# BeagleBone_Blue.net
KiCad netlist of a schematic drawn in EAGLE
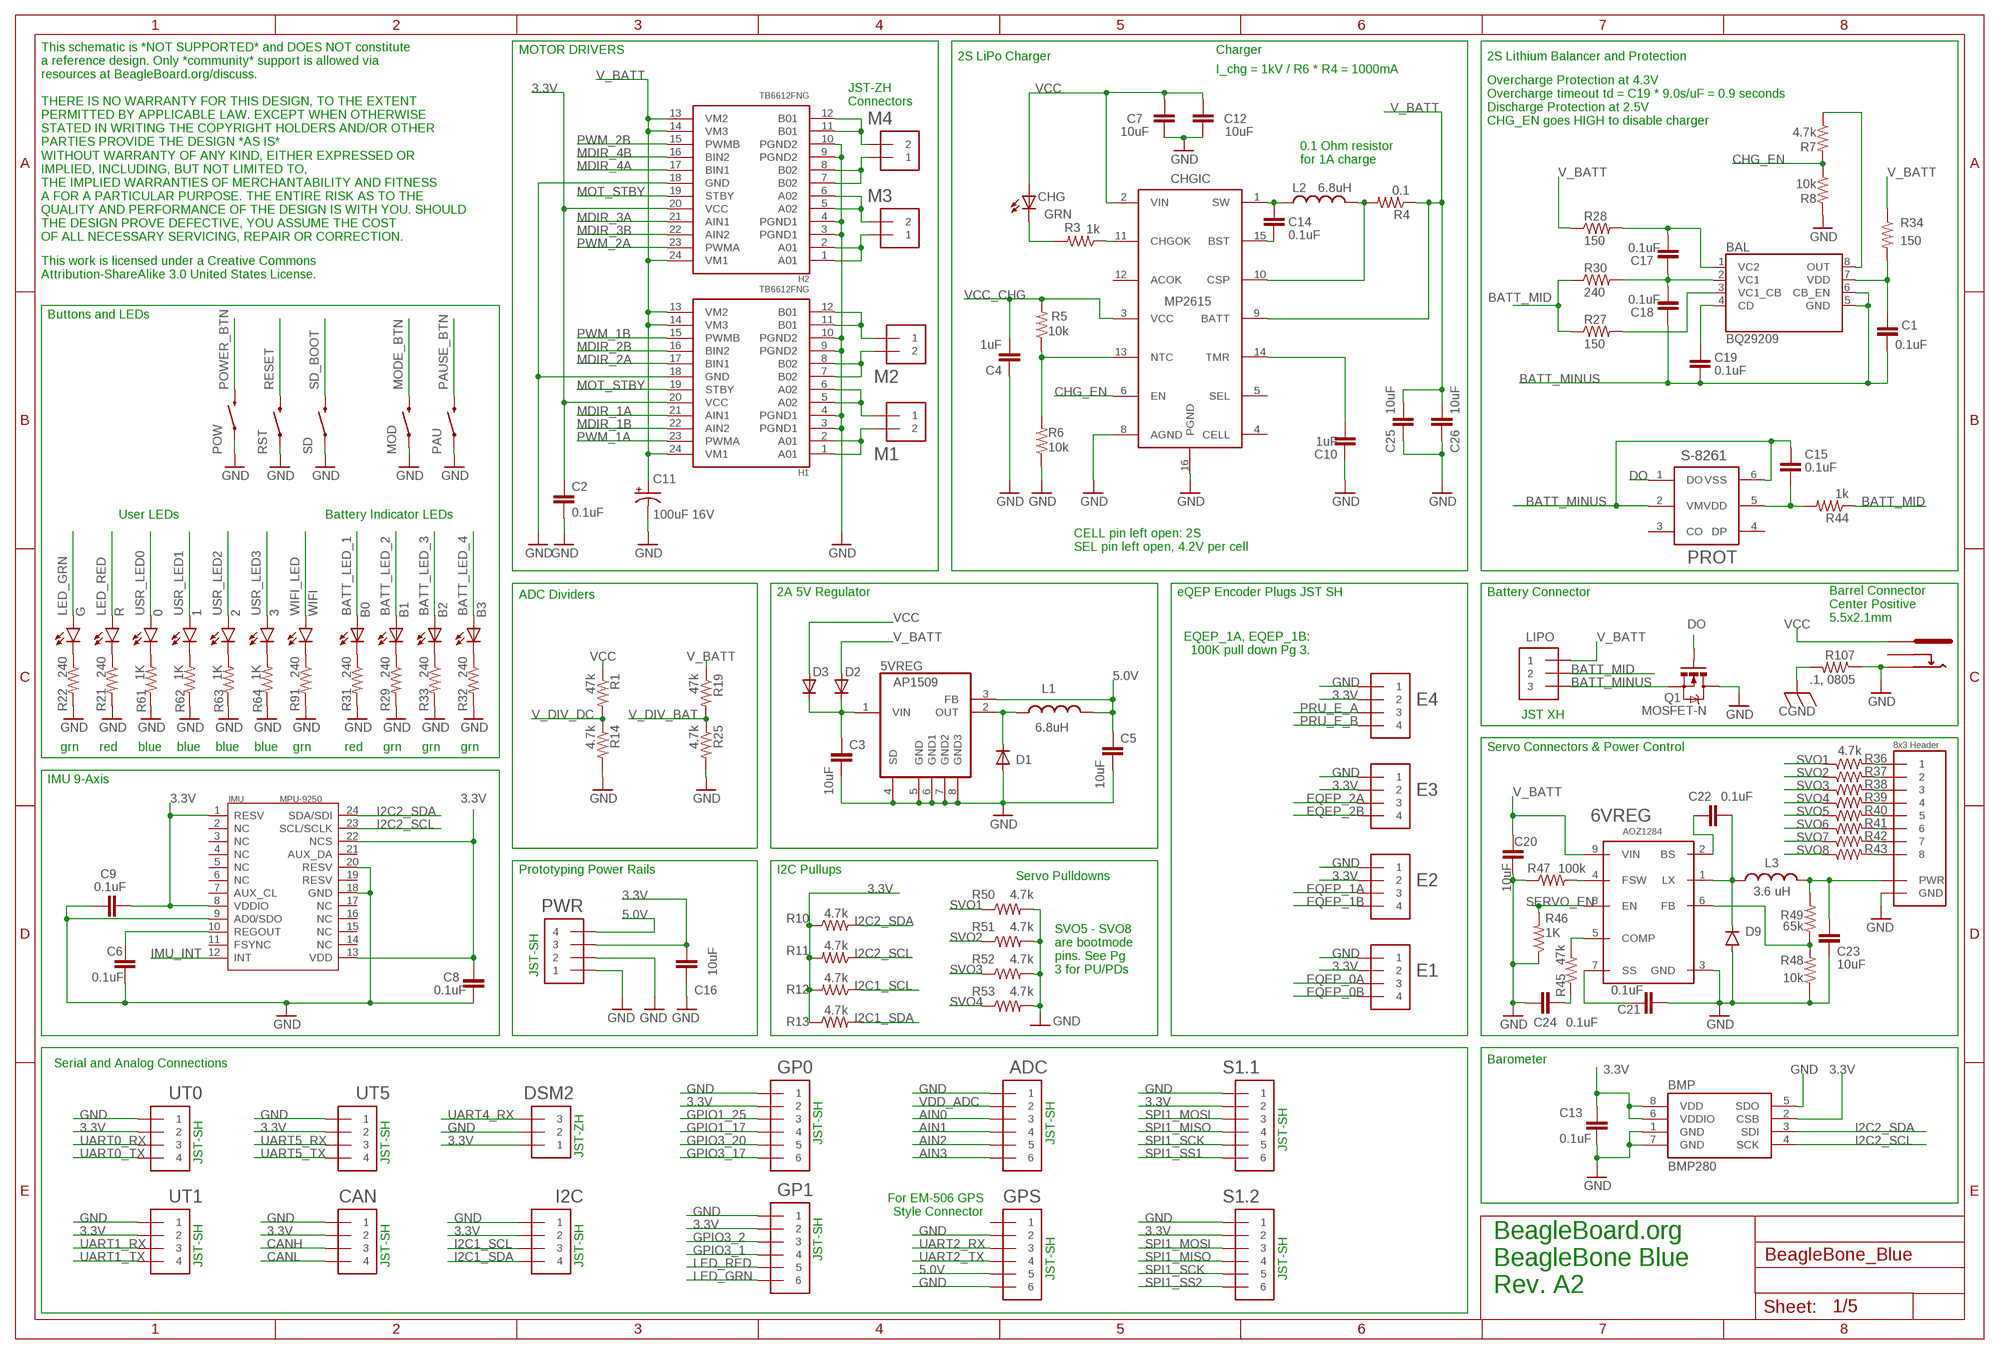
[diagram p0: schematic, sheet 1]
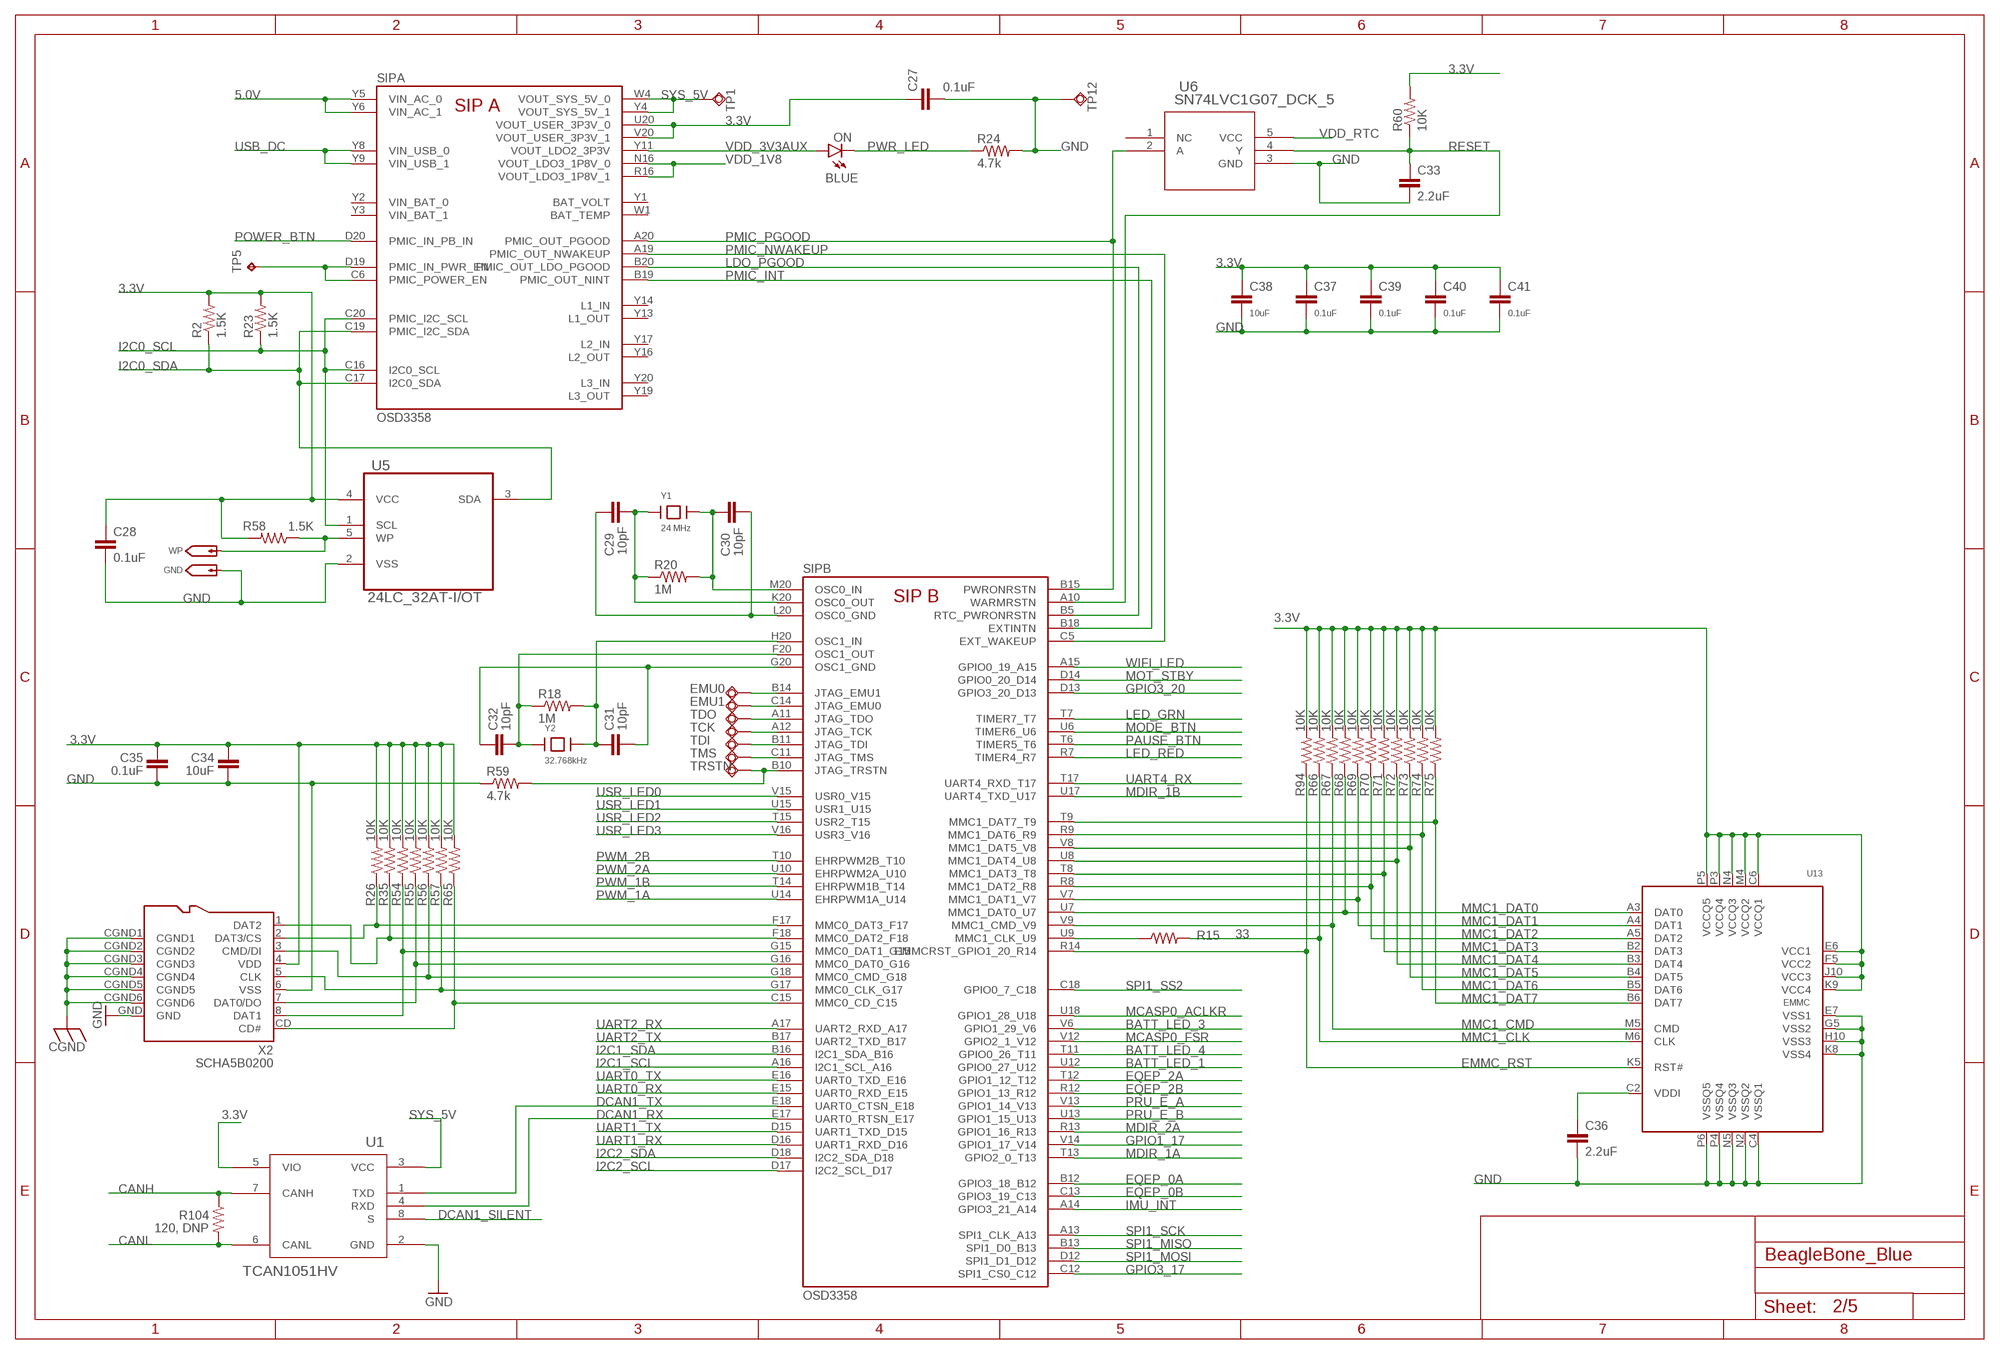
[diagram p1: schematic, sheet 2]
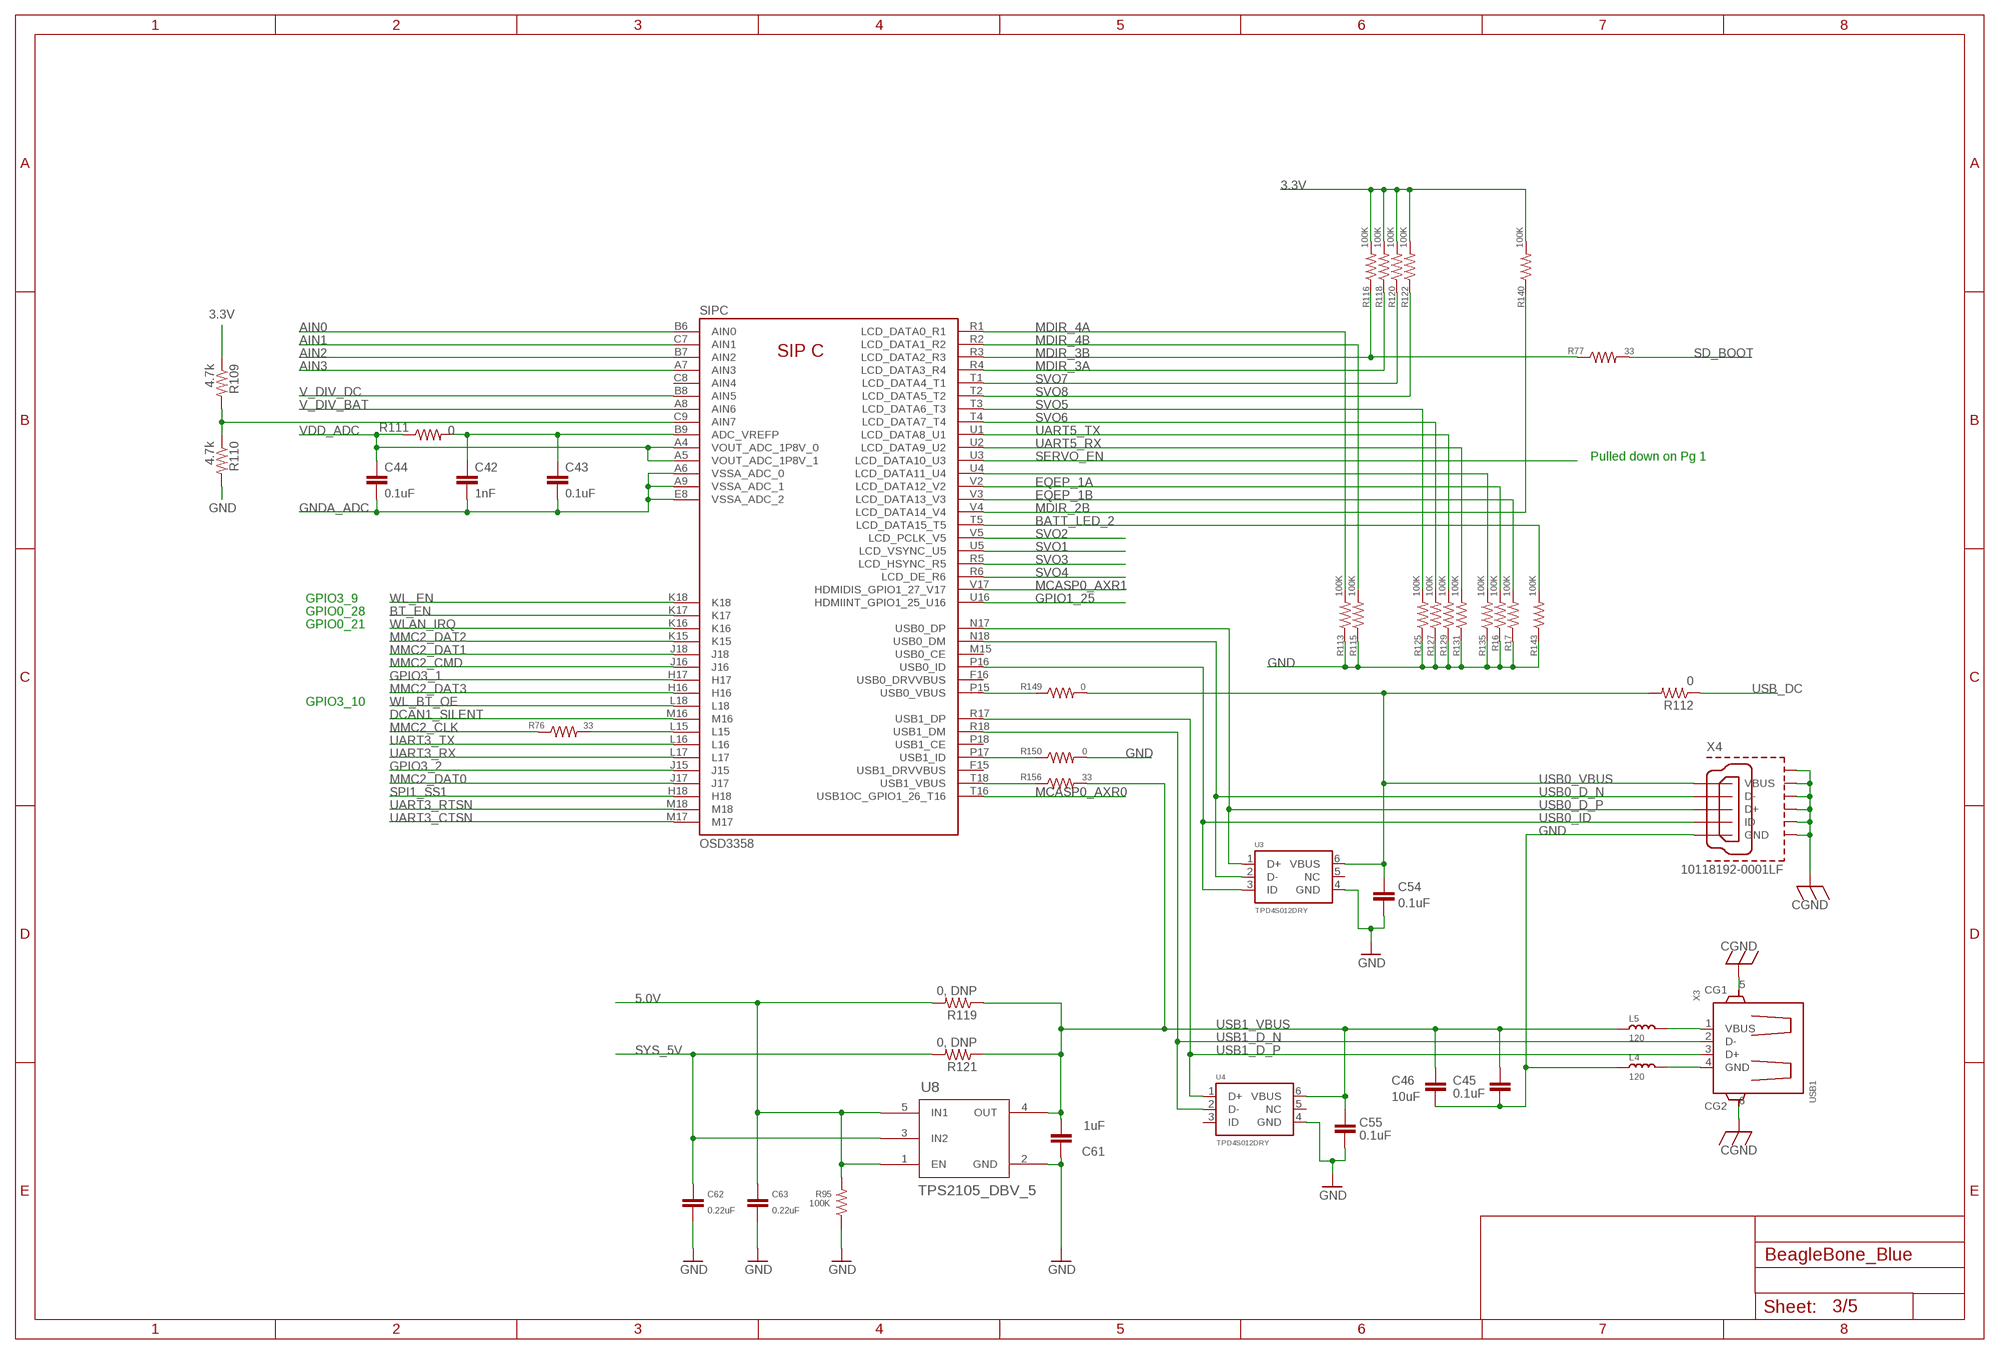
[diagram p2: schematic, sheet 3]
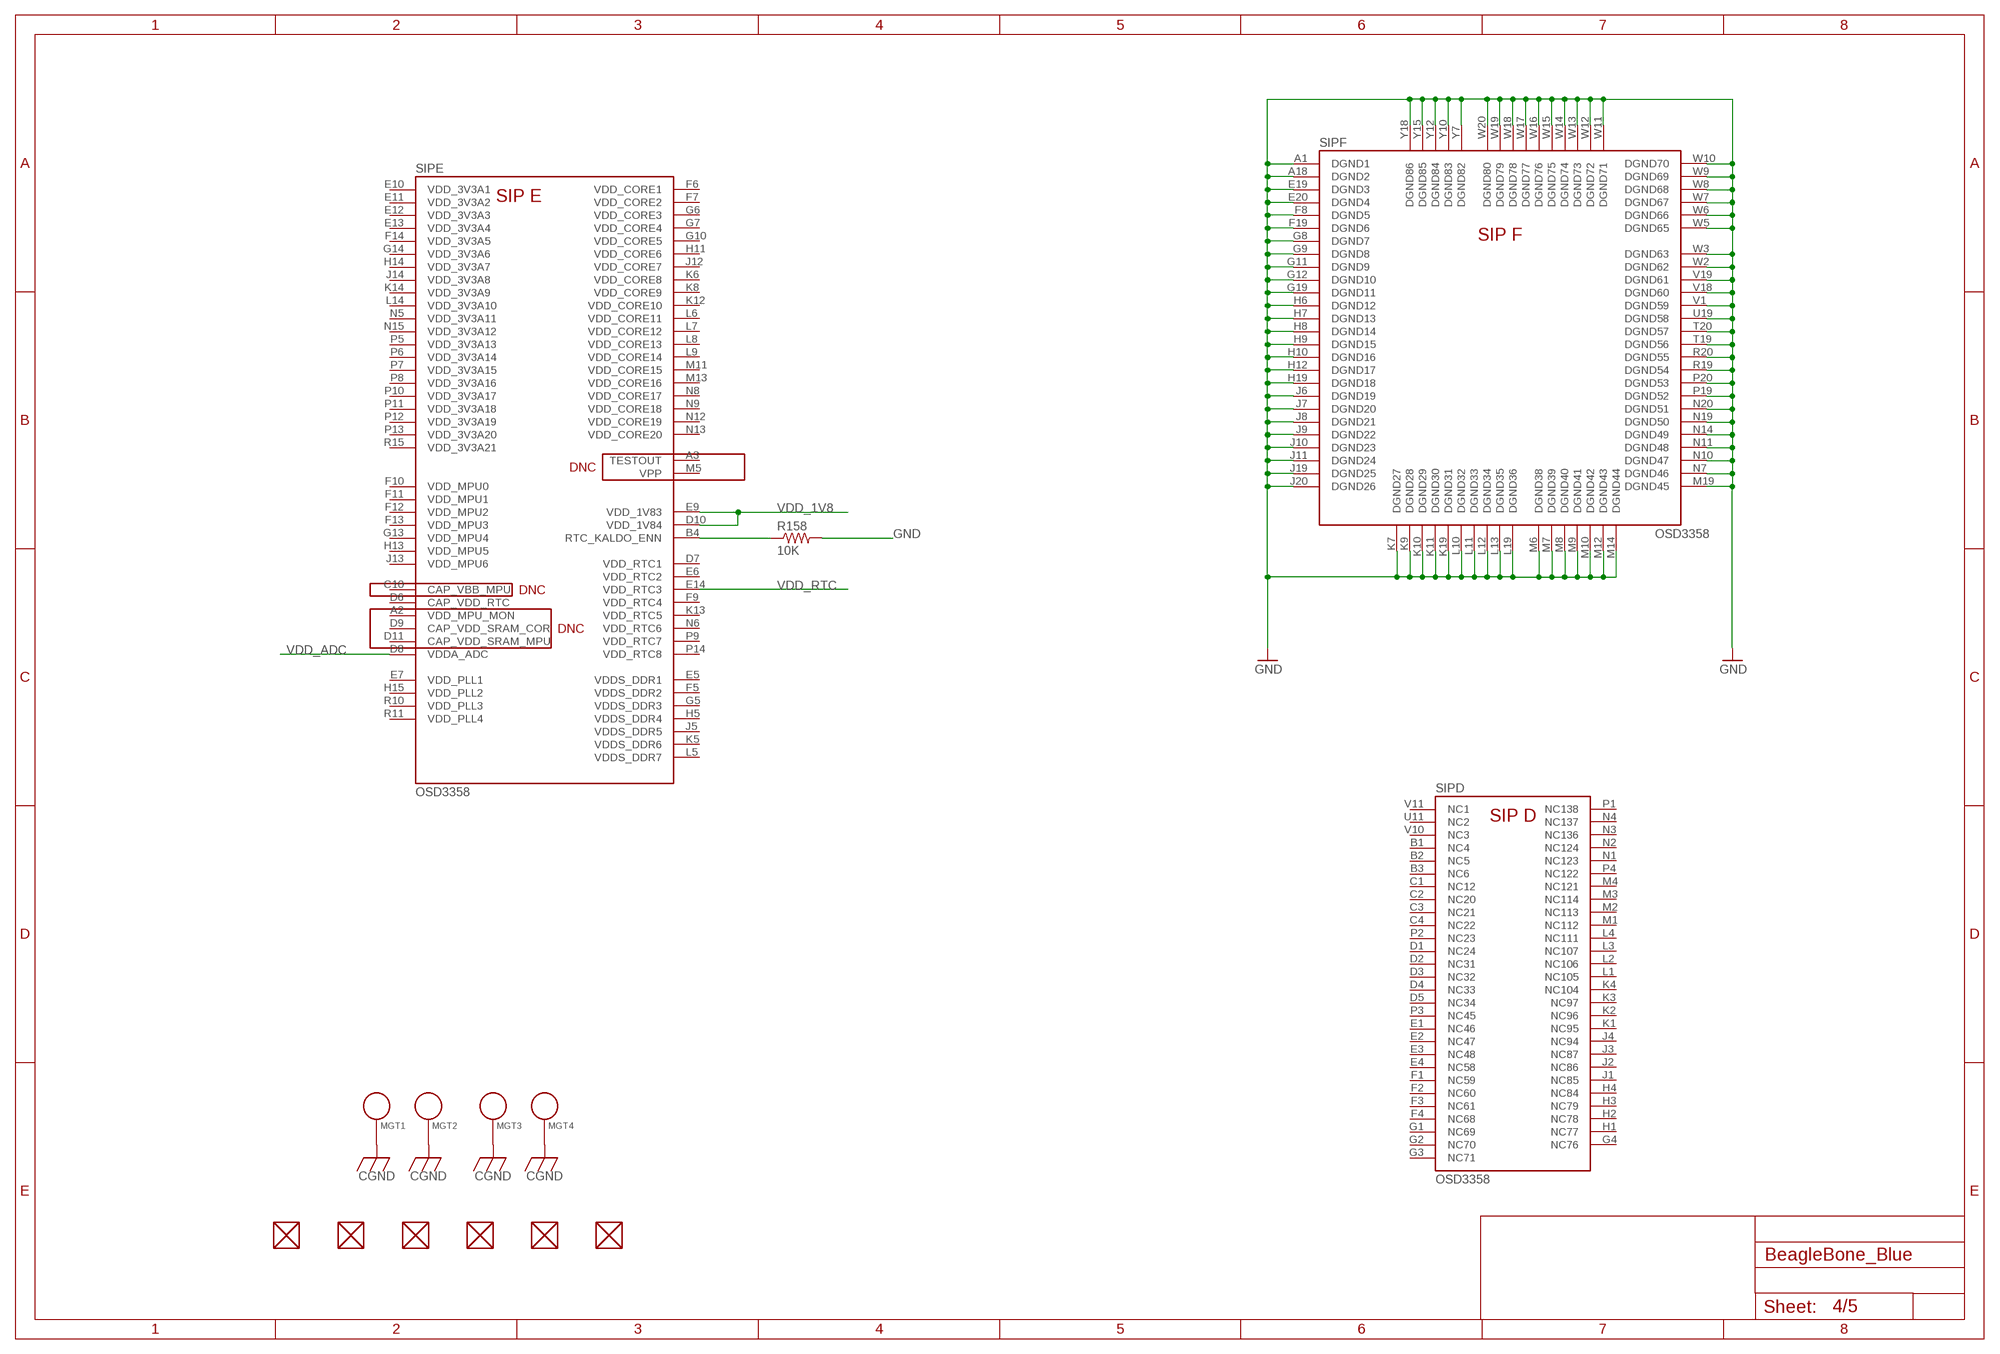
[diagram p3: schematic, sheet 4]
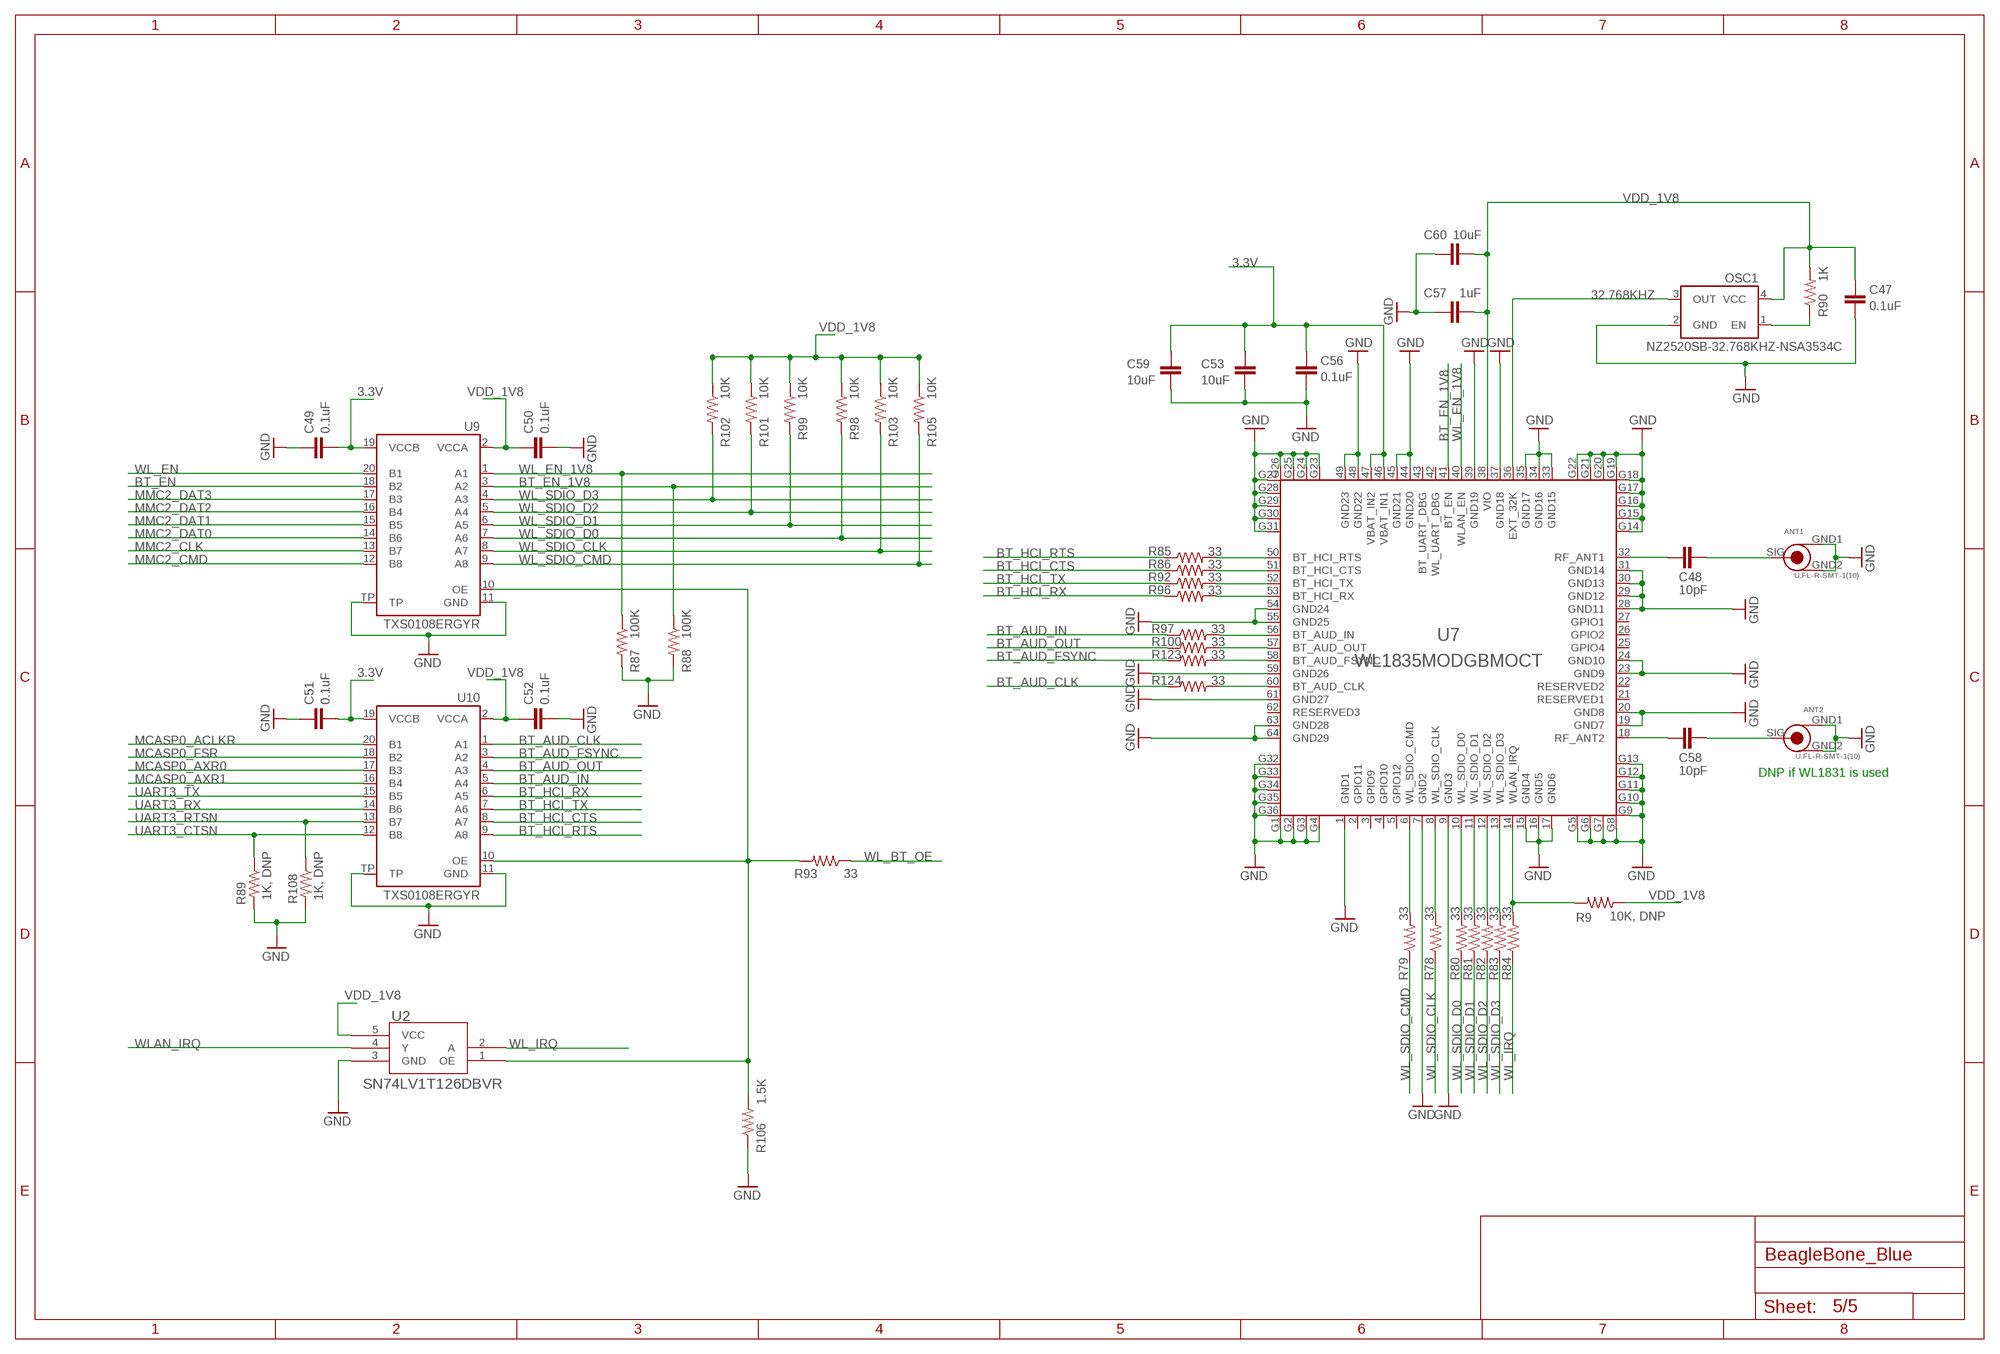
[diagram p4: schematic, sheet 5]

(export (version "E")
  (design (tool "Eeschema 10.0.6"))
  (components
    (comp (ref "C42")
      (value "1nF")
      (footprint "eagle-import:0402-CAP")
      (libsource (lib "eagle-import") (part "Strawson_Eagle_Lib_CAP0402-CAP"))
    )
    (comp (ref "C43")
      (value "0.1uF")
      (footprint "eagle-import:0402-CAP")
      (libsource (lib "eagle-import") (part "Strawson_Eagle_Lib_CAP0402-CAP"))
    )
    (comp (ref "C44")
      (value "0.1uF")
      (footprint "eagle-import:0402-CAP")
      (libsource (lib "eagle-import") (part "Strawson_Eagle_Lib_CAP0402-CAP"))
    )
    (comp (ref "C45")
      (value "0.1uF")
      (footprint "eagle-import:0402-CAP")
      (libsource (lib "eagle-import") (part "Strawson_Eagle_Lib_CAP0402-CAP"))
    )
    (comp (ref "C46")
      (value "10uF")
      (footprint "eagle-import:0805")
      (libsource (lib "eagle-import") (part "Strawson_Eagle_Lib_CAP0805"))
    )
    (comp (ref "C54")
      (value "0.1uF")
      (footprint "eagle-import:0402-CAP")
      (libsource (lib "eagle-import") (part "Strawson_Eagle_Lib_CAP0402-CAP"))
    )
    (comp (ref "C55")
      (value "0.1uF")
      (footprint "eagle-import:0402-CAP")
      (libsource (lib "eagle-import") (part "Strawson_Eagle_Lib_CAP0402-CAP"))
    )
    (comp (ref "C61")
      (value "1uF")
      (footprint "eagle-import:0402-CAP")
      (libsource (lib "eagle-import") (part "Strawson_Eagle_Lib_CAP0402-CAP"))
    )
    (comp (ref "C62")
      (value "0.22uF")
      (footprint "eagle-import:0402-CAP")
      (libsource (lib "eagle-import") (part "Strawson_Eagle_Lib_CAP0402-CAP"))
    )
    (comp (ref "C63")
      (value "0.22uF")
      (footprint "eagle-import:0402-CAP")
      (libsource (lib "eagle-import") (part "Strawson_Eagle_Lib_CAP0402-CAP"))
    )
    (comp (ref "L4")
      (value "120")
      (footprint "eagle-import:L0603")
      (libsource (lib "eagle-import") (part "INDUCTOR/FERRITE-BEAD'0603'"))
    )
    (comp (ref "L5")
      (value "120")
      (footprint "eagle-import:L0603")
      (libsource (lib "eagle-import") (part "INDUCTOR/FERRITE-BEAD'0603'"))
    )
    (comp (ref "R16")
      (value "100K")
      (footprint "eagle-import:0402-RES")
      (libsource (lib "eagle-import") (part "RESISTOR0402-RES"))
    )
    (comp (ref "R17")
      (value "100K")
      (footprint "eagle-import:0402-RES")
      (libsource (lib "eagle-import") (part "RESISTOR0402-RES"))
    )
    (comp (ref "R76")
      (value "33")
      (footprint "eagle-import:0402-RES")
      (libsource (lib "eagle-import") (part "RESISTOR0402-RES"))
    )
    (comp (ref "R77")
      (value "33")
      (footprint "eagle-import:0402-RES")
      (libsource (lib "eagle-import") (part "RESISTOR0402-RES"))
    )
    (comp (ref "R95")
      (value "100K")
      (footprint "eagle-import:0402-RES")
      (libsource (lib "eagle-import") (part "RESISTOR0402-RES"))
    )
    (comp (ref "R109")
      (value "4.7k")
      (footprint "eagle-import:0402-RES")
      (libsource (lib "eagle-import") (part "RESISTOR0402-RES"))
    )
    (comp (ref "R110")
      (value "4.7k")
      (footprint "eagle-import:0402-RES")
      (libsource (lib "eagle-import") (part "RESISTOR0402-RES"))
    )
    (comp (ref "R111")
      (value "0")
      (footprint "eagle-import:0402-RES")
      (libsource (lib "eagle-import") (part "RESISTOR0402-RES"))
    )
    (comp (ref "R112")
      (value "0")
      (footprint "eagle-import:0603-RES")
      (libsource (lib "eagle-import") (part "RESISTOR0603"))
    )
    (comp (ref "R113")
      (value "100K")
      (footprint "eagle-import:0402-RES")
      (libsource (lib "eagle-import") (part "RESISTOR0402-RES"))
    )
    (comp (ref "R115")
      (value "100K")
      (footprint "eagle-import:0402-RES")
      (libsource (lib "eagle-import") (part "RESISTOR0402-RES"))
    )
    (comp (ref "R116")
      (value "100K")
      (footprint "eagle-import:0402-RES")
      (libsource (lib "eagle-import") (part "RESISTOR0402-RES"))
    )
    (comp (ref "R118")
      (value "100K")
      (footprint "eagle-import:0402-RES")
      (libsource (lib "eagle-import") (part "RESISTOR0402-RES"))
    )
    (comp (ref "R119")
      (value "0, DNP")
      (footprint "eagle-import:0603-RES")
      (libsource (lib "eagle-import") (part "RESISTOR0603"))
    )
    (comp (ref "R120")
      (value "100K")
      (footprint "eagle-import:0402-RES")
      (libsource (lib "eagle-import") (part "RESISTOR0402-RES"))
    )
    (comp (ref "R121")
      (value "0, DNP")
      (footprint "eagle-import:0603-RES")
      (libsource (lib "eagle-import") (part "RESISTOR0603"))
    )
    (comp (ref "R122")
      (value "100K")
      (footprint "eagle-import:0402-RES")
      (libsource (lib "eagle-import") (part "RESISTOR0402-RES"))
    )
    (comp (ref "R125")
      (value "100K")
      (footprint "eagle-import:0402-RES")
      (libsource (lib "eagle-import") (part "RESISTOR0402-RES"))
    )
    (comp (ref "R127")
      (value "100K")
      (footprint "eagle-import:0402-RES")
      (libsource (lib "eagle-import") (part "RESISTOR0402-RES"))
    )
    (comp (ref "R129")
      (value "100K")
      (footprint "eagle-import:0402-RES")
      (libsource (lib "eagle-import") (part "RESISTOR0402-RES"))
    )
    (comp (ref "R131")
      (value "100K")
      (footprint "eagle-import:0402-RES")
      (libsource (lib "eagle-import") (part "RESISTOR0402-RES"))
    )
    (comp (ref "R135")
      (value "100K")
      (footprint "eagle-import:0402-RES")
      (libsource (lib "eagle-import") (part "RESISTOR0402-RES"))
    )
    (comp (ref "R140")
      (value "100K")
      (footprint "eagle-import:0402-RES")
      (libsource (lib "eagle-import") (part "RESISTOR0402-RES"))
    )
    (comp (ref "R143")
      (value "100K")
      (footprint "eagle-import:0402-RES")
      (libsource (lib "eagle-import") (part "RESISTOR0402-RES"))
    )
    (comp (ref "R149")
      (value "0")
      (footprint "eagle-import:0402-RES")
      (libsource (lib "eagle-import") (part "RESISTOR0402-RES"))
    )
    (comp (ref "R150")
      (value "0")
      (footprint "eagle-import:0402-RES")
      (libsource (lib "eagle-import") (part "RESISTOR0402-RES"))
    )
    (comp (ref "R156")
      (value "33")
      (footprint "eagle-import:0402-RES")
      (libsource (lib "eagle-import") (part "RESISTOR0402-RES"))
    )
    (comp (ref "SIP")
      (value "OSD3358")
      (footprint "eagle-import:BEAGLEBONE_BLUE_OSD3358")
      (libsource (lib "eagle-import") (part "OSD3358"))
    )
    (comp (ref "U3")
      (value "TPD4S012DRY")
      (footprint "eagle-import:SON-6(TI)-DRY")
      (libsource (lib "eagle-import") (part "TPD4S012DRYR"))
    )
    (comp (ref "U4")
      (value "TPD4S012DRY")
      (footprint "eagle-import:SON-6(TI)-DRY")
      (libsource (lib "eagle-import") (part "TPD4S012DRYR"))
    )
    (comp (ref "U8")
      (value "TPS2105_DBV_5")
      (footprint "eagle-import:DBV5")
      (fields
        (field (name "GENERIC_PART_NUMBER") "TPS2105")
        (field (name "MANUFACTURER") "Texas Instruments")
        (field (name "MANUFACTURER_PART_NUMBER") "tps2105_dbv_5")
      )
      (libsource (lib "eagle-import") (part "TPS2105_DBV_5"))
    )
    (comp (ref "X3")
      (value "USB1")
      (footprint "eagle-import:USB_HOST_HORIZONTAL_W_CHASSIS_GND")
      (libsource (lib "eagle-import") (part "USB_HOST_W/CHASSIS_GND"))
    )
    (comp (ref "X4")
      (value "10118192-0001LF")
      (footprint "eagle-import:10118192-0001LF(MICRO-USB-B-AMPHENOL-FCI)")
      (libsource (lib "eagle-import") (part "10118192-0001LF"))
    )
    (comp (ref "ANT1")
      (value "U.FL-R-SMT-1(10)")
      (footprint "eagle-import:U.FL-R-SMT-1")
      (libsource (lib "eagle-import") (part "U.FL-R-SMT-1"))
    )
    (comp (ref "ANT2")
      (value "U.FL-R-SMT-1(10)")
      (footprint "eagle-import:U.FL-R-SMT-1")
      (libsource (lib "eagle-import") (part "U.FL-R-SMT-1"))
    )
    (comp (ref "C47")
      (value "0.1uF")
      (footprint "eagle-import:0402-CAP")
      (libsource (lib "eagle-import") (part "Strawson_Eagle_Lib_CAP0402-CAP"))
    )
    (comp (ref "C48")
      (value "10pF")
      (footprint "eagle-import:0402-CAP")
      (libsource (lib "eagle-import") (part "Strawson_Eagle_Lib_CAP0402-CAP"))
    )
    (comp (ref "C49")
      (value "0.1uF")
      (footprint "eagle-import:0402-CAP")
      (libsource (lib "eagle-import") (part "Strawson_Eagle_Lib_CAP0402-CAP"))
    )
    (comp (ref "C50")
      (value "0.1uF")
      (footprint "eagle-import:0402-CAP")
      (libsource (lib "eagle-import") (part "Strawson_Eagle_Lib_CAP0402-CAP"))
    )
    (comp (ref "C51")
      (value "0.1uF")
      (footprint "eagle-import:0402-CAP")
      (libsource (lib "eagle-import") (part "Strawson_Eagle_Lib_CAP0402-CAP"))
    )
    (comp (ref "C52")
      (value "0.1uF")
      (footprint "eagle-import:0402-CAP")
      (libsource (lib "eagle-import") (part "Strawson_Eagle_Lib_CAP0402-CAP"))
    )
    (comp (ref "C53")
      (value "10uF")
      (footprint "eagle-import:0805")
      (libsource (lib "eagle-import") (part "CAP0805"))
    )
    (comp (ref "C56")
      (value "0.1uF")
      (footprint "eagle-import:0402-CAP")
      (libsource (lib "eagle-import") (part "Strawson_Eagle_Lib_CAP0402-CAP"))
    )
    (comp (ref "C57")
      (value "1uF")
      (footprint "eagle-import:0402-CAP")
      (libsource (lib "eagle-import") (part "Strawson_Eagle_Lib_CAP0402-CAP"))
    )
    (comp (ref "C58")
      (value "10pF")
      (footprint "eagle-import:0402-CAP")
      (libsource (lib "eagle-import") (part "Strawson_Eagle_Lib_CAP0402-CAP"))
    )
    (comp (ref "C59")
      (value "10uF")
      (footprint "eagle-import:0805")
      (libsource (lib "eagle-import") (part "CAP0805"))
    )
    (comp (ref "C60")
      (value "10uF")
      (footprint "eagle-import:0805")
      (libsource (lib "eagle-import") (part "CAP0805"))
    )
    (comp (ref "OSC1")
      (value "NZ2520SB-32.768KHZ-NSA3534C")
      (footprint "eagle-import:NZ2520S")
      (libsource (lib "eagle-import") (part "OSCILLATOR"))
    )
    (comp (ref "R9")
      (value "10K, DNP")
      (footprint "eagle-import:0402-RES")
      (libsource (lib "eagle-import") (part "RESISTOR0402-RES"))
    )
    (comp (ref "R78")
      (value "33")
      (footprint "eagle-import:0402-RES")
      (libsource (lib "eagle-import") (part "RESISTOR0402-RES"))
    )
    (comp (ref "R79")
      (value "33")
      (footprint "eagle-import:0402-RES")
      (libsource (lib "eagle-import") (part "RESISTOR0402-RES"))
    )
    (comp (ref "R80")
      (value "33")
      (footprint "eagle-import:0402-RES")
      (libsource (lib "eagle-import") (part "RESISTOR0402-RES"))
    )
    (comp (ref "R81")
      (value "33")
      (footprint "eagle-import:0402-RES")
      (libsource (lib "eagle-import") (part "RESISTOR0402-RES"))
    )
    (comp (ref "R82")
      (value "33")
      (footprint "eagle-import:0402-RES")
      (libsource (lib "eagle-import") (part "RESISTOR0402-RES"))
    )
    (comp (ref "R83")
      (value "33")
      (footprint "eagle-import:0402-RES")
      (libsource (lib "eagle-import") (part "RESISTOR0402-RES"))
    )
    (comp (ref "R84")
      (value "33")
      (footprint "eagle-import:0402-RES")
      (libsource (lib "eagle-import") (part "RESISTOR0402-RES"))
    )
    (comp (ref "R85")
      (value "33")
      (footprint "eagle-import:0402-RES")
      (libsource (lib "eagle-import") (part "RESISTOR0402-RES"))
    )
    (comp (ref "R86")
      (value "33")
      (footprint "eagle-import:0402-RES")
      (libsource (lib "eagle-import") (part "RESISTOR0402-RES"))
    )
    (comp (ref "R87")
      (value "100K")
      (footprint "eagle-import:0402-RES")
      (libsource (lib "eagle-import") (part "RESISTOR0402-RES"))
    )
    (comp (ref "R88")
      (value "100K")
      (footprint "eagle-import:0402-RES")
      (libsource (lib "eagle-import") (part "RESISTOR0402-RES"))
    )
    (comp (ref "R89")
      (value "1K, DNP")
      (footprint "eagle-import:0402-RES")
      (libsource (lib "eagle-import") (part "RESISTOR0402-RES"))
    )
    (comp (ref "R90")
      (value "1K")
      (footprint "eagle-import:0402-RES")
      (libsource (lib "eagle-import") (part "RESISTOR0402-RES"))
    )
    (comp (ref "R92")
      (value "33")
      (footprint "eagle-import:0402-RES")
      (libsource (lib "eagle-import") (part "RESISTOR0402-RES"))
    )
    (comp (ref "R93")
      (value "33")
      (footprint "eagle-import:0402-RES")
      (libsource (lib "eagle-import") (part "RESISTOR0402-RES"))
    )
    (comp (ref "R96")
      (value "33")
      (footprint "eagle-import:0402-RES")
      (libsource (lib "eagle-import") (part "RESISTOR0402-RES"))
    )
    (comp (ref "R97")
      (value "33")
      (footprint "eagle-import:0402-RES")
      (libsource (lib "eagle-import") (part "RESISTOR0402-RES"))
    )
    (comp (ref "R98")
      (value "10K")
      (footprint "eagle-import:0402-RES")
      (libsource (lib "eagle-import") (part "RESISTOR0402-RES"))
    )
    (comp (ref "R99")
      (value "10K")
      (footprint "eagle-import:0402-RES")
      (libsource (lib "eagle-import") (part "RESISTOR0402-RES"))
    )
    (comp (ref "R100")
      (value "33")
      (footprint "eagle-import:0402-RES")
      (libsource (lib "eagle-import") (part "RESISTOR0402-RES"))
    )
    (comp (ref "R101")
      (value "10K")
      (footprint "eagle-import:0402-RES")
      (libsource (lib "eagle-import") (part "RESISTOR0402-RES"))
    )
    (comp (ref "R102")
      (value "10K")
      (footprint "eagle-import:0402-RES")
      (libsource (lib "eagle-import") (part "RESISTOR0402-RES"))
    )
    (comp (ref "R103")
      (value "10K")
      (footprint "eagle-import:0402-RES")
      (libsource (lib "eagle-import") (part "RESISTOR0402-RES"))
    )
    (comp (ref "R105")
      (value "10K")
      (footprint "eagle-import:0402-RES")
      (libsource (lib "eagle-import") (part "RESISTOR0402-RES"))
    )
    (comp (ref "R106")
      (value "1.5K")
      (footprint "eagle-import:0402-RES")
      (libsource (lib "eagle-import") (part "RESISTOR0402-RES"))
    )
    (comp (ref "R108")
      (value "1K, DNP")
      (footprint "eagle-import:0402-RES")
      (libsource (lib "eagle-import") (part "RESISTOR0402-RES"))
    )
    (comp (ref "R123")
      (value "33")
      (footprint "eagle-import:0402-RES")
      (libsource (lib "eagle-import") (part "RESISTOR0402-RES"))
    )
    (comp (ref "R124")
      (value "33")
      (footprint "eagle-import:0402-RES")
      (libsource (lib "eagle-import") (part "RESISTOR0402-RES"))
    )
    (comp (ref "U2")
      (value "SN74LV1T126DBVR")
      (footprint "eagle-import:BEAGLEBONE_BLUE_SOT23-5")
      (libsource (lib "eagle-import") (part "SN74LV1T126DBVR"))
    )
    (comp (ref "U7")
      (value "WL1835MODGBMOCT")
      (footprint "eagle-import:MOC-100(TI)")
      (libsource (lib "eagle-import") (part "WL1835MOD"))
    )
    (comp (ref "U9")
      (value "TXS0108ERGYR")
      (footprint "eagle-import:R-PVQFN-N20(TI)")
      (libsource (lib "eagle-import") (part "TXS0108ERGYR"))
    )
    (comp (ref "U10")
      (value "TXS0108ERGYR")
      (footprint "eagle-import:R-PVQFN-N20(TI)")
      (libsource (lib "eagle-import") (part "TXS0108ERGYR"))
    )
    (comp (ref "FUD1")
      (value "FIDUCIAL")
      (footprint "eagle-import:FIDUCIAL_40MIL")
      (libsource (lib "eagle-import") (part "FIDUCIAL"))
    )
    (comp (ref "FUD2")
      (value "FIDUCIAL")
      (footprint "eagle-import:FIDUCIAL_40MIL")
      (libsource (lib "eagle-import") (part "FIDUCIAL"))
    )
    (comp (ref "FUD3")
      (value "FIDUCIAL")
      (footprint "eagle-import:FIDUCIAL_40MIL")
      (libsource (lib "eagle-import") (part "FIDUCIAL"))
    )
    (comp (ref "FUD4")
      (value "FIDUCIAL")
      (footprint "eagle-import:FIDUCIAL_40MIL")
      (libsource (lib "eagle-import") (part "FIDUCIAL"))
    )
    (comp (ref "FUD5")
      (value "FIDUCIAL")
      (footprint "eagle-import:FIDUCIAL_40MIL")
      (libsource (lib "eagle-import") (part "FIDUCIAL"))
    )
    (comp (ref "FUD6")
      (value "FIDUCIAL")
      (footprint "eagle-import:FIDUCIAL_40MIL")
      (libsource (lib "eagle-import") (part "FIDUCIAL"))
    )
    (comp (ref "MGT1")
      (value "MOUNTING_HOLE")
      (footprint "eagle-import:MOUNTING_HOLE")
      (libsource (lib "eagle-import") (part "MOUNTING_HOLE"))
    )
    (comp (ref "MGT2")
      (value "MOUNTING_HOLE")
      (footprint "eagle-import:MOUNTING_HOLE")
      (libsource (lib "eagle-import") (part "MOUNTING_HOLE"))
    )
    (comp (ref "MGT3")
      (value "MOUNTING_HOLE")
      (footprint "eagle-import:MOUNTING_HOLE")
      (libsource (lib "eagle-import") (part "MOUNTING_HOLE"))
    )
    (comp (ref "MGT4")
      (value "MOUNTING_HOLE")
      (footprint "eagle-import:MOUNTING_HOLE")
      (libsource (lib "eagle-import") (part "MOUNTING_HOLE"))
    )
    (comp (ref "R158")
      (value "10K")
      (footprint "eagle-import:0402-RES")
      (libsource (lib "eagle-import") (part "RESISTOR0402-RES"))
    )
    (comp (ref "C27")
      (value "0.1uF")
      (footprint "eagle-import:0402-CAP")
      (libsource (lib "eagle-import") (part "Strawson_Eagle_Lib_CAP0402-CAP"))
    )
    (comp (ref "C28")
      (value "0.1uF")
      (footprint "eagle-import:0402-CAP")
      (libsource (lib "eagle-import") (part "Strawson_Eagle_Lib_CAP0402-CAP"))
    )
    (comp (ref "C29")
      (value "10pF")
      (footprint "eagle-import:0402-CAP")
      (libsource (lib "eagle-import") (part "Strawson_Eagle_Lib_CAP0402-CAP"))
    )
    (comp (ref "C30")
      (value "10pF")
      (footprint "eagle-import:0402-CAP")
      (libsource (lib "eagle-import") (part "Strawson_Eagle_Lib_CAP0402-CAP"))
    )
    (comp (ref "C31")
      (value "10pF")
      (footprint "eagle-import:0402-CAP")
      (libsource (lib "eagle-import") (part "Strawson_Eagle_Lib_CAP0402-CAP"))
    )
    (comp (ref "C32")
      (value "10pF")
      (footprint "eagle-import:0402-CAP")
      (libsource (lib "eagle-import") (part "Strawson_Eagle_Lib_CAP0402-CAP"))
    )
    (comp (ref "C33")
      (value "2.2uF")
      (footprint "eagle-import:0402-CAP")
      (libsource (lib "eagle-import") (part "Strawson_Eagle_Lib_CAP0402-CAP"))
    )
    (comp (ref "C34")
      (value "10uF")
      (footprint "eagle-import:0805")
      (libsource (lib "eagle-import") (part "Strawson_Eagle_Lib_CAP0805"))
    )
    (comp (ref "C35")
      (value "0.1uF")
      (footprint "eagle-import:0402-CAP")
      (libsource (lib "eagle-import") (part "Strawson_Eagle_Lib_CAP0402-CAP"))
    )
    (comp (ref "C36")
      (value "2.2uF")
      (footprint "eagle-import:0402-CAP")
      (libsource (lib "eagle-import") (part "Strawson_Eagle_Lib_CAP0402-CAP"))
    )
    (comp (ref "C37")
      (value "0.1uF")
      (footprint "eagle-import:0402-CAP")
      (libsource (lib "eagle-import") (part "Strawson_Eagle_Lib_CAP0402-CAP"))
    )
    (comp (ref "C38")
      (value "10uF")
      (footprint "eagle-import:0805")
      (libsource (lib "eagle-import") (part "Strawson_Eagle_Lib_CAP0805"))
    )
    (comp (ref "C39")
      (value "0.1uF")
      (footprint "eagle-import:0402-CAP")
      (libsource (lib "eagle-import") (part "Strawson_Eagle_Lib_CAP0402-CAP"))
    )
    (comp (ref "C40")
      (value "0.1uF")
      (footprint "eagle-import:0402-CAP")
      (libsource (lib "eagle-import") (part "Strawson_Eagle_Lib_CAP0402-CAP"))
    )
    (comp (ref "C41")
      (value "0.1uF")
      (footprint "eagle-import:0402-CAP")
      (libsource (lib "eagle-import") (part "Strawson_Eagle_Lib_CAP0402-CAP"))
    )
    (comp (ref "EMU0")
      (value "TPSQB1,27")
      (footprint "eagle-import:B1,27")
      (libsource (lib "eagle-import") (part "TPSQB1,27"))
    )
    (comp (ref "EMU1")
      (value "TPSQB1,27")
      (footprint "eagle-import:B1,27")
      (libsource (lib "eagle-import") (part "TPSQB1,27"))
    )
    (comp (ref "GND")
      (value "GHI2_TESTPAD/W_HOLE_1X1")
      (footprint "eagle-import:GHI2_TESTPAD_W_HOLE_1X1")
      (libsource (lib "eagle-import") (part "GHI2_TESTPAD/W_HOLE_1X1"))
    )
    (comp (ref "ON")
      (value "BLUE")
      (footprint "eagle-import:BEAGLEBONE_BLUE_LED-0603")
      (libsource (lib "eagle-import") (part "LED0603"))
    )
    (comp (ref "R2")
      (value "1.5K")
      (footprint "eagle-import:0402-RES")
      (libsource (lib "eagle-import") (part "RESISTOR0402-RES"))
    )
    (comp (ref "R15")
      (value "33")
      (footprint "eagle-import:0402-RES")
      (libsource (lib "eagle-import") (part "RESISTOR0402-RES"))
    )
    (comp (ref "R18")
      (value "1M")
      (footprint "eagle-import:0402-RES")
      (libsource (lib "eagle-import") (part "RESISTOR0402-RES"))
    )
    (comp (ref "R20")
      (value "1M")
      (footprint "eagle-import:0402-RES")
      (libsource (lib "eagle-import") (part "RESISTOR0402-RES"))
    )
    (comp (ref "R23")
      (value "1.5K")
      (footprint "eagle-import:0402-RES")
      (libsource (lib "eagle-import") (part "RESISTOR0402-RES"))
    )
    (comp (ref "R24")
      (value "4.7k")
      (footprint "eagle-import:0402-RES")
      (libsource (lib "eagle-import") (part "RESISTOR0402-RES"))
    )
    (comp (ref "R26")
      (value "10K")
      (footprint "eagle-import:0402-RES")
      (libsource (lib "eagle-import") (part "RESISTOR0402-RES"))
    )
    (comp (ref "R35")
      (value "10K")
      (footprint "eagle-import:0402-RES")
      (libsource (lib "eagle-import") (part "RESISTOR0402-RES"))
    )
    (comp (ref "R54")
      (value "10K")
      (footprint "eagle-import:0402-RES")
      (libsource (lib "eagle-import") (part "RESISTOR0402-RES"))
    )
    (comp (ref "R55")
      (value "10K")
      (footprint "eagle-import:0402-RES")
      (libsource (lib "eagle-import") (part "RESISTOR0402-RES"))
    )
    (comp (ref "R56")
      (value "10K")
      (footprint "eagle-import:0402-RES")
      (libsource (lib "eagle-import") (part "RESISTOR0402-RES"))
    )
    (comp (ref "R57")
      (value "10K")
      (footprint "eagle-import:0402-RES")
      (libsource (lib "eagle-import") (part "RESISTOR0402-RES"))
    )
    (comp (ref "R58")
      (value "1.5K")
      (footprint "eagle-import:0402-RES")
      (libsource (lib "eagle-import") (part "RESISTOR0402-RES"))
    )
    (comp (ref "R59")
      (value "4.7k")
      (footprint "eagle-import:0402-RES")
      (libsource (lib "eagle-import") (part "RESISTOR0402-RES"))
    )
    (comp (ref "R60")
      (value "10K")
      (footprint "eagle-import:0402-RES")
      (libsource (lib "eagle-import") (part "RESISTOR0402-RES"))
    )
    (comp (ref "R65")
      (value "10K")
      (footprint "eagle-import:0402-RES")
      (libsource (lib "eagle-import") (part "RESISTOR0402-RES"))
    )
    (comp (ref "R66")
      (value "10K")
      (footprint "eagle-import:0402-RES")
      (libsource (lib "eagle-import") (part "RESISTOR0402-RES"))
    )
    (comp (ref "R67")
      (value "10K")
      (footprint "eagle-import:0402-RES")
      (libsource (lib "eagle-import") (part "RESISTOR0402-RES"))
    )
    (comp (ref "R68")
      (value "10K")
      (footprint "eagle-import:0402-RES")
      (libsource (lib "eagle-import") (part "RESISTOR0402-RES"))
    )
    (comp (ref "R69")
      (value "10K")
      (footprint "eagle-import:0402-RES")
      (libsource (lib "eagle-import") (part "RESISTOR0402-RES"))
    )
    (comp (ref "R70")
      (value "10K")
      (footprint "eagle-import:0402-RES")
      (libsource (lib "eagle-import") (part "RESISTOR0402-RES"))
    )
    (comp (ref "R71")
      (value "10K")
      (footprint "eagle-import:0402-RES")
      (libsource (lib "eagle-import") (part "RESISTOR0402-RES"))
    )
    (comp (ref "R72")
      (value "10K")
      (footprint "eagle-import:0402-RES")
      (libsource (lib "eagle-import") (part "RESISTOR0402-RES"))
    )
    (comp (ref "R73")
      (value "10K")
      (footprint "eagle-import:0402-RES")
      (libsource (lib "eagle-import") (part "RESISTOR0402-RES"))
    )
    (comp (ref "R74")
      (value "10K")
      (footprint "eagle-import:0402-RES")
      (libsource (lib "eagle-import") (part "RESISTOR0402-RES"))
    )
    (comp (ref "R75")
      (value "10K")
      (footprint "eagle-import:0402-RES")
      (libsource (lib "eagle-import") (part "RESISTOR0402-RES"))
    )
    (comp (ref "R94")
      (value "10K")
      (footprint "eagle-import:0402-RES")
      (libsource (lib "eagle-import") (part "RESISTOR0402-RES"))
    )
    (comp (ref "R104")
      (value "120, DNP")
      (footprint "eagle-import:0603-RES")
      (libsource (lib "eagle-import") (part "RESISTOR0603"))
    )
    (comp (ref "TCK")
      (value "TPSQB1,27")
      (footprint "eagle-import:B1,27")
      (libsource (lib "eagle-import") (part "TPSQB1,27"))
    )
    (comp (ref "TDI")
      (value "TPSQB1,27")
      (footprint "eagle-import:B1,27")
      (libsource (lib "eagle-import") (part "TPSQB1,27"))
    )
    (comp (ref "TDO")
      (value "TPSQB1,27")
      (footprint "eagle-import:B1,27")
      (libsource (lib "eagle-import") (part "TPSQB1,27"))
    )
    (comp (ref "TMS")
      (value "TPSQB1,27")
      (footprint "eagle-import:B1,27")
      (libsource (lib "eagle-import") (part "TPSQB1,27"))
    )
    (comp (ref "TP1")
      (value "TPSQB1,27")
      (footprint "eagle-import:B1,27")
      (libsource (lib "eagle-import") (part "TPSQB1,27"))
    )
    (comp (ref "TP5")
      (value "TPB0,65")
      (footprint "eagle-import:BEAGLEBONE_BLUE_B0,65")
      (libsource (lib "eagle-import") (part "TPB0,65"))
    )
    (comp (ref "TP12")
      (value "TPSQB1,27")
      (footprint "eagle-import:B1,27")
      (libsource (lib "eagle-import") (part "TPSQB1,27"))
    )
    (comp (ref "TRSTN")
      (value "TPSQB1,27")
      (footprint "eagle-import:B1,27")
      (libsource (lib "eagle-import") (part "TPSQB1,27"))
    )
    (comp (ref "U1")
      (value "TCAN1051HV")
      (footprint "eagle-import:BEAGLEBONE_BLUE_D8")
      (fields
        (field (name "MANUFACTURER") "Texas Instruments")
        (field (name "MANUFACTURER_PART_NUMBER") "TCAN1051HVD")
      )
      (libsource (lib "eagle-import") (part "TCAN1051HV"))
    )
    (comp (ref "U5")
      (value "24LC_32AT-I/OT")
      (footprint "eagle-import:SOT95P290X145-5N")
      (fields (field (name "MPN") "24LC32AT-I/OT"))
      (libsource (lib "eagle-import") (part "24LC_32AT-I/OT"))
    )
    (comp (ref "U6")
      (value "SN74LVC1G07_DCK_5")
      (footprint "eagle-import:BEAGLEBONE_BLUE_DCK5")
      (fields
        (field (name "GENERIC_PART_NUMBER") "SN74LVC1G07")
        (field (name "MANUFACTURER") "Texas Instruments")
        (field (name "MANUFACTURER_PART_NUMBER") "sn74lvc1g07_dck_5")
      )
      (libsource (lib "eagle-import") (part "SN74LVC1G07_DCK_5"))
    )
    (comp (ref "U13")
      (value "EMMC")
      (footprint "eagle-import:MICRON_EMMC_153")
      (libsource (lib "eagle-import") (part "EMMC04G-S100-B08U"))
    )
    (comp (ref "WP")
      (value "GHI2_TESTPAD/W_HOLE_1X1")
      (footprint "eagle-import:GHI2_TESTPAD_W_HOLE_1X1")
      (libsource (lib "eagle-import") (part "GHI2_TESTPAD/W_HOLE_1X1"))
    )
    (comp (ref "X2")
      (value "SCHA5B0200")
      (footprint "eagle-import:SCHA5B0200")
      (libsource (lib "eagle-import") (part "SCHA5B0200(ALPS_USD)"))
    )
    (comp (ref "Y1")
      (value "24 MHz")
      (footprint "eagle-import:CRYSTAL_5X3.2MM")
      (libsource (lib "eagle-import") (part "CRYSTAL_5X3.2MM"))
    )
    (comp (ref "Y2")
      (value "32.768kHz")
      (footprint "eagle-import:CRYSTAL_3.2X1.5")
      (libsource (lib "eagle-import") (part "CRYSTAL_3.2X1.5"))
    )
    (comp (ref "0")
      (value "BLUE")
      (footprint "eagle-import:BEAGLEBONE_BLUE_LED-0603")
      (libsource (lib "eagle-import") (part "LED0603"))
    )
    (comp (ref "1")
      (value "BLUE")
      (footprint "eagle-import:BEAGLEBONE_BLUE_LED-0603")
      (libsource (lib "eagle-import") (part "LED0603"))
    )
    (comp (ref "2")
      (value "BLUE")
      (footprint "eagle-import:BEAGLEBONE_BLUE_LED-0603")
      (libsource (lib "eagle-import") (part "LED0603"))
    )
    (comp (ref "3")
      (value "BLUE")
      (footprint "eagle-import:BEAGLEBONE_BLUE_LED-0603")
      (libsource (lib "eagle-import") (part "LED0603"))
    )
    (comp (ref "5VREG")
      (value "AP1509SOIC-8-TIGHT")
      (footprint "eagle-import:BEAGLEBONE_BLUE_SO08-TIGHT")
      (libsource (lib "eagle-import") (part "AP1509SOIC-8-TIGHT"))
    )
    (comp (ref "6VREG")
      (value "AOZ1284")
      (footprint "eagle-import:SO08-EXPOSED")
      (libsource (lib "eagle-import") (part "AOZ1284"))
    )
    (comp (ref "12V")
      (value "PJ-102B_POWER_CON")
      (footprint "eagle-import:PJ-102B_POWER_CON")
      (libsource (lib "eagle-import") (part "PJ-102B_POWER_CON"))
    )
    (comp (ref "ADC")
      (value "JST_SH_6")
      (footprint "eagle-import:JST_SH_6")
      (libsource (lib "eagle-import") (part "JST_SH_6"))
    )
    (comp (ref "B0")
      (value "RED")
      (footprint "eagle-import:LED-0603")
      (libsource (lib "eagle-import") (part "SparkFun-LED_LED0603"))
    )
    (comp (ref "B1")
      (value "GREEN")
      (footprint "eagle-import:LED-0603")
      (libsource (lib "eagle-import") (part "SparkFun-LED_LED0603"))
    )
    (comp (ref "B2")
      (value "GREEN")
      (footprint "eagle-import:LED-0603")
      (libsource (lib "eagle-import") (part "SparkFun-LED_LED0603"))
    )
    (comp (ref "B3")
      (value "GREEN")
      (footprint "eagle-import:LED-0603")
      (libsource (lib "eagle-import") (part "SparkFun-LED_LED0603"))
    )
    (comp (ref "BAL")
      (value "BQ29209")
      (footprint "eagle-import:8-SON_3X3MM")
      (libsource (lib "eagle-import") (part "BQ29209"))
    )
    (comp (ref "BMP")
      (value "BMP280")
      (footprint "eagle-import:BMP280")
      (libsource (lib "eagle-import") (part "BMP280"))
    )
    (comp (ref "C1")
      (value "0.1uF")
      (footprint "eagle-import:0402-CAP")
      (libsource (lib "eagle-import") (part "Strawson_Eagle_Lib_CAP0402-CAP"))
    )
    (comp (ref "C2")
      (value "0.1uF")
      (footprint "eagle-import:0402-CAP")
      (libsource (lib "eagle-import") (part "Strawson_Eagle_Lib_CAP0402-CAP"))
    )
    (comp (ref "C3")
      (value "10uF")
      (footprint "eagle-import:0805")
      (libsource (lib "eagle-import") (part "CAP0805"))
    )
    (comp (ref "C4")
      (value "1uF")
      (footprint "eagle-import:0402-CAP")
      (libsource (lib "eagle-import") (part "Strawson_Eagle_Lib_CAP0402-CAP"))
    )
    (comp (ref "C5")
      (value "10uF")
      (footprint "eagle-import:0805")
      (libsource (lib "eagle-import") (part "CAP0805"))
    )
    (comp (ref "C6")
      (value "0.1uF")
      (footprint "eagle-import:0402-CAP")
      (libsource (lib "eagle-import") (part "Strawson_Eagle_Lib_CAP0402-CAP"))
    )
    (comp (ref "C7")
      (value "10uF")
      (footprint "eagle-import:0805")
      (libsource (lib "eagle-import") (part "CAP0805"))
    )
    (comp (ref "C8")
      (value "0.1uF")
      (footprint "eagle-import:0402-CAP")
      (libsource (lib "eagle-import") (part "Strawson_Eagle_Lib_CAP0402-CAP"))
    )
    (comp (ref "C9")
      (value "0.1uF")
      (footprint "eagle-import:0402-CAP")
      (libsource (lib "eagle-import") (part "Strawson_Eagle_Lib_CAP0402-CAP"))
    )
    (comp (ref "C10")
      (value "1uF")
      (footprint "eagle-import:0402-CAP")
      (libsource (lib "eagle-import") (part "Strawson_Eagle_Lib_CAP0402-CAP"))
    )
    (comp (ref "C11")
      (value "100uF 16V")
      (footprint "eagle-import:PANASONIC_D")
      (libsource (lib "eagle-import") (part "CPOL-USD"))
    )
    (comp (ref "C12")
      (value "10uF")
      (footprint "eagle-import:0805")
      (libsource (lib "eagle-import") (part "CAP0805"))
    )
    (comp (ref "C13")
      (value "0.1uF")
      (footprint "eagle-import:0402-CAP")
      (libsource (lib "eagle-import") (part "Strawson_Eagle_Lib_CAP0402-CAP"))
    )
    (comp (ref "C14")
      (value "0.1uF")
      (footprint "eagle-import:0402-CAP")
      (libsource (lib "eagle-import") (part "Strawson_Eagle_Lib_CAP0402-CAP"))
    )
    (comp (ref "C15")
      (value "0.1uF")
      (footprint "eagle-import:0402-CAP")
      (libsource (lib "eagle-import") (part "Strawson_Eagle_Lib_CAP0402-CAP"))
    )
    (comp (ref "C16")
      (value "10uF")
      (footprint "eagle-import:0805")
      (libsource (lib "eagle-import") (part "CAP0805"))
    )
    (comp (ref "C17")
      (value "0.1uF")
      (footprint "eagle-import:0402-CAP")
      (libsource (lib "eagle-import") (part "Strawson_Eagle_Lib_CAP0402-CAP"))
    )
    (comp (ref "C18")
      (value "0.1uF")
      (footprint "eagle-import:0402-CAP")
      (libsource (lib "eagle-import") (part "Strawson_Eagle_Lib_CAP0402-CAP"))
    )
    (comp (ref "C19")
      (value "0.1uF")
      (footprint "eagle-import:0402-CAP")
      (libsource (lib "eagle-import") (part "Strawson_Eagle_Lib_CAP0402-CAP"))
    )
    (comp (ref "C20")
      (value "10uF")
      (footprint "eagle-import:0805")
      (libsource (lib "eagle-import") (part "CAP0805"))
    )
    (comp (ref "C21")
      (value "0.1uF")
      (footprint "eagle-import:0402-CAP")
      (libsource (lib "eagle-import") (part "Strawson_Eagle_Lib_CAP0402-CAP"))
    )
    (comp (ref "C22")
      (value "0.1uF")
      (footprint "eagle-import:0402-CAP")
      (libsource (lib "eagle-import") (part "Strawson_Eagle_Lib_CAP0402-CAP"))
    )
    (comp (ref "C23")
      (value "10uF")
      (footprint "eagle-import:0805")
      (libsource (lib "eagle-import") (part "CAP0805"))
    )
    (comp (ref "C24")
      (value "0.1uF")
      (footprint "eagle-import:0402-CAP")
      (libsource (lib "eagle-import") (part "Strawson_Eagle_Lib_CAP0402-CAP"))
    )
    (comp (ref "C25")
      (value "10uF")
      (footprint "eagle-import:0805")
      (libsource (lib "eagle-import") (part "CAP0805"))
    )
    (comp (ref "C26")
      (value "10uF")
      (footprint "eagle-import:0805")
      (libsource (lib "eagle-import") (part "CAP0805"))
    )
    (comp (ref "CAN")
      (value "JST_SH_4")
      (footprint "eagle-import:JST_SH_4_SMD")
      (libsource (lib "eagle-import") (part "JST_SH_4"))
    )
    (comp (ref "CHG")
      (value "GRN")
      (footprint "eagle-import:LED-0603")
      (libsource (lib "eagle-import") (part "SparkFun-LED_LED0603"))
    )
    (comp (ref "CHGIC")
      (value "MP2615")
      (footprint "eagle-import:MP2615")
      (libsource (lib "eagle-import") (part "MP2615"))
    )
    (comp (ref "D1")
      (value "DIODE_SOD-123FL")
      (footprint "eagle-import:ADAFRUIT_SOD-123FL")
      (libsource (lib "eagle-import") (part "DIODE_SOD-123FL"))
    )
    (comp (ref "D2")
      (value "DIODE_SOD-123FL")
      (footprint "eagle-import:ADAFRUIT_SOD-123FL")
      (libsource (lib "eagle-import") (part "DIODE_SOD-123FL"))
    )
    (comp (ref "D3")
      (value "DIODE_SOD-123FL")
      (footprint "eagle-import:ADAFRUIT_SOD-123FL")
      (libsource (lib "eagle-import") (part "DIODE_SOD-123FL"))
    )
    (comp (ref "D9")
      (value "DIODEDO214AA")
      (footprint "eagle-import:DO-214AA")
      (libsource (lib "eagle-import") (part "DIODEDO214AA"))
    )
    (comp (ref "DSM2")
      (value "JST_ZH_3")
      (footprint "eagle-import:JST_ZH_3")
      (libsource (lib "eagle-import") (part "JST_ZH_3"))
    )
    (comp (ref "E1")
      (value "JST_SH_4")
      (footprint "eagle-import:JST_SH_4_SMD")
      (libsource (lib "eagle-import") (part "JST_SH_4"))
    )
    (comp (ref "E2")
      (value "JST_SH_4")
      (footprint "eagle-import:JST_SH_4_SMD")
      (libsource (lib "eagle-import") (part "JST_SH_4"))
    )
    (comp (ref "E3")
      (value "JST_SH_4")
      (footprint "eagle-import:JST_SH_4_SMD")
      (libsource (lib "eagle-import") (part "JST_SH_4"))
    )
    (comp (ref "E4")
      (value "JST_SH_4")
      (footprint "eagle-import:JST_SH_4_SMD")
      (libsource (lib "eagle-import") (part "JST_SH_4"))
    )
    (comp (ref "G")
      (value "GREEN")
      (footprint "eagle-import:BEAGLEBONE_BLUE_LED-0603")
      (libsource (lib "eagle-import") (part "LED0603"))
    )
    (comp (ref "GP0")
      (value "JST_SH_6")
      (footprint "eagle-import:JST_SH_6")
      (libsource (lib "eagle-import") (part "JST_SH_6"))
    )
    (comp (ref "GP1")
      (value "JST_SH_6")
      (footprint "eagle-import:JST_SH_6")
      (libsource (lib "eagle-import") (part "JST_SH_6"))
    )
    (comp (ref "GPS")
      (value "JST_SH_6")
      (footprint "eagle-import:JST_SH_6")
      (libsource (lib "eagle-import") (part "JST_SH_6"))
    )
    (comp (ref "H1")
      (value "TB6612FNG")
      (footprint "eagle-import:SSOP24")
      (libsource (lib "eagle-import") (part "TB6612FNG"))
    )
    (comp (ref "H2")
      (value "TB6612FNG")
      (footprint "eagle-import:SSOP24")
      (libsource (lib "eagle-import") (part "TB6612FNG"))
    )
    (comp (ref "I2C")
      (value "JST_SH_4")
      (footprint "eagle-import:JST_SH_4_SMD")
      (libsource (lib "eagle-import") (part "JST_SH_4"))
    )
    (comp (ref "IMU")
      (value "MPU-9250")
      (footprint "eagle-import:QFN24G-0.4-3X3MM")
      (libsource (lib "eagle-import") (part "MPU-9250"))
    )
    (comp (ref "J2")
      (value "STRAWSON_EAGLE_LIB_SERVO_HEADERS_8X")
      (footprint "eagle-import:STRAWSON_EAGLE_LIB_3X8_0.1__HEADER")
      (libsource (lib "eagle-import") (part "STRAWSON_EAGLE_LIB_SERVO_HEADERS_8X"))
    )
    (comp (ref "L1")
      (value "6.8uH")
      (footprint "eagle-import:SRN6045")
      (libsource (lib "eagle-import") (part "INDUCTORBOURNS_SRN6045"))
    )
    (comp (ref "L2")
      (value "6.8uH")
      (footprint "eagle-import:SRN6045")
      (libsource (lib "eagle-import") (part "INDUCTORBOURNS_SRN6045"))
    )
    (comp (ref "L3")
      (value "3.6 uH")
      (footprint "eagle-import:8X8MM_INDUCTOR")
      (libsource (lib "eagle-import") (part "INDUCTOR"))
    )
    (comp (ref "LIPO")
      (value "BATTERY")
      (footprint "eagle-import:JST_XH_3-PIN")
      (libsource (lib "eagle-import") (part "JST_XH_3-PIN"))
    )
    (comp (ref "M1")
      (value "JST_ZH_2")
      (footprint "eagle-import:JST_ZH_2")
      (libsource (lib "eagle-import") (part "JST_ZH_2"))
    )
    (comp (ref "M2")
      (value "JST_ZH_2")
      (footprint "eagle-import:JST_ZH_2")
      (libsource (lib "eagle-import") (part "JST_ZH_2"))
    )
    (comp (ref "M3")
      (value "JST_ZH_2")
      (footprint "eagle-import:JST_ZH_2")
      (libsource (lib "eagle-import") (part "JST_ZH_2"))
    )
    (comp (ref "M4")
      (value "JST_ZH_2")
      (footprint "eagle-import:JST_ZH_2")
      (libsource (lib "eagle-import") (part "JST_ZH_2"))
    )
    (comp (ref "MOD")
      (value "SWITCH-MOMENTARY-2SMD-1101NE")
      (footprint "eagle-import:TACTILE-SWITCH-1101NE")
      (libsource (lib "eagle-import") (part "SWITCH-MOMENTARY-2SMD-1101NE"))
    )
    (comp (ref "PAU")
      (value "SWITCH-MOMENTARY-2SMD-1101NE")
      (footprint "eagle-import:TACTILE-SWITCH-1101NE")
      (libsource (lib "eagle-import") (part "SWITCH-MOMENTARY-2SMD-1101NE"))
    )
    (comp (ref "POW")
      (value "SWITCH-MOMENTARY-2SMD-1101NE")
      (footprint "eagle-import:TACTILE-SWITCH-1101NE")
      (libsource (lib "eagle-import") (part "SWITCH-MOMENTARY-2SMD-1101NE"))
    )
    (comp (ref "PROT")
      (value "S-8261")
      (footprint "eagle-import:SOT-236")
      (libsource (lib "eagle-import") (part "S-8261"))
    )
    (comp (ref "PWR")
      (value "JST_SH_4")
      (footprint "eagle-import:JST_SH_4_SMD")
      (libsource (lib "eagle-import") (part "JST_SH_4"))
    )
    (comp (ref "Q1")
      (value "MOSFET-N")
      (footprint "eagle-import:SO08-TIGHT")
      (libsource (lib "eagle-import") (part "MOSFET-NCHANNEL"))
    )
    (comp (ref "R")
      (value "RED")
      (footprint "eagle-import:BEAGLEBONE_BLUE_LED-0603")
      (libsource (lib "eagle-import") (part "LED0603"))
    )
    (comp (ref "R1")
      (value "47k")
      (footprint "eagle-import:0402-RES")
      (libsource (lib "eagle-import") (part "RESISTOR0402-RES"))
    )
    (comp (ref "R3")
      (value "1k")
      (footprint "eagle-import:0402-RES")
      (libsource (lib "eagle-import") (part "RESISTOR0402-RES"))
    )
    (comp (ref "R4")
      (value "0.1")
      (footprint "eagle-import:0603-RES")
      (libsource (lib "eagle-import") (part "RESISTOR0603"))
    )
    (comp (ref "R5")
      (value "10k")
      (footprint "eagle-import:0402-RES")
      (libsource (lib "eagle-import") (part "RESISTOR0402-RES"))
    )
    (comp (ref "R6")
      (value "10k")
      (footprint "eagle-import:0402-RES")
      (libsource (lib "eagle-import") (part "RESISTOR0402-RES"))
    )
    (comp (ref "R7")
      (value "4.7k")
      (footprint "eagle-import:0402-RES")
      (libsource (lib "eagle-import") (part "RESISTOR0402-RES"))
    )
    (comp (ref "R8")
      (value "10k")
      (footprint "eagle-import:0402-RES")
      (libsource (lib "eagle-import") (part "RESISTOR0402-RES"))
    )
    (comp (ref "R10")
      (value "4.7k")
      (footprint "eagle-import:0402-RES")
      (libsource (lib "eagle-import") (part "RESISTOR0402-RES"))
    )
    (comp (ref "R11")
      (value "4.7k")
      (footprint "eagle-import:0402-RES")
      (libsource (lib "eagle-import") (part "RESISTOR0402-RES"))
    )
    (comp (ref "R12")
      (value "4.7k")
      (footprint "eagle-import:0402-RES")
      (libsource (lib "eagle-import") (part "RESISTOR0402-RES"))
    )
    (comp (ref "R13")
      (value "4.7k")
      (footprint "eagle-import:0402-RES")
      (libsource (lib "eagle-import") (part "RESISTOR0402-RES"))
    )
    (comp (ref "R14")
      (value "4.7k")
      (footprint "eagle-import:0402-RES")
      (libsource (lib "eagle-import") (part "RESISTOR0402-RES"))
    )
    (comp (ref "R19")
      (value "47k")
      (footprint "eagle-import:0402-RES")
      (libsource (lib "eagle-import") (part "RESISTOR0402-RES"))
    )
    (comp (ref "R21")
      (value "240")
      (footprint "eagle-import:0402-RES")
      (libsource (lib "eagle-import") (part "RESISTOR0402-RES"))
    )
    (comp (ref "R22")
      (value "240")
      (footprint "eagle-import:0402-RES")
      (libsource (lib "eagle-import") (part "RESISTOR0402-RES"))
    )
    (comp (ref "R25")
      (value "4.7k")
      (footprint "eagle-import:0402-RES")
      (libsource (lib "eagle-import") (part "RESISTOR0402-RES"))
    )
    (comp (ref "R27")
      (value "150")
      (footprint "eagle-import:0402-RES")
      (libsource (lib "eagle-import") (part "RESISTOR0402-RES"))
    )
    (comp (ref "R28")
      (value "150")
      (footprint "eagle-import:0402-RES")
      (libsource (lib "eagle-import") (part "RESISTOR0402-RES"))
    )
    (comp (ref "R29")
      (value "240")
      (footprint "eagle-import:0402-RES")
      (libsource (lib "eagle-import") (part "RESISTOR0402-RES"))
    )
    (comp (ref "R30")
      (value "240")
      (footprint "eagle-import:0402-RES")
      (libsource (lib "eagle-import") (part "RESISTOR0402-RES"))
    )
    (comp (ref "R31")
      (value "240")
      (footprint "eagle-import:0402-RES")
      (libsource (lib "eagle-import") (part "RESISTOR0402-RES"))
    )
    (comp (ref "R32")
      (value "240")
      (footprint "eagle-import:0402-RES")
      (libsource (lib "eagle-import") (part "RESISTOR0402-RES"))
    )
    (comp (ref "R33")
      (value "240")
      (footprint "eagle-import:0402-RES")
      (libsource (lib "eagle-import") (part "RESISTOR0402-RES"))
    )
    (comp (ref "R34")
      (value "150")
      (footprint "eagle-import:0402-RES")
      (libsource (lib "eagle-import") (part "RESISTOR0402-RES"))
    )
    (comp (ref "R36")
      (value "4.7k")
      (footprint "eagle-import:0402-RES")
      (libsource (lib "eagle-import") (part "RESISTOR0402-RES"))
    )
    (comp (ref "R37")
      (value "4.7k")
      (footprint "eagle-import:0402-RES")
      (libsource (lib "eagle-import") (part "RESISTOR0402-RES"))
    )
    (comp (ref "R38")
      (value "4.7k")
      (footprint "eagle-import:0402-RES")
      (libsource (lib "eagle-import") (part "RESISTOR0402-RES"))
    )
    (comp (ref "R39")
      (value "4.7k")
      (footprint "eagle-import:0402-RES")
      (libsource (lib "eagle-import") (part "RESISTOR0402-RES"))
    )
    (comp (ref "R40")
      (value "4.7k")
      (footprint "eagle-import:0402-RES")
      (libsource (lib "eagle-import") (part "RESISTOR0402-RES"))
    )
    (comp (ref "R41")
      (value "4.7k")
      (footprint "eagle-import:0402-RES")
      (libsource (lib "eagle-import") (part "RESISTOR0402-RES"))
    )
    (comp (ref "R42")
      (value "4.7k")
      (footprint "eagle-import:0402-RES")
      (libsource (lib "eagle-import") (part "RESISTOR0402-RES"))
    )
    (comp (ref "R43")
      (value "4.7k")
      (footprint "eagle-import:0402-RES")
      (libsource (lib "eagle-import") (part "RESISTOR0402-RES"))
    )
    (comp (ref "R44")
      (value "1k")
      (footprint "eagle-import:0402-RES")
      (libsource (lib "eagle-import") (part "RESISTOR0402-RES"))
    )
    (comp (ref "R45")
      (value "47k")
      (footprint "eagle-import:0402-RES")
      (libsource (lib "eagle-import") (part "RESISTOR0402-RES"))
    )
    (comp (ref "R46")
      (value "1K")
      (footprint "eagle-import:0402-RES")
      (libsource (lib "eagle-import") (part "RESISTOR0402-RES"))
    )
    (comp (ref "R47")
      (value "100k")
      (footprint "eagle-import:0402-RES")
      (libsource (lib "eagle-import") (part "RESISTOR0402-RES"))
    )
    (comp (ref "R48")
      (value "10k")
      (footprint "eagle-import:0402-RES")
      (libsource (lib "eagle-import") (part "RESISTOR0402-RES"))
    )
    (comp (ref "R49")
      (value "65k")
      (footprint "eagle-import:0402-RES")
      (libsource (lib "eagle-import") (part "RESISTOR0402-RES"))
    )
    (comp (ref "R50")
      (value "4.7k")
      (footprint "eagle-import:0402-RES")
      (libsource (lib "eagle-import") (part "RESISTOR0402-RES"))
    )
    (comp (ref "R51")
      (value "4.7k")
      (footprint "eagle-import:0402-RES")
      (libsource (lib "eagle-import") (part "RESISTOR0402-RES"))
    )
    (comp (ref "R52")
      (value "4.7k")
      (footprint "eagle-import:0402-RES")
      (libsource (lib "eagle-import") (part "RESISTOR0402-RES"))
    )
    (comp (ref "R53")
      (value "4.7k")
      (footprint "eagle-import:0402-RES")
      (libsource (lib "eagle-import") (part "RESISTOR0402-RES"))
    )
    (comp (ref "R61")
      (value "1K")
      (footprint "eagle-import:0402-RES")
      (libsource (lib "eagle-import") (part "RESISTOR0402-RES"))
    )
    (comp (ref "R62")
      (value "1K")
      (footprint "eagle-import:0402-RES")
      (libsource (lib "eagle-import") (part "RESISTOR0402-RES"))
    )
    (comp (ref "R63")
      (value "1K")
      (footprint "eagle-import:0402-RES")
      (libsource (lib "eagle-import") (part "RESISTOR0402-RES"))
    )
    (comp (ref "R64")
      (value "1K")
      (footprint "eagle-import:0402-RES")
      (libsource (lib "eagle-import") (part "RESISTOR0402-RES"))
    )
    (comp (ref "R91")
      (value "240")
      (footprint "eagle-import:0402-RES")
      (libsource (lib "eagle-import") (part "RESISTOR0402-RES"))
    )
    (comp (ref "R107")
      (value ".1, 0805")
      (footprint "eagle-import:R0805")
      (libsource (lib "eagle-import") (part "R-US_R0805"))
    )
    (comp (ref "RST")
      (value "SWITCH-MOMENTARY-2SMD-1101NE")
      (footprint "eagle-import:TACTILE-SWITCH-1101NE")
      (libsource (lib "eagle-import") (part "SWITCH-MOMENTARY-2SMD-1101NE"))
    )
    (comp (ref "S1.1")
      (value "JST_SH_6")
      (footprint "eagle-import:JST_SH_6")
      (libsource (lib "eagle-import") (part "JST_SH_6"))
    )
    (comp (ref "S1.2")
      (value "JST_SH_6")
      (footprint "eagle-import:JST_SH_6")
      (libsource (lib "eagle-import") (part "JST_SH_6"))
    )
    (comp (ref "SD")
      (value "SWITCH-MOMENTARY-2SMD-1101NE")
      (footprint "eagle-import:TACTILE-SWITCH-1101NE")
      (libsource (lib "eagle-import") (part "SWITCH-MOMENTARY-2SMD-1101NE"))
    )
    (comp (ref "UT0")
      (value "JST_SH_4")
      (footprint "eagle-import:JST_SH_4_SMD")
      (libsource (lib "eagle-import") (part "JST_SH_4"))
    )
    (comp (ref "UT1")
      (value "JST_SH_4")
      (footprint "eagle-import:JST_SH_4_SMD")
      (libsource (lib "eagle-import") (part "JST_SH_4"))
    )
    (comp (ref "UT5")
      (value "JST_SH_4")
      (footprint "eagle-import:JST_SH_4_SMD")
      (libsource (lib "eagle-import") (part "JST_SH_4"))
    )
    (comp (ref "WIFI")
      (value "GREEN")
      (footprint "eagle-import:BEAGLEBONE_BLUE_LED-0603")
      (libsource (lib "eagle-import") (part "LED0603"))
    )
  )
  (nets
    (net (code "1") (name "3.3V") (class "Default")
      (node (ref "BMP") (pin "2") (pinfunction "CSB_2") (pintype "input"))
      (node (ref "BMP") (pin "6") (pinfunction "VDDIO_6") (pintype "input"))
      (node (ref "BMP") (pin "8") (pinfunction "VDD_8") (pintype "power_in"))
      (node (ref "C13") (pin "1") (pinfunction "1_1") (pintype "passive"))
      (node (ref "C16") (pin "1") (pinfunction "1_1") (pintype "passive"))
      (node (ref "C2") (pin "2") (pinfunction "2_2") (pintype "passive"))
      (node (ref "C27") (pin "1") (pinfunction "1_1") (pintype "passive"))
      (node (ref "C28") (pin "1") (pinfunction "1_1") (pintype "passive"))
      (node (ref "C34") (pin "2") (pinfunction "2_2") (pintype "passive"))
      (node (ref "C35") (pin "2") (pinfunction "2_2") (pintype "passive"))
      (node (ref "C37") (pin "1") (pinfunction "1_1") (pintype "passive"))
      (node (ref "C38") (pin "1") (pinfunction "1_1") (pintype "passive"))
      (node (ref "C39") (pin "1") (pinfunction "1_1") (pintype "passive"))
      (node (ref "C40") (pin "1") (pinfunction "1_1") (pintype "passive"))
      (node (ref "C41") (pin "1") (pinfunction "1_1") (pintype "passive"))
      (node (ref "C49") (pin "2") (pinfunction "2_2") (pintype "passive"))
      (node (ref "C51") (pin "2") (pinfunction "2_2") (pintype "passive"))
      (node (ref "C53") (pin "1") (pinfunction "1_1") (pintype "passive"))
      (node (ref "C56") (pin "1") (pinfunction "1_1") (pintype "passive"))
      (node (ref "C59") (pin "1") (pinfunction "1_1") (pintype "passive"))
      (node (ref "C8") (pin "1") (pinfunction "1_1") (pintype "passive"))
      (node (ref "C9") (pin "2") (pinfunction "2_2") (pintype "passive"))
      (node (ref "CAN") (pin "2") (pinfunction "2_2") (pintype "bidirectional"))
      (node (ref "DSM2") (pin "P$1") (pinfunction "1_P$1") (pintype "bidirectional"))
      (node (ref "E1") (pin "2") (pinfunction "2_2") (pintype "bidirectional"))
      (node (ref "E2") (pin "2") (pinfunction "2_2") (pintype "bidirectional"))
      (node (ref "E3") (pin "2") (pinfunction "2_2") (pintype "bidirectional"))
      (node (ref "E4") (pin "2") (pinfunction "2_2") (pintype "bidirectional"))
      (node (ref "GP0") (pin "2") (pinfunction "2_2") (pintype "bidirectional"))
      (node (ref "GP1") (pin "2") (pinfunction "2_2") (pintype "bidirectional"))
      (node (ref "H1") (pin "20") (pinfunction "VCC_20") (pintype "bidirectional"))
      (node (ref "H2") (pin "20") (pinfunction "VCC_20") (pintype "bidirectional"))
      (node (ref "I2C") (pin "2") (pinfunction "2_2") (pintype "bidirectional"))
      (node (ref "IMU") (pin "1") (pinfunction "RESV_1") (pintype "bidirectional"))
      (node (ref "IMU") (pin "13") (pinfunction "VDD_13") (pintype "bidirectional"))
      (node (ref "IMU") (pin "22") (pinfunction "NCS_22") (pintype "bidirectional"))
      (node (ref "IMU") (pin "8") (pinfunction "VDDIO_8") (pintype "bidirectional"))
      (node (ref "PWR") (pin "3") (pinfunction "3_3") (pintype "bidirectional"))
      (node (ref "R10") (pin "1") (pinfunction "1_1") (pintype "passive"))
      (node (ref "R109") (pin "1") (pinfunction "1_1") (pintype "passive"))
      (node (ref "R11") (pin "2") (pinfunction "2_2") (pintype "passive"))
      (node (ref "R116") (pin "2") (pinfunction "2_2") (pintype "passive"))
      (node (ref "R118") (pin "2") (pinfunction "2_2") (pintype "passive"))
      (node (ref "R12") (pin "2") (pinfunction "2_2") (pintype "passive"))
      (node (ref "R120") (pin "2") (pinfunction "2_2") (pintype "passive"))
      (node (ref "R122") (pin "2") (pinfunction "2_2") (pintype "passive"))
      (node (ref "R13") (pin "1") (pinfunction "1_1") (pintype "passive"))
      (node (ref "R140") (pin "2") (pinfunction "2_2") (pintype "passive"))
      (node (ref "R2") (pin "2") (pinfunction "2_2") (pintype "passive"))
      (node (ref "R23") (pin "2") (pinfunction "2_2") (pintype "passive"))
      (node (ref "R26") (pin "2") (pinfunction "2_2") (pintype "passive"))
      (node (ref "R35") (pin "2") (pinfunction "2_2") (pintype "passive"))
      (node (ref "R54") (pin "2") (pinfunction "2_2") (pintype "passive"))
      (node (ref "R55") (pin "2") (pinfunction "2_2") (pintype "passive"))
      (node (ref "R56") (pin "2") (pinfunction "2_2") (pintype "passive"))
      (node (ref "R57") (pin "2") (pinfunction "2_2") (pintype "passive"))
      (node (ref "R58") (pin "2") (pinfunction "2_2") (pintype "passive"))
      (node (ref "R60") (pin "2") (pinfunction "2_2") (pintype "passive"))
      (node (ref "R65") (pin "2") (pinfunction "2_2") (pintype "passive"))
      (node (ref "R66") (pin "2") (pinfunction "2_2") (pintype "passive"))
      (node (ref "R67") (pin "2") (pinfunction "2_2") (pintype "passive"))
      (node (ref "R68") (pin "2") (pinfunction "2_2") (pintype "passive"))
      (node (ref "R69") (pin "2") (pinfunction "2_2") (pintype "passive"))
      (node (ref "R70") (pin "2") (pinfunction "2_2") (pintype "passive"))
      (node (ref "R71") (pin "2") (pinfunction "2_2") (pintype "passive"))
      (node (ref "R72") (pin "2") (pinfunction "2_2") (pintype "passive"))
      (node (ref "R73") (pin "2") (pinfunction "2_2") (pintype "passive"))
      (node (ref "R74") (pin "2") (pinfunction "2_2") (pintype "passive"))
      (node (ref "R75") (pin "2") (pinfunction "2_2") (pintype "passive"))
      (node (ref "R94") (pin "2") (pinfunction "2_2") (pintype "passive"))
      (node (ref "S1.1") (pin "2") (pinfunction "2_2") (pintype "bidirectional"))
      (node (ref "S1.2") (pin "2") (pinfunction "2_2") (pintype "bidirectional"))
      (node (ref "SIP") (pin "U20") (pinfunction "VOUT_USER_3P3V_0_U20") (pintype "power_in"))
      (node (ref "SIP") (pin "V20") (pinfunction "VOUT_USER_3P3V_1_V20") (pintype "power_in"))
      (node (ref "U1") (pin "5") (pinfunction "VIO_5") (pintype "power_in"))
      (node (ref "U10") (pin "19") (pinfunction "VCCB_19") (pintype "bidirectional"))
      (node (ref "U13") (pin "C6") (pinfunction "VCCQ1_C6") (pintype "bidirectional"))
      (node (ref "U13") (pin "E6") (pinfunction "VCC1_E6") (pintype "bidirectional"))
      (node (ref "U13") (pin "F5") (pinfunction "VCC2_F5") (pintype "bidirectional"))
      (node (ref "U13") (pin "J10") (pinfunction "VCC3_J10") (pintype "bidirectional"))
      (node (ref "U13") (pin "K9") (pinfunction "VCC4_K9") (pintype "bidirectional"))
      (node (ref "U13") (pin "M4") (pinfunction "VCCQ2_M4") (pintype "bidirectional"))
      (node (ref "U13") (pin "N4") (pinfunction "VCCQ3_N4") (pintype "bidirectional"))
      (node (ref "U13") (pin "P3") (pinfunction "VCCQ4_P3") (pintype "bidirectional"))
      (node (ref "U13") (pin "P5") (pinfunction "VCCQ5_P5") (pintype "bidirectional"))
      (node (ref "U5") (pin "4") (pinfunction "VCC_4") (pintype "power_in"))
      (node (ref "U7") (pin "46") (pinfunction "VBAT_IN1_46") (pintype "bidirectional"))
      (node (ref "U7") (pin "47") (pinfunction "VBAT_IN2_47") (pintype "bidirectional"))
      (node (ref "U9") (pin "19") (pinfunction "VCCB_19") (pintype "bidirectional"))
      (node (ref "UT0") (pin "2") (pinfunction "2_2") (pintype "bidirectional"))
      (node (ref "UT1") (pin "2") (pinfunction "2_2") (pintype "bidirectional"))
      (node (ref "UT5") (pin "2") (pinfunction "2_2") (pintype "bidirectional"))
      (node (ref "X2") (pin "4") (pinfunction "VDD_4") (pintype "bidirectional"))
    )
    (net (code "2") (name "5.0V") (class "Default")
      (node (ref "5VREG") (pin "3") (pinfunction "FB_3") (pintype "power_in"))
      (node (ref "C5") (pin "1") (pinfunction "1_1") (pintype "passive"))
      (node (ref "C63") (pin "1") (pinfunction "1_1") (pintype "passive"))
      (node (ref "GPS") (pin "5") (pinfunction "5_5") (pintype "bidirectional"))
      (node (ref "L1") (pin "2") (pinfunction "2_2") (pintype "passive"))
      (node (ref "PWR") (pin "4") (pinfunction "4_4") (pintype "bidirectional"))
      (node (ref "R119") (pin "2") (pinfunction "2_2") (pintype "passive"))
      (node (ref "R95") (pin "2") (pinfunction "2_2") (pintype "passive"))
      (node (ref "SIP") (pin "Y5") (pinfunction "VIN_AC_0_Y5") (pintype "power_in"))
      (node (ref "SIP") (pin "Y6") (pinfunction "VIN_AC_1_Y6") (pintype "power_in"))
      (node (ref "U8") (pin "1") (pinfunction "EN_1") (pintype "input"))
      (node (ref "U8") (pin "5") (pinfunction "IN1_5") (pintype "input"))
    )
    (net (code "3") (name "32.768KHZ") (class "Default")
      (node (ref "OSC1") (pin "3") (pinfunction "OUT_3") (pintype "bidirectional"))
      (node (ref "U7") (pin "36") (pinfunction "EXT_32K_36") (pintype "bidirectional"))
    )
    (net (code "4") (name "AIN0") (class "Default")
      (node (ref "ADC") (pin "3") (pinfunction "3_3") (pintype "bidirectional"))
      (node (ref "SIP") (pin "B6") (pinfunction "AIN0_B6") (pintype "bidirectional"))
    )
    (net (code "5") (name "AIN1") (class "Default")
      (node (ref "ADC") (pin "4") (pinfunction "4_4") (pintype "bidirectional"))
      (node (ref "SIP") (pin "C7") (pinfunction "AIN1_C7") (pintype "bidirectional"))
    )
    (net (code "6") (name "AIN2") (class "Default")
      (node (ref "ADC") (pin "5") (pinfunction "5_5") (pintype "bidirectional"))
      (node (ref "SIP") (pin "B7") (pinfunction "AIN2_B7") (pintype "bidirectional"))
    )
    (net (code "7") (name "AIN3") (class "Default")
      (node (ref "ADC") (pin "6") (pinfunction "6_6") (pintype "bidirectional"))
      (node (ref "SIP") (pin "A7") (pinfunction "AIN3_A7") (pintype "bidirectional"))
    )
    (net (code "8") (name "BATT_LED_1") (class "Default")
      (node (ref "B0") (pin "A") (pinfunction "A_A") (pintype "passive"))
      (node (ref "SIP") (pin "U12") (pinfunction "GPIO0_27_U12_U12") (pintype "bidirectional"))
    )
    (net (code "9") (name "BATT_LED_2") (class "Default")
      (node (ref "B1") (pin "A") (pinfunction "A_A") (pintype "passive"))
      (node (ref "R143") (pin "2") (pinfunction "2_2") (pintype "passive"))
      (node (ref "SIP") (pin "T5") (pinfunction "LCD_DATA15_T5_T5") (pintype "bidirectional"))
    )
    (net (code "10") (name "BATT_LED_3") (class "Default")
      (node (ref "B2") (pin "A") (pinfunction "A_A") (pintype "passive"))
      (node (ref "SIP") (pin "V6") (pinfunction "GPIO1_29_V6_V6") (pintype "bidirectional"))
    )
    (net (code "11") (name "BATT_LED_4") (class "Default")
      (node (ref "B3") (pin "A") (pinfunction "A_A") (pintype "passive"))
      (node (ref "SIP") (pin "T11") (pinfunction "GPIO0_26_T11_T11") (pintype "bidirectional"))
    )
    (net (code "12") (name "BATT_MID") (class "Default")
      (node (ref "LIPO") (pin "P$2") (pinfunction "2_P$2") (pintype "passive"))
      (node (ref "R27") (pin "1") (pinfunction "1_1") (pintype "passive"))
      (node (ref "R30") (pin "1") (pinfunction "1_1") (pintype "passive"))
      (node (ref "R44") (pin "1") (pinfunction "1_1") (pintype "passive"))
    )
    (net (code "13") (name "BATT_MINUS") (class "Default")
      (node (ref "BAL") (pin "5") (pinfunction "GND_5") (pintype "bidirectional"))
      (node (ref "BAL") (pin "6") (pinfunction "CB_EN_6") (pintype "bidirectional"))
      (node (ref "C1") (pin "2") (pinfunction "2_2") (pintype "passive"))
      (node (ref "C15") (pin "1") (pinfunction "1_1") (pintype "passive"))
      (node (ref "C18") (pin "1") (pinfunction "1_1") (pintype "passive"))
      (node (ref "C19") (pin "2") (pinfunction "2_2") (pintype "passive"))
      (node (ref "LIPO") (pin "P$3") (pinfunction "3_P$3") (pintype "passive"))
      (node (ref "PROT") (pin "2") (pinfunction "VM_2") (pintype "bidirectional"))
      (node (ref "PROT") (pin "6") (pinfunction "VSS_6") (pintype "bidirectional"))
      (node (ref "Q1") (pin "1") (pinfunction "S_1") (pintype "passive"))
      (node (ref "Q1") (pin "2") (pinfunction "S_2") (pintype "passive"))
      (node (ref "Q1") (pin "3") (pinfunction "S_3") (pintype "passive"))
    )
    (net (code "14") (name "BT_AUD_CLK") (class "Default")
      (node (ref "R124") (pin "1") (pinfunction "1_1") (pintype "passive"))
      (node (ref "U10") (pin "1") (pinfunction "A1_1") (pintype "bidirectional"))
    )
    (net (code "15") (name "BT_AUD_FSYNC") (class "Default")
      (node (ref "R123") (pin "1") (pinfunction "1_1") (pintype "passive"))
      (node (ref "U10") (pin "3") (pinfunction "A2_3") (pintype "bidirectional"))
    )
    (net (code "16") (name "BT_AUD_IN") (class "Default")
      (node (ref "R97") (pin "1") (pinfunction "1_1") (pintype "passive"))
      (node (ref "U10") (pin "5") (pinfunction "A4_5") (pintype "bidirectional"))
    )
    (net (code "17") (name "BT_AUD_OUT") (class "Default")
      (node (ref "R100") (pin "1") (pinfunction "1_1") (pintype "passive"))
      (node (ref "U10") (pin "4") (pinfunction "A3_4") (pintype "bidirectional"))
    )
    (net (code "18") (name "BT_EN") (class "Default")
      (node (ref "SIP") (pin "K17") (pinfunction "K17_K17") (pintype "bidirectional"))
      (node (ref "U9") (pin "18") (pinfunction "B2_18") (pintype "bidirectional"))
    )
    (net (code "19") (name "BT_EN_1V8") (class "Default")
      (node (ref "R88") (pin "1") (pinfunction "1_1") (pintype "passive"))
      (node (ref "U7") (pin "41") (pinfunction "BT_EN_41") (pintype "bidirectional"))
      (node (ref "U9") (pin "3") (pinfunction "A2_3") (pintype "bidirectional"))
    )
    (net (code "20") (name "BT_HCI_CTS") (class "Default")
      (node (ref "R86") (pin "1") (pinfunction "1_1") (pintype "passive"))
      (node (ref "U10") (pin "8") (pinfunction "A7_8") (pintype "bidirectional"))
    )
    (net (code "21") (name "BT_HCI_RTS") (class "Default")
      (node (ref "R85") (pin "1") (pinfunction "1_1") (pintype "passive"))
      (node (ref "U10") (pin "9") (pinfunction "A8_9") (pintype "bidirectional"))
    )
    (net (code "22") (name "BT_HCI_RX") (class "Default")
      (node (ref "R96") (pin "1") (pinfunction "1_1") (pintype "passive"))
      (node (ref "U10") (pin "6") (pinfunction "A5_6") (pintype "bidirectional"))
    )
    (net (code "23") (name "BT_HCI_TX") (class "Default")
      (node (ref "R92") (pin "1") (pinfunction "1_1") (pintype "passive"))
      (node (ref "U10") (pin "7") (pinfunction "A6_7") (pintype "bidirectional"))
    )
    (net (code "24") (name "CANH") (class "Default")
      (node (ref "CAN") (pin "3") (pinfunction "3_3") (pintype "bidirectional"))
      (node (ref "R104") (pin "1") (pinfunction "1_1") (pintype "passive"))
      (node (ref "U1") (pin "7") (pinfunction "CANH_7") (pintype "bidirectional"))
    )
    (net (code "25") (name "CANL") (class "Default")
      (node (ref "CAN") (pin "4") (pinfunction "4_4") (pintype "bidirectional"))
      (node (ref "R104") (pin "2") (pinfunction "2_2") (pintype "passive"))
      (node (ref "U1") (pin "6") (pinfunction "CANL_6") (pintype "bidirectional"))
    )
    (net (code "26") (name "CGND") (class "Default")
      (node (ref "MGT1") (pin "P$1") (pinfunction "P$1_P$1") (pintype "bidirectional"))
      (node (ref "MGT2") (pin "P$1") (pinfunction "P$1_P$1") (pintype "bidirectional"))
      (node (ref "MGT3") (pin "P$1") (pinfunction "P$1_P$1") (pintype "bidirectional"))
      (node (ref "MGT4") (pin "P$1") (pinfunction "P$1_P$1") (pintype "bidirectional"))
      (node (ref "R107") (pin "2") (pinfunction "2_2") (pintype "passive"))
      (node (ref "X2") (pin "CGND1") (pinfunction "CGND1_CGND1") (pintype "bidirectional"))
      (node (ref "X2") (pin "CGND2") (pinfunction "CGND2_CGND2") (pintype "bidirectional"))
      (node (ref "X2") (pin "CGND3") (pinfunction "CGND3_CGND3") (pintype "bidirectional"))
      (node (ref "X2") (pin "CGND4") (pinfunction "CGND4_CGND4") (pintype "bidirectional"))
      (node (ref "X2") (pin "CGND5") (pinfunction "CGND5_CGND5") (pintype "bidirectional"))
      (node (ref "X2") (pin "CGND6") (pinfunction "CGND6_CGND6") (pintype "bidirectional"))
      (node (ref "X3") (pin "5") (pinfunction "CG1_5") (pintype "bidirectional"))
      (node (ref "X3") (pin "6") (pinfunction "CG2_6") (pintype "bidirectional"))
      (node (ref "X4") (pin "CGND1") (pinfunction "SGND1_CGND1") (pintype "bidirectional"))
      (node (ref "X4") (pin "CGND2") (pinfunction "SGND2_CGND2") (pintype "bidirectional"))
      (node (ref "X4") (pin "CGND3") (pinfunction "SGND3_CGND3") (pintype "bidirectional"))
      (node (ref "X4") (pin "CGND4") (pinfunction "SGND4_CGND4") (pintype "bidirectional"))
      (node (ref "X4") (pin "CGND5") (pinfunction "SGND5_CGND5") (pintype "bidirectional"))
      (node (ref "X4") (pin "CGND6") (pinfunction "SGND6_CGND6") (pintype "bidirectional"))
    )
    (net (code "27") (name "CHG_EN") (class "Default")
      (node (ref "CHGIC") (pin "6") (pinfunction "EN_6") (pintype "bidirectional"))
      (node (ref "R7") (pin "2") (pinfunction "2_2") (pintype "passive"))
      (node (ref "R8") (pin "1") (pinfunction "1_1") (pintype "passive"))
    )
    (net (code "28") (name "DCAN1_RX") (class "Default")
      (node (ref "SIP") (pin "E17") (pinfunction "UART0_RTSN_E17_E17") (pintype "bidirectional"))
      (node (ref "U1") (pin "4") (pinfunction "RXD_4") (pintype "output"))
    )
    (net (code "29") (name "DCAN1_SILENT") (class "Default")
      (node (ref "SIP") (pin "M16") (pinfunction "M16_M16") (pintype "bidirectional"))
      (node (ref "U1") (pin "8") (pinfunction "S_8") (pintype "input"))
    )
    (net (code "30") (name "DCAN1_TX") (class "Default")
      (node (ref "SIP") (pin "E18") (pinfunction "UART0_CTSN_E18_E18") (pintype "bidirectional"))
      (node (ref "U1") (pin "1") (pinfunction "TXD_1") (pintype "input"))
    )
    (net (code "31") (name "DO") (class "Default")
      (node (ref "PROT") (pin "1") (pinfunction "DO_1") (pintype "bidirectional"))
      (node (ref "Q1") (pin "4") (pinfunction "G_4") (pintype "passive"))
    )
    (net (code "32") (name "EMMC_RST") (class "Default")
      (node (ref "R94") (pin "1") (pinfunction "1_1") (pintype "passive"))
      (node (ref "SIP") (pin "R14") (pinfunction "EMMCRST_GPIO1_20_R14_R14") (pintype "bidirectional"))
      (node (ref "U13") (pin "K5") (pinfunction "RST#_K5") (pintype "bidirectional"))
    )
    (net (code "33") (name "EQEP_0A") (class "Default")
      (node (ref "E1") (pin "3") (pinfunction "3_3") (pintype "bidirectional"))
      (node (ref "SIP") (pin "B12") (pinfunction "GPIO3_18_B12_B12") (pintype "bidirectional"))
    )
    (net (code "34") (name "EQEP_0B") (class "Default")
      (node (ref "E1") (pin "4") (pinfunction "4_4") (pintype "bidirectional"))
      (node (ref "SIP") (pin "C13") (pinfunction "GPIO3_19_C13_C13") (pintype "bidirectional"))
    )
    (net (code "35") (name "EQEP_1A") (class "Default")
      (node (ref "E2") (pin "3") (pinfunction "3_3") (pintype "bidirectional"))
      (node (ref "R16") (pin "2") (pinfunction "2_2") (pintype "passive"))
      (node (ref "SIP") (pin "V2") (pinfunction "LCD_DATA12_V2_V2") (pintype "bidirectional"))
    )
    (net (code "36") (name "EQEP_1B") (class "Default")
      (node (ref "E2") (pin "4") (pinfunction "4_4") (pintype "bidirectional"))
      (node (ref "R17") (pin "2") (pinfunction "2_2") (pintype "passive"))
      (node (ref "SIP") (pin "V3") (pinfunction "LCD_DATA13_V3_V3") (pintype "bidirectional"))
    )
    (net (code "37") (name "EQEP_2A") (class "Default")
      (node (ref "E3") (pin "3") (pinfunction "3_3") (pintype "bidirectional"))
      (node (ref "SIP") (pin "T12") (pinfunction "GPIO1_12_T12_T12") (pintype "bidirectional"))
    )
    (net (code "38") (name "EQEP_2B") (class "Default")
      (node (ref "E3") (pin "4") (pinfunction "4_4") (pintype "bidirectional"))
      (node (ref "SIP") (pin "R12") (pinfunction "GPIO1_13_R12_R12") (pintype "bidirectional"))
    )
    (net (code "39") (name "GND") (class "Default")
      (node (ref "12V") (pin "OUT") (pinfunction "OUT_OUT") (pintype "bidirectional"))
      (node (ref "5VREG") (pin "4") (pinfunction "SD_4") (pintype "input"))
      (node (ref "5VREG") (pin "5") (pinfunction "GND_5") (pintype "power_in"))
      (node (ref "5VREG") (pin "6") (pinfunction "GND1_6") (pintype "input"))
      (node (ref "5VREG") (pin "7") (pinfunction "GND2_7") (pintype "passive"))
      (node (ref "5VREG") (pin "8") (pinfunction "GND3_8") (pintype "power_in"))
      (node (ref "6VREG") (pin "3") (pinfunction "GND_3") (pintype "bidirectional"))
      (node (ref "ADC") (pin "1") (pinfunction "1_1") (pintype "bidirectional"))
      (node (ref "ANT1") (pin "GND1") (pinfunction "GND1_GND1") (pintype "bidirectional"))
      (node (ref "ANT1") (pin "GND2") (pinfunction "GND2_GND2") (pintype "bidirectional"))
      (node (ref "ANT2") (pin "GND1") (pinfunction "GND1_GND1") (pintype "bidirectional"))
      (node (ref "ANT2") (pin "GND2") (pinfunction "GND2_GND2") (pintype "bidirectional"))
      (node (ref "BMP") (pin "1") (pinfunction "GND_1") (pintype "power_in"))
      (node (ref "BMP") (pin "5") (pinfunction "SDO_5") (pintype "bidirectional"))
      (node (ref "BMP") (pin "7") (pinfunction "GND_7") (pintype "power_in"))
      (node (ref "C10") (pin "1") (pinfunction "1_1") (pintype "passive"))
      (node (ref "C11") (pin "-") (pinfunction "-_-") (pintype "passive"))
      (node (ref "C12") (pin "2") (pinfunction "2_2") (pintype "passive"))
      (node (ref "C13") (pin "2") (pinfunction "2_2") (pintype "passive"))
      (node (ref "C16") (pin "2") (pinfunction "2_2") (pintype "passive"))
      (node (ref "C2") (pin "1") (pinfunction "1_1") (pintype "passive"))
      (node (ref "C20") (pin "1") (pinfunction "1_1") (pintype "passive"))
      (node (ref "C21") (pin "1") (pinfunction "1_1") (pintype "passive"))
      (node (ref "C23") (pin "1") (pinfunction "1_1") (pintype "passive"))
      (node (ref "C24") (pin "1") (pinfunction "1_1") (pintype "passive"))
      (node (ref "C25") (pin "2") (pinfunction "2_2") (pintype "passive"))
      (node (ref "C26") (pin "2") (pinfunction "2_2") (pintype "passive"))
      (node (ref "C27") (pin "2") (pinfunction "2_2") (pintype "passive"))
      (node (ref "C28") (pin "2") (pinfunction "2_2") (pintype "passive"))
      (node (ref "C3") (pin "2") (pinfunction "2_2") (pintype "passive"))
      (node (ref "C33") (pin "2") (pinfunction "2_2") (pintype "passive"))
      (node (ref "C34") (pin "1") (pinfunction "1_1") (pintype "passive"))
      (node (ref "C35") (pin "1") (pinfunction "1_1") (pintype "passive"))
      (node (ref "C36") (pin "2") (pinfunction "2_2") (pintype "passive"))
      (node (ref "C37") (pin "2") (pinfunction "2_2") (pintype "passive"))
      (node (ref "C38") (pin "2") (pinfunction "2_2") (pintype "passive"))
      (node (ref "C39") (pin "2") (pinfunction "2_2") (pintype "passive"))
      (node (ref "C4") (pin "1") (pinfunction "1_1") (pintype "passive"))
      (node (ref "C40") (pin "2") (pinfunction "2_2") (pintype "passive"))
      (node (ref "C41") (pin "2") (pinfunction "2_2") (pintype "passive"))
      (node (ref "C45") (pin "2") (pinfunction "2_2") (pintype "passive"))
      (node (ref "C46") (pin "2") (pinfunction "2_2") (pintype "passive"))
      (node (ref "C47") (pin "2") (pinfunction "2_2") (pintype "passive"))
      (node (ref "C49") (pin "1") (pinfunction "1_1") (pintype "passive"))
      (node (ref "C5") (pin "2") (pinfunction "2_2") (pintype "passive"))
      (node (ref "C50") (pin "2") (pinfunction "2_2") (pintype "passive"))
      (node (ref "C51") (pin "1") (pinfunction "1_1") (pintype "passive"))
      (node (ref "C52") (pin "2") (pinfunction "2_2") (pintype "passive"))
      (node (ref "C53") (pin "2") (pinfunction "2_2") (pintype "passive"))
      (node (ref "C54") (pin "2") (pinfunction "2_2") (pintype "passive"))
      (node (ref "C55") (pin "2") (pinfunction "2_2") (pintype "passive"))
      (node (ref "C56") (pin "2") (pinfunction "2_2") (pintype "passive"))
      (node (ref "C57") (pin "1") (pinfunction "1_1") (pintype "passive"))
      (node (ref "C59") (pin "2") (pinfunction "2_2") (pintype "passive"))
      (node (ref "C6") (pin "2") (pinfunction "2_2") (pintype "passive"))
      (node (ref "C60") (pin "1") (pinfunction "1_1") (pintype "passive"))
      (node (ref "C61") (pin "1") (pinfunction "1_1") (pintype "passive"))
      (node (ref "C62") (pin "2") (pinfunction "2_2") (pintype "passive"))
      (node (ref "C63") (pin "2") (pinfunction "2_2") (pintype "passive"))
      (node (ref "C7") (pin "2") (pinfunction "2_2") (pintype "passive"))
      (node (ref "C8") (pin "2") (pinfunction "2_2") (pintype "passive"))
      (node (ref "C9") (pin "1") (pinfunction "1_1") (pintype "passive"))
      (node (ref "CAN") (pin "1") (pinfunction "1_1") (pintype "bidirectional"))
      (node (ref "CHGIC") (pin "16") (pinfunction "PGND_16") (pintype "bidirectional"))
      (node (ref "CHGIC") (pin "8") (pinfunction "AGND_8") (pintype "bidirectional"))
      (node (ref "D1") (pin "A") (pinfunction "A_A") (pintype "passive"))
      (node (ref "D9") (pin "A") (pinfunction "A_A") (pintype "passive"))
      (node (ref "DSM2") (pin "P$2") (pinfunction "2_P$2") (pintype "bidirectional"))
      (node (ref "E1") (pin "1") (pinfunction "1_1") (pintype "bidirectional"))
      (node (ref "E2") (pin "1") (pinfunction "1_1") (pintype "bidirectional"))
      (node (ref "E3") (pin "1") (pinfunction "1_1") (pintype "bidirectional"))
      (node (ref "E4") (pin "1") (pinfunction "1_1") (pintype "bidirectional"))
      (node (ref "GND") (pin "P$1") (pinfunction "TP_P$1") (pintype "bidirectional"))
      (node (ref "GP0") (pin "1") (pinfunction "1_1") (pintype "bidirectional"))
      (node (ref "GP1") (pin "1") (pinfunction "1_1") (pintype "bidirectional"))
      (node (ref "GPS") (pin "2") (pinfunction "2_2") (pintype "bidirectional"))
      (node (ref "GPS") (pin "6") (pinfunction "6_6") (pintype "bidirectional"))
      (node (ref "H1") (pin "10") (pinfunction "PGND2_10") (pintype "bidirectional"))
      (node (ref "H1") (pin "18") (pinfunction "GND_18") (pintype "bidirectional"))
      (node (ref "H1") (pin "3") (pinfunction "PGND1_3") (pintype "bidirectional"))
      (node (ref "H1") (pin "4") (pinfunction "PGND1_4") (pintype "bidirectional"))
      (node (ref "H1") (pin "9") (pinfunction "PGND2_9") (pintype "bidirectional"))
      (node (ref "H2") (pin "10") (pinfunction "PGND2_10") (pintype "bidirectional"))
      (node (ref "H2") (pin "18") (pinfunction "GND_18") (pintype "bidirectional"))
      (node (ref "H2") (pin "3") (pinfunction "PGND1_3") (pintype "bidirectional"))
      (node (ref "H2") (pin "4") (pinfunction "PGND1_4") (pintype "bidirectional"))
      (node (ref "H2") (pin "9") (pinfunction "PGND2_9") (pintype "bidirectional"))
      (node (ref "I2C") (pin "1") (pinfunction "1_1") (pintype "bidirectional"))
      (node (ref "IMU") (pin "18") (pinfunction "GND_18") (pintype "bidirectional"))
      (node (ref "IMU") (pin "20") (pinfunction "RESV_20") (pintype "bidirectional"))
      (node (ref "IMU") (pin "9") (pinfunction "AD0/SDO_9") (pintype "bidirectional"))
      (node (ref "J2") (pin "P$13") (pinfunction "GND_P$13") (pintype "bidirectional"))
      (node (ref "J2") (pin "P$14") (pinfunction "GND_P$14") (pintype "bidirectional"))
      (node (ref "J2") (pin "P$15") (pinfunction "GND_P$15") (pintype "bidirectional"))
      (node (ref "J2") (pin "P$16") (pinfunction "GND_P$16") (pintype "bidirectional"))
      (node (ref "J2") (pin "P$17") (pinfunction "GND_P$17") (pintype "bidirectional"))
      (node (ref "J2") (pin "P$18") (pinfunction "GND_P$18") (pintype "bidirectional"))
      (node (ref "J2") (pin "P$23") (pinfunction "GND_P$23") (pintype "bidirectional"))
      (node (ref "J2") (pin "P$24") (pinfunction "GND_P$24") (pintype "bidirectional"))
      (node (ref "L4") (pin "1") (pinfunction "1_1") (pintype "passive"))
      (node (ref "MOD") (pin "1") (pinfunction "1_1") (pintype "passive"))
      (node (ref "OSC1") (pin "2") (pinfunction "GND_2") (pintype "bidirectional"))
      (node (ref "PAU") (pin "1") (pinfunction "1_1") (pintype "passive"))
      (node (ref "POW") (pin "1") (pinfunction "1_1") (pintype "passive"))
      (node (ref "PWR") (pin "1") (pinfunction "1_1") (pintype "bidirectional"))
      (node (ref "PWR") (pin "2") (pinfunction "2_2") (pintype "bidirectional"))
      (node (ref "Q1") (pin "5") (pinfunction "D_5") (pintype "passive"))
      (node (ref "Q1") (pin "6") (pinfunction "D_6") (pintype "passive"))
      (node (ref "Q1") (pin "7") (pinfunction "D_7") (pintype "passive"))
      (node (ref "Q1") (pin "8") (pinfunction "D_8") (pintype "passive"))
      (node (ref "R106") (pin "1") (pinfunction "1_1") (pintype "passive"))
      (node (ref "R107") (pin "1") (pinfunction "1_1") (pintype "passive"))
      (node (ref "R108") (pin "2") (pinfunction "2_2") (pintype "passive"))
      (node (ref "R110") (pin "2") (pinfunction "2_2") (pintype "passive"))
      (node (ref "R113") (pin "1") (pinfunction "1_1") (pintype "passive"))
      (node (ref "R115") (pin "1") (pinfunction "1_1") (pintype "passive"))
      (node (ref "R125") (pin "1") (pinfunction "1_1") (pintype "passive"))
      (node (ref "R127") (pin "1") (pinfunction "1_1") (pintype "passive"))
      (node (ref "R129") (pin "1") (pinfunction "1_1") (pintype "passive"))
      (node (ref "R131") (pin "1") (pinfunction "1_1") (pintype "passive"))
      (node (ref "R135") (pin "1") (pinfunction "1_1") (pintype "passive"))
      (node (ref "R14") (pin "2") (pinfunction "2_2") (pintype "passive"))
      (node (ref "R143") (pin "1") (pinfunction "1_1") (pintype "passive"))
      (node (ref "R150") (pin "2") (pinfunction "2_2") (pintype "passive"))
      (node (ref "R158") (pin "2") (pinfunction "2_2") (pintype "passive"))
      (node (ref "R16") (pin "1") (pinfunction "1_1") (pintype "passive"))
      (node (ref "R17") (pin "1") (pinfunction "1_1") (pintype "passive"))
      (node (ref "R21") (pin "2") (pinfunction "2_2") (pintype "passive"))
      (node (ref "R22") (pin "2") (pinfunction "2_2") (pintype "passive"))
      (node (ref "R24") (pin "2") (pinfunction "2_2") (pintype "passive"))
      (node (ref "R25") (pin "2") (pinfunction "2_2") (pintype "passive"))
      (node (ref "R29") (pin "2") (pinfunction "2_2") (pintype "passive"))
      (node (ref "R31") (pin "2") (pinfunction "2_2") (pintype "passive"))
      (node (ref "R32") (pin "2") (pinfunction "2_2") (pintype "passive"))
      (node (ref "R33") (pin "2") (pinfunction "2_2") (pintype "passive"))
      (node (ref "R46") (pin "1") (pinfunction "1_1") (pintype "passive"))
      (node (ref "R47") (pin "1") (pinfunction "1_1") (pintype "passive"))
      (node (ref "R48") (pin "1") (pinfunction "1_1") (pintype "passive"))
      (node (ref "R50") (pin "2") (pinfunction "2_2") (pintype "passive"))
      (node (ref "R51") (pin "2") (pinfunction "2_2") (pintype "passive"))
      (node (ref "R52") (pin "2") (pinfunction "2_2") (pintype "passive"))
      (node (ref "R53") (pin "2") (pinfunction "2_2") (pintype "passive"))
      (node (ref "R59") (pin "1") (pinfunction "1_1") (pintype "passive"))
      (node (ref "R6") (pin "1") (pinfunction "1_1") (pintype "passive"))
      (node (ref "R61") (pin "1") (pinfunction "1_1") (pintype "passive"))
      (node (ref "R62") (pin "1") (pinfunction "1_1") (pintype "passive"))
      (node (ref "R63") (pin "1") (pinfunction "1_1") (pintype "passive"))
      (node (ref "R64") (pin "1") (pinfunction "1_1") (pintype "passive"))
      (node (ref "R8") (pin "2") (pinfunction "2_2") (pintype "passive"))
      (node (ref "R87") (pin "2") (pinfunction "2_2") (pintype "passive"))
      (node (ref "R88") (pin "2") (pinfunction "2_2") (pintype "passive"))
      (node (ref "R89") (pin "2") (pinfunction "2_2") (pintype "passive"))
      (node (ref "R91") (pin "2") (pinfunction "2_2") (pintype "passive"))
      (node (ref "R95") (pin "1") (pinfunction "1_1") (pintype "passive"))
      (node (ref "RST") (pin "1") (pinfunction "1_1") (pintype "passive"))
      (node (ref "S1.1") (pin "1") (pinfunction "1_1") (pintype "bidirectional"))
      (node (ref "S1.2") (pin "1") (pinfunction "1_1") (pintype "bidirectional"))
      (node (ref "SD") (pin "1") (pinfunction "1_1") (pintype "passive"))
      (node (ref "SIP") (pin "A1") (pinfunction "DGND1_A1") (pintype "bidirectional"))
      (node (ref "SIP") (pin "A18") (pinfunction "DGND2_A18") (pintype "bidirectional"))
      (node (ref "SIP") (pin "E19") (pinfunction "DGND3_E19") (pintype "bidirectional"))
      (node (ref "SIP") (pin "E20") (pinfunction "DGND4_E20") (pintype "bidirectional"))
      (node (ref "SIP") (pin "F19") (pinfunction "DGND6_F19") (pintype "bidirectional"))
      (node (ref "SIP") (pin "F8") (pinfunction "DGND5_F8") (pintype "bidirectional"))
      (node (ref "SIP") (pin "G11") (pinfunction "DGND9_G11") (pintype "bidirectional"))
      (node (ref "SIP") (pin "G12") (pinfunction "DGND10_G12") (pintype "bidirectional"))
      (node (ref "SIP") (pin "G19") (pinfunction "DGND11_G19") (pintype "bidirectional"))
      (node (ref "SIP") (pin "G8") (pinfunction "DGND7_G8") (pintype "bidirectional"))
      (node (ref "SIP") (pin "G9") (pinfunction "DGND8_G9") (pintype "bidirectional"))
      (node (ref "SIP") (pin "H10") (pinfunction "DGND16_H10") (pintype "bidirectional"))
      (node (ref "SIP") (pin "H12") (pinfunction "DGND17_H12") (pintype "bidirectional"))
      (node (ref "SIP") (pin "H19") (pinfunction "DGND18_H19") (pintype "bidirectional"))
      (node (ref "SIP") (pin "H6") (pinfunction "DGND12_H6") (pintype "bidirectional"))
      (node (ref "SIP") (pin "H7") (pinfunction "DGND13_H7") (pintype "bidirectional"))
      (node (ref "SIP") (pin "H8") (pinfunction "DGND14_H8") (pintype "bidirectional"))
      (node (ref "SIP") (pin "H9") (pinfunction "DGND15_H9") (pintype "bidirectional"))
      (node (ref "SIP") (pin "J10") (pinfunction "DGND23_J10") (pintype "bidirectional"))
      (node (ref "SIP") (pin "J11") (pinfunction "DGND24_J11") (pintype "bidirectional"))
      (node (ref "SIP") (pin "J19") (pinfunction "DGND25_J19") (pintype "bidirectional"))
      (node (ref "SIP") (pin "J20") (pinfunction "DGND26_J20") (pintype "bidirectional"))
      (node (ref "SIP") (pin "J6") (pinfunction "DGND19_J6") (pintype "bidirectional"))
      (node (ref "SIP") (pin "J7") (pinfunction "DGND20_J7") (pintype "bidirectional"))
      (node (ref "SIP") (pin "J8") (pinfunction "DGND21_J8") (pintype "bidirectional"))
      (node (ref "SIP") (pin "J9") (pinfunction "DGND22_J9") (pintype "bidirectional"))
      (node (ref "SIP") (pin "K10") (pinfunction "DGND29_K10") (pintype "bidirectional"))
      (node (ref "SIP") (pin "K11") (pinfunction "DGND30_K11") (pintype "bidirectional"))
      (node (ref "SIP") (pin "K19") (pinfunction "DGND31_K19") (pintype "bidirectional"))
      (node (ref "SIP") (pin "K7") (pinfunction "DGND27_K7") (pintype "bidirectional"))
      (node (ref "SIP") (pin "K9") (pinfunction "DGND28_K9") (pintype "bidirectional"))
      (node (ref "SIP") (pin "L10") (pinfunction "DGND32_L10") (pintype "bidirectional"))
      (node (ref "SIP") (pin "L11") (pinfunction "DGND33_L11") (pintype "bidirectional"))
      (node (ref "SIP") (pin "L12") (pinfunction "DGND34_L12") (pintype "bidirectional"))
      (node (ref "SIP") (pin "L13") (pinfunction "DGND35_L13") (pintype "bidirectional"))
      (node (ref "SIP") (pin "L19") (pinfunction "DGND36_L19") (pintype "bidirectional"))
      (node (ref "SIP") (pin "M10") (pinfunction "DGND42_M10") (pintype "bidirectional"))
      (node (ref "SIP") (pin "M12") (pinfunction "DGND43_M12") (pintype "bidirectional"))
      (node (ref "SIP") (pin "M14") (pinfunction "DGND44_M14") (pintype "bidirectional"))
      (node (ref "SIP") (pin "M19") (pinfunction "DGND45_M19") (pintype "bidirectional"))
      (node (ref "SIP") (pin "M6") (pinfunction "DGND38_M6") (pintype "bidirectional"))
      (node (ref "SIP") (pin "M7") (pinfunction "DGND39_M7") (pintype "bidirectional"))
      (node (ref "SIP") (pin "M8") (pinfunction "DGND40_M8") (pintype "bidirectional"))
      (node (ref "SIP") (pin "M9") (pinfunction "DGND41_M9") (pintype "bidirectional"))
      (node (ref "SIP") (pin "N10") (pinfunction "DGND47_N10") (pintype "bidirectional"))
      (node (ref "SIP") (pin "N11") (pinfunction "DGND48_N11") (pintype "bidirectional"))
      (node (ref "SIP") (pin "N14") (pinfunction "DGND49_N14") (pintype "bidirectional"))
      (node (ref "SIP") (pin "N19") (pinfunction "DGND50_N19") (pintype "bidirectional"))
      (node (ref "SIP") (pin "N20") (pinfunction "DGND51_N20") (pintype "bidirectional"))
      (node (ref "SIP") (pin "N7") (pinfunction "DGND46_N7") (pintype "bidirectional"))
      (node (ref "SIP") (pin "P19") (pinfunction "DGND52_P19") (pintype "bidirectional"))
      (node (ref "SIP") (pin "P20") (pinfunction "DGND53_P20") (pintype "bidirectional"))
      (node (ref "SIP") (pin "R19") (pinfunction "DGND54_R19") (pintype "bidirectional"))
      (node (ref "SIP") (pin "R20") (pinfunction "DGND55_R20") (pintype "bidirectional"))
      (node (ref "SIP") (pin "T19") (pinfunction "DGND56_T19") (pintype "bidirectional"))
      (node (ref "SIP") (pin "T20") (pinfunction "DGND57_T20") (pintype "bidirectional"))
      (node (ref "SIP") (pin "U19") (pinfunction "DGND58_U19") (pintype "bidirectional"))
      (node (ref "SIP") (pin "V1") (pinfunction "DGND59_V1") (pintype "bidirectional"))
      (node (ref "SIP") (pin "V18") (pinfunction "DGND60_V18") (pintype "bidirectional"))
      (node (ref "SIP") (pin "V19") (pinfunction "DGND61_V19") (pintype "bidirectional"))
      (node (ref "SIP") (pin "W10") (pinfunction "DGND70_W10") (pintype "bidirectional"))
      (node (ref "SIP") (pin "W11") (pinfunction "DGND71_W11") (pintype "bidirectional"))
      (node (ref "SIP") (pin "W12") (pinfunction "DGND72_W12") (pintype "bidirectional"))
      (node (ref "SIP") (pin "W13") (pinfunction "DGND73_W13") (pintype "bidirectional"))
      (node (ref "SIP") (pin "W14") (pinfunction "DGND74_W14") (pintype "bidirectional"))
      (node (ref "SIP") (pin "W15") (pinfunction "DGND75_W15") (pintype "bidirectional"))
      (node (ref "SIP") (pin "W16") (pinfunction "DGND76_W16") (pintype "bidirectional"))
      (node (ref "SIP") (pin "W17") (pinfunction "DGND77_W17") (pintype "bidirectional"))
      (node (ref "SIP") (pin "W18") (pinfunction "DGND78_W18") (pintype "bidirectional"))
      (node (ref "SIP") (pin "W19") (pinfunction "DGND79_W19") (pintype "bidirectional"))
      (node (ref "SIP") (pin "W2") (pinfunction "DGND62_W2") (pintype "bidirectional"))
      (node (ref "SIP") (pin "W20") (pinfunction "DGND80_W20") (pintype "bidirectional"))
      (node (ref "SIP") (pin "W3") (pinfunction "DGND63_W3") (pintype "bidirectional"))
      (node (ref "SIP") (pin "W5") (pinfunction "DGND65_W5") (pintype "bidirectional"))
      (node (ref "SIP") (pin "W6") (pinfunction "DGND66_W6") (pintype "bidirectional"))
      (node (ref "SIP") (pin "W7") (pinfunction "DGND67_W7") (pintype "bidirectional"))
      (node (ref "SIP") (pin "W8") (pinfunction "DGND68_W8") (pintype "bidirectional"))
      (node (ref "SIP") (pin "W9") (pinfunction "DGND69_W9") (pintype "bidirectional"))
      (node (ref "SIP") (pin "Y10") (pinfunction "DGND83_Y10") (pintype "bidirectional"))
      (node (ref "SIP") (pin "Y12") (pinfunction "DGND84_Y12") (pintype "bidirectional"))
      (node (ref "SIP") (pin "Y15") (pinfunction "DGND85_Y15") (pintype "bidirectional"))
      (node (ref "SIP") (pin "Y18") (pinfunction "DGND86_Y18") (pintype "bidirectional"))
      (node (ref "SIP") (pin "Y7") (pinfunction "DGND82_Y7") (pintype "bidirectional"))
      (node (ref "TP12") (pin "TP") (pinfunction "TP_TP") (pintype "input"))
      (node (ref "U1") (pin "2") (pinfunction "GND_2") (pintype "power_in"))
      (node (ref "U10") (pin "11") (pinfunction "GND_11") (pintype "bidirectional"))
      (node (ref "U10") (pin "TP") (pinfunction "TP_TP") (pintype "bidirectional"))
      (node (ref "U13") (pin "C4") (pinfunction "VSSQ1_C4") (pintype "bidirectional"))
      (node (ref "U13") (pin "E7") (pinfunction "VSS1_E7") (pintype "bidirectional"))
      (node (ref "U13") (pin "G5") (pinfunction "VSS2_G5") (pintype "bidirectional"))
      (node (ref "U13") (pin "H10") (pinfunction "VSS3_H10") (pintype "bidirectional"))
      (node (ref "U13") (pin "K8") (pinfunction "VSS4_K8") (pintype "bidirectional"))
      (node (ref "U13") (pin "N2") (pinfunction "VSSQ2_N2") (pintype "bidirectional"))
      (node (ref "U13") (pin "N5") (pinfunction "VSSQ3_N5") (pintype "bidirectional"))
      (node (ref "U13") (pin "P4") (pinfunction "VSSQ4_P4") (pintype "bidirectional"))
      (node (ref "U13") (pin "P6") (pinfunction "VSSQ5_P6") (pintype "bidirectional"))
      (node (ref "U2") (pin "3") (pinfunction "GND_3") (pintype "power_in"))
      (node (ref "U3") (pin "4") (pinfunction "GND_4") (pintype "bidirectional"))
      (node (ref "U4") (pin "4") (pinfunction "GND_4") (pintype "bidirectional"))
      (node (ref "U5") (pin "2") (pinfunction "VSS_2") (pintype "passive"))
      (node (ref "U6") (pin "3") (pinfunction "GND_3") (pintype "power_in"))
      (node (ref "U7") (pin "1") (pinfunction "GND1_1") (pintype "bidirectional"))
      (node (ref "U7") (pin "15") (pinfunction "GND4_15") (pintype "bidirectional"))
      (node (ref "U7") (pin "16") (pinfunction "GND5_16") (pintype "bidirectional"))
      (node (ref "U7") (pin "17") (pinfunction "GND6_17") (pintype "bidirectional"))
      (node (ref "U7") (pin "19") (pinfunction "GND7_19") (pintype "bidirectional"))
      (node (ref "U7") (pin "20") (pinfunction "GND8_20") (pintype "bidirectional"))
      (node (ref "U7") (pin "23") (pinfunction "GND9_23") (pintype "bidirectional"))
      (node (ref "U7") (pin "24") (pinfunction "GND10_24") (pintype "bidirectional"))
      (node (ref "U7") (pin "28") (pinfunction "GND11_28") (pintype "bidirectional"))
      (node (ref "U7") (pin "29") (pinfunction "GND12_29") (pintype "bidirectional"))
      (node (ref "U7") (pin "30") (pinfunction "GND13_30") (pintype "bidirectional"))
      (node (ref "U7") (pin "31") (pinfunction "GND14_31") (pintype "bidirectional"))
      (node (ref "U7") (pin "33") (pinfunction "GND15_33") (pintype "bidirectional"))
      (node (ref "U7") (pin "34") (pinfunction "GND16_34") (pintype "bidirectional"))
      (node (ref "U7") (pin "35") (pinfunction "GND17_35") (pintype "bidirectional"))
      (node (ref "U7") (pin "37") (pinfunction "GND18_37") (pintype "bidirectional"))
      (node (ref "U7") (pin "39") (pinfunction "GND19_39") (pintype "bidirectional"))
      (node (ref "U7") (pin "44") (pinfunction "GND20_44") (pintype "bidirectional"))
      (node (ref "U7") (pin "45") (pinfunction "GND21_45") (pintype "bidirectional"))
      (node (ref "U7") (pin "48") (pinfunction "GND22_48") (pintype "bidirectional"))
      (node (ref "U7") (pin "49") (pinfunction "GND23_49") (pintype "bidirectional"))
      (node (ref "U7") (pin "54") (pinfunction "GND24_54") (pintype "bidirectional"))
      (node (ref "U7") (pin "55") (pinfunction "GND25_55") (pintype "bidirectional"))
      (node (ref "U7") (pin "59") (pinfunction "GND26_59") (pintype "bidirectional"))
      (node (ref "U7") (pin "61") (pinfunction "GND27_61") (pintype "bidirectional"))
      (node (ref "U7") (pin "63") (pinfunction "GND28_63") (pintype "bidirectional"))
      (node (ref "U7") (pin "64") (pinfunction "GND29_64") (pintype "bidirectional"))
      (node (ref "U7") (pin "7") (pinfunction "GND2_7") (pintype "bidirectional"))
      (node (ref "U7") (pin "9") (pinfunction "GND3_9") (pintype "bidirectional"))
      (node (ref "U7") (pin "G1") (pinfunction "G1_G1") (pintype "bidirectional"))
      (node (ref "U7") (pin "G10") (pinfunction "G10_G10") (pintype "bidirectional"))
      (node (ref "U7") (pin "G11") (pinfunction "G11_G11") (pintype "bidirectional"))
      (node (ref "U7") (pin "G12") (pinfunction "G12_G12") (pintype "bidirectional"))
      (node (ref "U7") (pin "G13") (pinfunction "G13_G13") (pintype "bidirectional"))
      (node (ref "U7") (pin "G14") (pinfunction "G14_G14") (pintype "bidirectional"))
      (node (ref "U7") (pin "G15") (pinfunction "G15_G15") (pintype "bidirectional"))
      (node (ref "U7") (pin "G16") (pinfunction "G16_G16") (pintype "bidirectional"))
      (node (ref "U7") (pin "G17") (pinfunction "G17_G17") (pintype "bidirectional"))
      (node (ref "U7") (pin "G18") (pinfunction "G18_G18") (pintype "bidirectional"))
      (node (ref "U7") (pin "G19") (pinfunction "G19_G19") (pintype "bidirectional"))
      (node (ref "U7") (pin "G2") (pinfunction "G2_G2") (pintype "bidirectional"))
      (node (ref "U7") (pin "G20") (pinfunction "G20_G20") (pintype "bidirectional"))
      (node (ref "U7") (pin "G21") (pinfunction "G21_G21") (pintype "bidirectional"))
      (node (ref "U7") (pin "G22") (pinfunction "G22_G22") (pintype "bidirectional"))
      (node (ref "U7") (pin "G23") (pinfunction "G23_G23") (pintype "bidirectional"))
      (node (ref "U7") (pin "G24") (pinfunction "G24_G24") (pintype "bidirectional"))
      (node (ref "U7") (pin "G25") (pinfunction "G25_G25") (pintype "bidirectional"))
      (node (ref "U7") (pin "G26") (pinfunction "G26_G26") (pintype "bidirectional"))
      (node (ref "U7") (pin "G27") (pinfunction "G27_G27") (pintype "bidirectional"))
      (node (ref "U7") (pin "G28") (pinfunction "G28_G28") (pintype "bidirectional"))
      (node (ref "U7") (pin "G29") (pinfunction "G29_G29") (pintype "bidirectional"))
      (node (ref "U7") (pin "G3") (pinfunction "G3_G3") (pintype "bidirectional"))
      (node (ref "U7") (pin "G30") (pinfunction "G30_G30") (pintype "bidirectional"))
      (node (ref "U7") (pin "G31") (pinfunction "G31_G31") (pintype "bidirectional"))
      (node (ref "U7") (pin "G32") (pinfunction "G32_G32") (pintype "bidirectional"))
      (node (ref "U7") (pin "G33") (pinfunction "G33_G33") (pintype "bidirectional"))
      (node (ref "U7") (pin "G34") (pinfunction "G34_G34") (pintype "bidirectional"))
      (node (ref "U7") (pin "G35") (pinfunction "G35_G35") (pintype "bidirectional"))
      (node (ref "U7") (pin "G36") (pinfunction "G36_G36") (pintype "bidirectional"))
      (node (ref "U7") (pin "G4") (pinfunction "G4_G4") (pintype "bidirectional"))
      (node (ref "U7") (pin "G5") (pinfunction "G5_G5") (pintype "bidirectional"))
      (node (ref "U7") (pin "G6") (pinfunction "G6_G6") (pintype "bidirectional"))
      (node (ref "U7") (pin "G7") (pinfunction "G7_G7") (pintype "bidirectional"))
      (node (ref "U7") (pin "G8") (pinfunction "G8_G8") (pintype "bidirectional"))
      (node (ref "U7") (pin "G9") (pinfunction "G9_G9") (pintype "bidirectional"))
      (node (ref "U8") (pin "2") (pinfunction "GND_2") (pintype "power_in"))
      (node (ref "U9") (pin "11") (pinfunction "GND_11") (pintype "bidirectional"))
      (node (ref "U9") (pin "TP") (pinfunction "TP_TP") (pintype "bidirectional"))
      (node (ref "UT0") (pin "1") (pinfunction "1_1") (pintype "bidirectional"))
      (node (ref "UT1") (pin "1") (pinfunction "1_1") (pintype "bidirectional"))
      (node (ref "UT5") (pin "1") (pinfunction "1_1") (pintype "bidirectional"))
      (node (ref "X2") (pin "6") (pinfunction "VSS_6") (pintype "bidirectional"))
      (node (ref "X2") (pin "GND") (pinfunction "GND_GND") (pintype "bidirectional"))
      (node (ref "X4") (pin "GND") (pinfunction "GND_GND") (pintype "input"))
    )
    (net (code "40") (name "GNDA_ADC") (class "Default")
      (node (ref "C42") (pin "2") (pinfunction "2_2") (pintype "passive"))
      (node (ref "C43") (pin "2") (pinfunction "2_2") (pintype "passive"))
      (node (ref "C44") (pin "2") (pinfunction "2_2") (pintype "passive"))
      (node (ref "SIP") (pin "A6") (pinfunction "VSSA_ADC_0_A6") (pintype "bidirectional"))
      (node (ref "SIP") (pin "A9") (pinfunction "VSSA_ADC_1_A9") (pintype "bidirectional"))
      (node (ref "SIP") (pin "E8") (pinfunction "VSSA_ADC_2_E8") (pintype "bidirectional"))
    )
    (net (code "41") (name "GPIO1_17") (class "Default")
      (node (ref "GP0") (pin "4") (pinfunction "4_4") (pintype "bidirectional"))
      (node (ref "SIP") (pin "V14") (pinfunction "GPIO1_17_V14_V14") (pintype "bidirectional"))
    )
    (net (code "42") (name "GPIO1_25") (class "Default")
      (node (ref "GP0") (pin "3") (pinfunction "3_3") (pintype "bidirectional"))
      (node (ref "SIP") (pin "U16") (pinfunction "HDMIINT_GPIO1_25_U16_U16") (pintype "bidirectional"))
    )
    (net (code "43") (name "GPIO3_1") (class "Default")
      (node (ref "GP1") (pin "4") (pinfunction "4_4") (pintype "bidirectional"))
      (node (ref "SIP") (pin "H17") (pinfunction "H17_H17") (pintype "bidirectional"))
    )
    (net (code "44") (name "GPIO3_2") (class "Default")
      (node (ref "GP1") (pin "3") (pinfunction "3_3") (pintype "bidirectional"))
      (node (ref "SIP") (pin "J15") (pinfunction "J15_J15") (pintype "bidirectional"))
    )
    (net (code "45") (name "GPIO3_17") (class "Default")
      (node (ref "GP0") (pin "6") (pinfunction "6_6") (pintype "bidirectional"))
      (node (ref "SIP") (pin "C12") (pinfunction "SPI1_CS0_C12_C12") (pintype "bidirectional"))
    )
    (net (code "46") (name "GPIO3_20") (class "Default")
      (node (ref "GP0") (pin "5") (pinfunction "5_5") (pintype "bidirectional"))
      (node (ref "SIP") (pin "D13") (pinfunction "GPIO3_20_D13_D13") (pintype "bidirectional"))
    )
    (net (code "47") (name "I2C0_SCL") (class "Default")
      (node (ref "R23") (pin "1") (pinfunction "1_1") (pintype "passive"))
      (node (ref "SIP") (pin "C16") (pinfunction "I2C0_SCL_C16") (pintype "bidirectional"))
      (node (ref "SIP") (pin "C20") (pinfunction "PMIC_I2C_SCL_C20") (pintype "bidirectional"))
      (node (ref "U5") (pin "1") (pinfunction "SCL_1") (pintype "input"))
    )
    (net (code "48") (name "I2C0_SDA") (class "Default")
      (node (ref "R2") (pin "1") (pinfunction "1_1") (pintype "passive"))
      (node (ref "SIP") (pin "C17") (pinfunction "I2C0_SDA_C17") (pintype "bidirectional"))
      (node (ref "SIP") (pin "C19") (pinfunction "PMIC_I2C_SDA_C19") (pintype "bidirectional"))
      (node (ref "U5") (pin "3") (pinfunction "SDA_3") (pintype "bidirectional"))
    )
    (net (code "49") (name "I2C1_SCL") (class "Default")
      (node (ref "I2C") (pin "3") (pinfunction "3_3") (pintype "bidirectional"))
      (node (ref "R12") (pin "1") (pinfunction "1_1") (pintype "passive"))
      (node (ref "SIP") (pin "A16") (pinfunction "I2C1_SCL_A16_A16") (pintype "bidirectional"))
    )
    (net (code "50") (name "I2C1_SDA") (class "Default")
      (node (ref "I2C") (pin "4") (pinfunction "4_4") (pintype "bidirectional"))
      (node (ref "R13") (pin "2") (pinfunction "2_2") (pintype "passive"))
      (node (ref "SIP") (pin "B16") (pinfunction "I2C1_SDA_B16_B16") (pintype "bidirectional"))
    )
    (net (code "51") (name "I2C2_SCL") (class "Default")
      (node (ref "BMP") (pin "4") (pinfunction "SCK_4") (pintype "input"))
      (node (ref "IMU") (pin "23") (pinfunction "SCL/SCLK_23") (pintype "bidirectional"))
      (node (ref "R11") (pin "1") (pinfunction "1_1") (pintype "passive"))
      (node (ref "SIP") (pin "D17") (pinfunction "I2C2_SCL_D17_D17") (pintype "bidirectional"))
    )
    (net (code "52") (name "I2C2_SDA") (class "Default")
      (node (ref "BMP") (pin "3") (pinfunction "SDI_3") (pintype "bidirectional"))
      (node (ref "IMU") (pin "24") (pinfunction "SDA/SDI_24") (pintype "bidirectional"))
      (node (ref "R10") (pin "2") (pinfunction "2_2") (pintype "passive"))
      (node (ref "SIP") (pin "D18") (pinfunction "I2C2_SDA_D18_D18") (pintype "bidirectional"))
    )
    (net (code "53") (name "IMU_INT") (class "Default")
      (node (ref "IMU") (pin "12") (pinfunction "INT_12") (pintype "bidirectional"))
      (node (ref "SIP") (pin "A14") (pinfunction "GPIO3_21_A14_A14") (pintype "bidirectional"))
    )
    (net (code "54") (name "LDO_PGOOD") (class "Default")
      (node (ref "SIP") (pin "B20") (pinfunction "PMIC_OUT_LDO_PGOOD_B20") (pintype "output"))
      (node (ref "SIP") (pin "B5") (pinfunction "RTC_PWRONRSTN_B5") (pintype "bidirectional"))
    )
    (net (code "55") (name "LED_GRN") (class "Default")
      (node (ref "G") (pin "A") (pinfunction "A_A") (pintype "passive"))
      (node (ref "GP1") (pin "6") (pinfunction "6_6") (pintype "bidirectional"))
      (node (ref "SIP") (pin "T7") (pinfunction "TIMER7_T7_T7") (pintype "bidirectional"))
    )
    (net (code "56") (name "LED_RED") (class "Default")
      (node (ref "GP1") (pin "5") (pinfunction "5_5") (pintype "bidirectional"))
      (node (ref "R") (pin "A") (pinfunction "A_A") (pintype "passive"))
      (node (ref "SIP") (pin "R7") (pinfunction "TIMER4_R7_R7") (pintype "bidirectional"))
    )
    (net (code "57") (name "MCASP0_ACLKR") (class "Default")
      (node (ref "SIP") (pin "U18") (pinfunction "GPIO1_28_U18_U18") (pintype "bidirectional"))
      (node (ref "U10") (pin "20") (pinfunction "B1_20") (pintype "bidirectional"))
    )
    (net (code "58") (name "MCASP0_AXR0") (class "Default")
      (node (ref "SIP") (pin "T16") (pinfunction "USB1OC_GPIO1_26_T16_T16") (pintype "bidirectional"))
      (node (ref "U10") (pin "17") (pinfunction "B3_17") (pintype "bidirectional"))
    )
    (net (code "59") (name "MCASP0_AXR1") (class "Default")
      (node (ref "SIP") (pin "V17") (pinfunction "HDMIDIS_GPIO1_27_V17_V17") (pintype "bidirectional"))
      (node (ref "U10") (pin "16") (pinfunction "B4_16") (pintype "bidirectional"))
    )
    (net (code "60") (name "MCASP0_FSR") (class "Default")
      (node (ref "SIP") (pin "V12") (pinfunction "GPIO2_1_V12_V12") (pintype "bidirectional"))
      (node (ref "U10") (pin "18") (pinfunction "B2_18") (pintype "bidirectional"))
    )
    (net (code "61") (name "MDIR_1A") (class "Default")
      (node (ref "H1") (pin "21") (pinfunction "AIN1_21") (pintype "bidirectional"))
      (node (ref "SIP") (pin "T13") (pinfunction "GPIO2_0_T13_T13") (pintype "bidirectional"))
    )
    (net (code "62") (name "MDIR_1B") (class "Default")
      (node (ref "H1") (pin "22") (pinfunction "AIN2_22") (pintype "bidirectional"))
      (node (ref "SIP") (pin "U17") (pinfunction "UART4_TXD_U17_U17") (pintype "bidirectional"))
    )
    (net (code "63") (name "MDIR_2A") (class "Default")
      (node (ref "H1") (pin "17") (pinfunction "BIN1_17") (pintype "bidirectional"))
      (node (ref "SIP") (pin "R13") (pinfunction "GPIO1_16_R13_R13") (pintype "bidirectional"))
    )
    (net (code "64") (name "MDIR_2B") (class "Default")
      (node (ref "H1") (pin "16") (pinfunction "BIN2_16") (pintype "bidirectional"))
      (node (ref "R140") (pin "1") (pinfunction "1_1") (pintype "passive"))
      (node (ref "SIP") (pin "V4") (pinfunction "LCD_DATA14_V4_V4") (pintype "bidirectional"))
    )
    (net (code "65") (name "MDIR_3A") (class "Default")
      (node (ref "H2") (pin "21") (pinfunction "AIN1_21") (pintype "bidirectional"))
      (node (ref "R118") (pin "1") (pinfunction "1_1") (pintype "passive"))
      (node (ref "SIP") (pin "R4") (pinfunction "LCD_DATA3_R4_R4") (pintype "bidirectional"))
    )
    (net (code "66") (name "MDIR_3B") (class "Default")
      (node (ref "H2") (pin "22") (pinfunction "AIN2_22") (pintype "bidirectional"))
      (node (ref "R116") (pin "1") (pinfunction "1_1") (pintype "passive"))
      (node (ref "R77") (pin "1") (pinfunction "1_1") (pintype "passive"))
      (node (ref "SIP") (pin "R3") (pinfunction "LCD_DATA2_R3_R3") (pintype "bidirectional"))
    )
    (net (code "67") (name "MDIR_4A") (class "Default")
      (node (ref "H2") (pin "17") (pinfunction "BIN1_17") (pintype "bidirectional"))
      (node (ref "R113") (pin "2") (pinfunction "2_2") (pintype "passive"))
      (node (ref "SIP") (pin "R1") (pinfunction "LCD_DATA0_R1_R1") (pintype "bidirectional"))
    )
    (net (code "68") (name "MDIR_4B") (class "Default")
      (node (ref "H2") (pin "16") (pinfunction "BIN2_16") (pintype "bidirectional"))
      (node (ref "R115") (pin "2") (pinfunction "2_2") (pintype "passive"))
      (node (ref "SIP") (pin "R2") (pinfunction "LCD_DATA1_R2_R2") (pintype "bidirectional"))
    )
    (net (code "69") (name "MMC1_CLK") (class "Default")
      (node (ref "R15") (pin "2") (pinfunction "2_2") (pintype "passive"))
      (node (ref "R66") (pin "1") (pinfunction "1_1") (pintype "passive"))
      (node (ref "U13") (pin "M6") (pinfunction "CLK_M6") (pintype "bidirectional"))
    )
    (net (code "70") (name "MMC1_CMD") (class "Default")
      (node (ref "R67") (pin "1") (pinfunction "1_1") (pintype "passive"))
      (node (ref "SIP") (pin "V9") (pinfunction "MMC1_CMD_V9_V9") (pintype "bidirectional"))
      (node (ref "U13") (pin "M5") (pinfunction "CMD_M5") (pintype "bidirectional"))
    )
    (net (code "71") (name "MMC1_DAT0") (class "Default")
      (node (ref "R68") (pin "1") (pinfunction "1_1") (pintype "passive"))
      (node (ref "SIP") (pin "U7") (pinfunction "MMC1_DAT0_U7_U7") (pintype "bidirectional"))
      (node (ref "U13") (pin "A3") (pinfunction "DAT0_A3") (pintype "bidirectional"))
    )
    (net (code "72") (name "MMC1_DAT1") (class "Default")
      (node (ref "R69") (pin "1") (pinfunction "1_1") (pintype "passive"))
      (node (ref "SIP") (pin "V7") (pinfunction "MMC1_DAT1_V7_V7") (pintype "bidirectional"))
      (node (ref "U13") (pin "A4") (pinfunction "DAT1_A4") (pintype "bidirectional"))
    )
    (net (code "73") (name "MMC1_DAT2") (class "Default")
      (node (ref "R70") (pin "1") (pinfunction "1_1") (pintype "passive"))
      (node (ref "SIP") (pin "R8") (pinfunction "MMC1_DAT2_R8_R8") (pintype "bidirectional"))
      (node (ref "U13") (pin "A5") (pinfunction "DAT2_A5") (pintype "bidirectional"))
    )
    (net (code "74") (name "MMC1_DAT3") (class "Default")
      (node (ref "R71") (pin "1") (pinfunction "1_1") (pintype "passive"))
      (node (ref "SIP") (pin "T8") (pinfunction "MMC1_DAT3_T8_T8") (pintype "bidirectional"))
      (node (ref "U13") (pin "B2") (pinfunction "DAT3_B2") (pintype "bidirectional"))
    )
    (net (code "75") (name "MMC1_DAT4") (class "Default")
      (node (ref "R72") (pin "1") (pinfunction "1_1") (pintype "passive"))
      (node (ref "SIP") (pin "U8") (pinfunction "MMC1_DAT4_U8_U8") (pintype "bidirectional"))
      (node (ref "U13") (pin "B3") (pinfunction "DAT4_B3") (pintype "bidirectional"))
    )
    (net (code "76") (name "MMC1_DAT5") (class "Default")
      (node (ref "R73") (pin "1") (pinfunction "1_1") (pintype "passive"))
      (node (ref "SIP") (pin "V8") (pinfunction "MMC1_DAT5_V8_V8") (pintype "bidirectional"))
      (node (ref "U13") (pin "B4") (pinfunction "DAT5_B4") (pintype "bidirectional"))
    )
    (net (code "77") (name "MMC1_DAT6") (class "Default")
      (node (ref "R74") (pin "1") (pinfunction "1_1") (pintype "passive"))
      (node (ref "SIP") (pin "R9") (pinfunction "MMC1_DAT6_R9_R9") (pintype "bidirectional"))
      (node (ref "U13") (pin "B5") (pinfunction "DAT6_B5") (pintype "bidirectional"))
    )
    (net (code "78") (name "MMC1_DAT7") (class "Default")
      (node (ref "R75") (pin "1") (pinfunction "1_1") (pintype "passive"))
      (node (ref "SIP") (pin "T9") (pinfunction "MMC1_DAT7_T9_T9") (pintype "bidirectional"))
      (node (ref "U13") (pin "B6") (pinfunction "DAT7_B6") (pintype "bidirectional"))
    )
    (net (code "79") (name "MMC2_CLK") (class "Default")
      (node (ref "R76") (pin "1") (pinfunction "1_1") (pintype "passive"))
      (node (ref "U9") (pin "13") (pinfunction "B7_13") (pintype "bidirectional"))
    )
    (net (code "80") (name "MMC2_CMD") (class "Default")
      (node (ref "SIP") (pin "J16") (pinfunction "J16_J16") (pintype "bidirectional"))
      (node (ref "U9") (pin "12") (pinfunction "B8_12") (pintype "bidirectional"))
    )
    (net (code "81") (name "MMC2_DAT0") (class "Default")
      (node (ref "SIP") (pin "J17") (pinfunction "J17_J17") (pintype "bidirectional"))
      (node (ref "U9") (pin "14") (pinfunction "B6_14") (pintype "bidirectional"))
    )
    (net (code "82") (name "MMC2_DAT1") (class "Default")
      (node (ref "SIP") (pin "J18") (pinfunction "J18_J18") (pintype "bidirectional"))
      (node (ref "U9") (pin "15") (pinfunction "B5_15") (pintype "bidirectional"))
    )
    (net (code "83") (name "MMC2_DAT2") (class "Default")
      (node (ref "SIP") (pin "K15") (pinfunction "K15_K15") (pintype "bidirectional"))
      (node (ref "U9") (pin "16") (pinfunction "B4_16") (pintype "bidirectional"))
    )
    (net (code "84") (name "MMC2_DAT3") (class "Default")
      (node (ref "SIP") (pin "H16") (pinfunction "H16_H16") (pintype "bidirectional"))
      (node (ref "U9") (pin "17") (pinfunction "B3_17") (pintype "bidirectional"))
    )
    (net (code "85") (name "MODE_BTN") (class "Default")
      (node (ref "MOD") (pin "2") (pinfunction "2_2") (pintype "passive"))
      (node (ref "SIP") (pin "U6") (pinfunction "TIMER6_U6_U6") (pintype "bidirectional"))
    )
    (net (code "86") (name "MOT_STBY") (class "Default")
      (node (ref "H1") (pin "19") (pinfunction "STBY_19") (pintype "bidirectional"))
      (node (ref "H2") (pin "19") (pinfunction "STBY_19") (pintype "bidirectional"))
      (node (ref "SIP") (pin "D14") (pinfunction "GPIO0_20_D14_D14") (pintype "bidirectional"))
    )
    (net (code "87") (name "Net-(0-PadC)") (class "Default")
      (node (ref "0") (pin "C") (pinfunction "C_C") (pintype "passive"))
      (node (ref "R61") (pin "2") (pinfunction "2_2") (pintype "passive"))
    )
    (net (code "88") (name "Net-(1-PadC)") (class "Default")
      (node (ref "1") (pin "C") (pinfunction "C_C") (pintype "passive"))
      (node (ref "R62") (pin "2") (pinfunction "2_2") (pintype "passive"))
    )
    (net (code "89") (name "Net-(2-PadC)") (class "Default")
      (node (ref "2") (pin "C") (pinfunction "C_C") (pintype "passive"))
      (node (ref "R63") (pin "2") (pinfunction "2_2") (pintype "passive"))
    )
    (net (code "90") (name "Net-(3-PadC)") (class "Default")
      (node (ref "3") (pin "C") (pinfunction "C_C") (pintype "passive"))
      (node (ref "R64") (pin "2") (pinfunction "2_2") (pintype "passive"))
    )
    (net (code "91") (name "Net-(5VREG-OUT)") (class "Default")
      (node (ref "5VREG") (pin "2") (pinfunction "OUT_2") (pintype "power_in"))
      (node (ref "D1") (pin "C") (pinfunction "C_C") (pintype "passive"))
      (node (ref "L1") (pin "1") (pinfunction "1_1") (pintype "passive"))
    )
    (net (code "92") (name "Net-(5VREG-VIN)") (class "Default")
      (node (ref "5VREG") (pin "1") (pinfunction "VIN_1") (pintype "input"))
      (node (ref "C3") (pin "1") (pinfunction "1_1") (pintype "passive"))
      (node (ref "D2") (pin "C") (pinfunction "C_C") (pintype "passive"))
      (node (ref "D3") (pin "C") (pinfunction "C_C") (pintype "passive"))
    )
    (net (code "93") (name "Net-(6VREG-BS)") (class "Default")
      (node (ref "6VREG") (pin "2") (pinfunction "BS_2") (pintype "bidirectional"))
      (node (ref "C22") (pin "1") (pinfunction "1_1") (pintype "passive"))
    )
    (net (code "94") (name "Net-(6VREG-COMP)") (class "Default")
      (node (ref "6VREG") (pin "5") (pinfunction "COMP_5") (pintype "bidirectional"))
      (node (ref "R45") (pin "2") (pinfunction "2_2") (pintype "passive"))
    )
    (net (code "95") (name "Net-(6VREG-FB)") (class "Default")
      (node (ref "6VREG") (pin "6") (pinfunction "FB_6") (pintype "bidirectional"))
      (node (ref "R48") (pin "2") (pinfunction "2_2") (pintype "passive"))
      (node (ref "R49") (pin "1") (pinfunction "1_1") (pintype "passive"))
    )
    (net (code "96") (name "Net-(6VREG-FSW)") (class "Default")
      (node (ref "6VREG") (pin "4") (pinfunction "FSW_4") (pintype "bidirectional"))
      (node (ref "R47") (pin "2") (pinfunction "2_2") (pintype "passive"))
    )
    (net (code "97") (name "Net-(6VREG-LX)") (class "Default")
      (node (ref "6VREG") (pin "1") (pinfunction "LX_1") (pintype "bidirectional"))
      (node (ref "C22") (pin "2") (pinfunction "2_2") (pintype "passive"))
      (node (ref "D9") (pin "C") (pinfunction "C_C") (pintype "passive"))
      (node (ref "L3") (pin "1") (pinfunction "1_1") (pintype "passive"))
    )
    (net (code "98") (name "Net-(6VREG-SS)") (class "Default")
      (node (ref "6VREG") (pin "7") (pinfunction "SS_7") (pintype "bidirectional"))
      (node (ref "C21") (pin "2") (pinfunction "2_2") (pintype "passive"))
    )
    (net (code "99") (name "Net-(ANT1-PadSIG)") (class "Default")
      (node (ref "ANT1") (pin "SIG") (pinfunction "SIG_SIG") (pintype "bidirectional"))
      (node (ref "C48") (pin "1") (pinfunction "1_1") (pintype "passive"))
    )
    (net (code "100") (name "Net-(ANT2-PadSIG)") (class "Default")
      (node (ref "ANT2") (pin "SIG") (pinfunction "SIG_SIG") (pintype "bidirectional"))
      (node (ref "C58") (pin "1") (pinfunction "1_1") (pintype "passive"))
    )
    (net (code "101") (name "Net-(B0-PadC)") (class "Default")
      (node (ref "B0") (pin "C") (pinfunction "C_C") (pintype "passive"))
      (node (ref "R31") (pin "1") (pinfunction "1_1") (pintype "passive"))
    )
    (net (code "102") (name "Net-(B1-PadC)") (class "Default")
      (node (ref "B1") (pin "C") (pinfunction "C_C") (pintype "passive"))
      (node (ref "R29") (pin "1") (pinfunction "1_1") (pintype "passive"))
    )
    (net (code "103") (name "Net-(B2-PadC)") (class "Default")
      (node (ref "B2") (pin "C") (pinfunction "C_C") (pintype "passive"))
      (node (ref "R33") (pin "1") (pinfunction "1_1") (pintype "passive"))
    )
    (net (code "104") (name "Net-(B3-PadC)") (class "Default")
      (node (ref "B3") (pin "C") (pinfunction "C_C") (pintype "passive"))
      (node (ref "R32") (pin "1") (pinfunction "1_1") (pintype "passive"))
    )
    (net (code "105") (name "Net-(BAL-CD)") (class "Default")
      (node (ref "BAL") (pin "4") (pinfunction "CD_4") (pintype "bidirectional"))
      (node (ref "C19") (pin "1") (pinfunction "1_1") (pintype "passive"))
    )
    (net (code "106") (name "Net-(BAL-OUT)") (class "Default")
      (node (ref "BAL") (pin "8") (pinfunction "OUT_8") (pintype "bidirectional"))
      (node (ref "R7") (pin "1") (pinfunction "1_1") (pintype "passive"))
    )
    (net (code "107") (name "Net-(BAL-VC1)") (class "Default")
      (node (ref "BAL") (pin "2") (pinfunction "VC1_2") (pintype "bidirectional"))
      (node (ref "C17") (pin "1") (pinfunction "1_1") (pintype "passive"))
      (node (ref "C18") (pin "2") (pinfunction "2_2") (pintype "passive"))
      (node (ref "R30") (pin "2") (pinfunction "2_2") (pintype "passive"))
    )
    (net (code "108") (name "Net-(BAL-VC1_CB)") (class "Default")
      (node (ref "BAL") (pin "3") (pinfunction "VC1_CB_3") (pintype "bidirectional"))
      (node (ref "R27") (pin "2") (pinfunction "2_2") (pintype "passive"))
    )
    (net (code "109") (name "Net-(BAL-VC2)") (class "Default")
      (node (ref "BAL") (pin "1") (pinfunction "VC2_1") (pintype "bidirectional"))
      (node (ref "C17") (pin "2") (pinfunction "2_2") (pintype "passive"))
      (node (ref "R28") (pin "2") (pinfunction "2_2") (pintype "passive"))
    )
    (net (code "110") (name "Net-(BAL-VDD)") (class "Default")
      (node (ref "BAL") (pin "7") (pinfunction "VDD_7") (pintype "bidirectional"))
      (node (ref "C1") (pin "1") (pinfunction "1_1") (pintype "passive"))
      (node (ref "R34") (pin "2") (pinfunction "2_2") (pintype "passive"))
    )
    (net (code "111") (name "Net-(C23-Pad2)") (class "Default")
      (node (ref "C23") (pin "2") (pinfunction "2_2") (pintype "passive"))
      (node (ref "J2") (pin "P$10") (pinfunction "PWR_P$10") (pintype "bidirectional"))
      (node (ref "J2") (pin "P$11") (pinfunction "PWR_P$11") (pintype "bidirectional"))
      (node (ref "J2") (pin "P$12") (pinfunction "PWR_P$12") (pintype "bidirectional"))
      (node (ref "J2") (pin "P$21") (pinfunction "PWR_P$21") (pintype "bidirectional"))
      (node (ref "J2") (pin "P$22") (pinfunction "PWR_P$22") (pintype "bidirectional"))
      (node (ref "J2") (pin "P$7") (pinfunction "PWR_P$7") (pintype "bidirectional"))
      (node (ref "J2") (pin "P$8") (pinfunction "PWR_P$8") (pintype "bidirectional"))
      (node (ref "J2") (pin "P$9") (pinfunction "PWR_P$9") (pintype "bidirectional"))
      (node (ref "L3") (pin "2") (pinfunction "2_2") (pintype "passive"))
      (node (ref "R49") (pin "2") (pinfunction "2_2") (pintype "passive"))
    )
    (net (code "112") (name "Net-(C24-Pad2)") (class "Default")
      (node (ref "C24") (pin "2") (pinfunction "2_2") (pintype "passive"))
      (node (ref "R45") (pin "1") (pinfunction "1_1") (pintype "passive"))
    )
    (net (code "113") (name "Net-(CHG-PadC)") (class "Default")
      (node (ref "CHG") (pin "C") (pinfunction "C_C") (pintype "passive"))
      (node (ref "R3") (pin "2") (pinfunction "2_2") (pintype "passive"))
    )
    (net (code "114") (name "Net-(CHGIC-BST)") (class "Default")
      (node (ref "C14") (pin "1") (pinfunction "1_1") (pintype "passive"))
      (node (ref "CHGIC") (pin "15") (pinfunction "BST_15") (pintype "bidirectional"))
    )
    (net (code "115") (name "Net-(CHGIC-CHGOK)") (class "Default")
      (node (ref "CHGIC") (pin "11") (pinfunction "CHGOK_11") (pintype "bidirectional"))
      (node (ref "R3") (pin "1") (pinfunction "1_1") (pintype "passive"))
    )
    (net (code "116") (name "Net-(CHGIC-CSP)") (class "Default")
      (node (ref "CHGIC") (pin "10") (pinfunction "CSP_10") (pintype "bidirectional"))
      (node (ref "L2") (pin "2") (pinfunction "2_2") (pintype "passive"))
      (node (ref "R4") (pin "2") (pinfunction "2_2") (pintype "passive"))
    )
    (net (code "117") (name "Net-(CHGIC-NTC)") (class "Default")
      (node (ref "CHGIC") (pin "13") (pinfunction "NTC_13") (pintype "bidirectional"))
      (node (ref "R5") (pin "1") (pinfunction "1_1") (pintype "passive"))
      (node (ref "R6") (pin "2") (pinfunction "2_2") (pintype "passive"))
    )
    (net (code "118") (name "Net-(CHGIC-SW)") (class "Default")
      (node (ref "C14") (pin "2") (pinfunction "2_2") (pintype "passive"))
      (node (ref "CHGIC") (pin "1") (pinfunction "SW_1") (pintype "bidirectional"))
      (node (ref "L2") (pin "1") (pinfunction "1_1") (pintype "passive"))
    )
    (net (code "119") (name "Net-(CHGIC-TMR)") (class "Default")
      (node (ref "C10") (pin "2") (pinfunction "2_2") (pintype "passive"))
      (node (ref "CHGIC") (pin "14") (pinfunction "TMR_14") (pintype "bidirectional"))
    )
    (net (code "120") (name "Net-(G-PadC)") (class "Default")
      (node (ref "G") (pin "C") (pinfunction "C_C") (pintype "passive"))
      (node (ref "R22") (pin "1") (pinfunction "1_1") (pintype "passive"))
    )
    (net (code "121") (name "Net-(IMU-REGOUT)") (class "Default")
      (node (ref "C6") (pin "1") (pinfunction "1_1") (pintype "passive"))
      (node (ref "IMU") (pin "10") (pinfunction "REGOUT_10") (pintype "bidirectional"))
    )
    (net (code "122") (name "Net-(J2-1)") (class "Default")
      (node (ref "J2") (pin "P$1") (pinfunction "1_P$1") (pintype "bidirectional"))
      (node (ref "R36") (pin "2") (pinfunction "2_2") (pintype "passive"))
    )
    (net (code "123") (name "Net-(J2-2)") (class "Default")
      (node (ref "J2") (pin "P$2") (pinfunction "2_P$2") (pintype "bidirectional"))
      (node (ref "R37") (pin "2") (pinfunction "2_2") (pintype "passive"))
    )
    (net (code "124") (name "Net-(J2-3)") (class "Default")
      (node (ref "J2") (pin "P$3") (pinfunction "3_P$3") (pintype "bidirectional"))
      (node (ref "R38") (pin "2") (pinfunction "2_2") (pintype "passive"))
    )
    (net (code "125") (name "Net-(J2-4)") (class "Default")
      (node (ref "J2") (pin "P$4") (pinfunction "4_P$4") (pintype "bidirectional"))
      (node (ref "R39") (pin "2") (pinfunction "2_2") (pintype "passive"))
    )
    (net (code "126") (name "Net-(J2-5)") (class "Default")
      (node (ref "J2") (pin "P$5") (pinfunction "5_P$5") (pintype "bidirectional"))
      (node (ref "R40") (pin "2") (pinfunction "2_2") (pintype "passive"))
    )
    (net (code "127") (name "Net-(J2-6)") (class "Default")
      (node (ref "J2") (pin "P$6") (pinfunction "6_P$6") (pintype "bidirectional"))
      (node (ref "R41") (pin "2") (pinfunction "2_2") (pintype "passive"))
    )
    (net (code "128") (name "Net-(J2-7)") (class "Default")
      (node (ref "J2") (pin "P$19") (pinfunction "7_P$19") (pintype "bidirectional"))
      (node (ref "R42") (pin "2") (pinfunction "2_2") (pintype "passive"))
    )
    (net (code "129") (name "Net-(J2-8)") (class "Default")
      (node (ref "J2") (pin "P$20") (pinfunction "8_P$20") (pintype "bidirectional"))
      (node (ref "R43") (pin "2") (pinfunction "2_2") (pintype "passive"))
    )
    (net (code "130") (name "Net-(M1-1)") (class "Default")
      (node (ref "H1") (pin "5") (pinfunction "A02_5") (pintype "bidirectional"))
      (node (ref "H1") (pin "6") (pinfunction "A02_6") (pintype "bidirectional"))
      (node (ref "M1") (pin "P$1") (pinfunction "1_P$1") (pintype "bidirectional"))
    )
    (net (code "131") (name "Net-(M1-2)") (class "Default")
      (node (ref "H1") (pin "1") (pinfunction "A01_1") (pintype "bidirectional"))
      (node (ref "H1") (pin "2") (pinfunction "A01_2") (pintype "bidirectional"))
      (node (ref "M1") (pin "P$2") (pinfunction "2_P$2") (pintype "bidirectional"))
    )
    (net (code "132") (name "Net-(M2-1)") (class "Default")
      (node (ref "H1") (pin "11") (pinfunction "B01_11") (pintype "bidirectional"))
      (node (ref "H1") (pin "12") (pinfunction "B01_12") (pintype "bidirectional"))
      (node (ref "M2") (pin "P$1") (pinfunction "1_P$1") (pintype "bidirectional"))
    )
    (net (code "133") (name "Net-(M2-2)") (class "Default")
      (node (ref "H1") (pin "7") (pinfunction "B02_7") (pintype "bidirectional"))
      (node (ref "H1") (pin "8") (pinfunction "B02_8") (pintype "bidirectional"))
      (node (ref "M2") (pin "P$2") (pinfunction "2_P$2") (pintype "bidirectional"))
    )
    (net (code "134") (name "Net-(M3-1)") (class "Default")
      (node (ref "H2") (pin "1") (pinfunction "A01_1") (pintype "bidirectional"))
      (node (ref "H2") (pin "2") (pinfunction "A01_2") (pintype "bidirectional"))
      (node (ref "M3") (pin "P$1") (pinfunction "1_P$1") (pintype "bidirectional"))
    )
    (net (code "135") (name "Net-(M3-2)") (class "Default")
      (node (ref "H2") (pin "5") (pinfunction "A02_5") (pintype "bidirectional"))
      (node (ref "H2") (pin "6") (pinfunction "A02_6") (pintype "bidirectional"))
      (node (ref "M3") (pin "P$2") (pinfunction "2_P$2") (pintype "bidirectional"))
    )
    (net (code "136") (name "Net-(M4-1)") (class "Default")
      (node (ref "H2") (pin "7") (pinfunction "B02_7") (pintype "bidirectional"))
      (node (ref "H2") (pin "8") (pinfunction "B02_8") (pintype "bidirectional"))
      (node (ref "M4") (pin "P$1") (pinfunction "1_P$1") (pintype "bidirectional"))
    )
    (net (code "137") (name "Net-(M4-2)") (class "Default")
      (node (ref "H2") (pin "11") (pinfunction "B01_11") (pintype "bidirectional"))
      (node (ref "H2") (pin "12") (pinfunction "B01_12") (pintype "bidirectional"))
      (node (ref "M4") (pin "P$2") (pinfunction "2_P$2") (pintype "bidirectional"))
    )
    (net (code "138") (name "Net-(OSC1-EN)") (class "Default")
      (node (ref "OSC1") (pin "1") (pinfunction "EN_1") (pintype "bidirectional"))
      (node (ref "R90") (pin "1") (pinfunction "1_1") (pintype "passive"))
    )
    (net (code "139") (name "Net-(PROT-VDD)") (class "Default")
      (node (ref "C15") (pin "2") (pinfunction "2_2") (pintype "passive"))
      (node (ref "PROT") (pin "5") (pinfunction "VDD_5") (pintype "bidirectional"))
      (node (ref "R44") (pin "2") (pinfunction "2_2") (pintype "passive"))
    )
    (net (code "140") (name "Net-(R-PadC)") (class "Default")
      (node (ref "R") (pin "C") (pinfunction "C_C") (pintype "passive"))
      (node (ref "R21") (pin "1") (pinfunction "1_1") (pintype "passive"))
    )
    (net (code "141") (name "Net-(R76-Pad2)") (class "Default")
      (node (ref "R76") (pin "2") (pinfunction "2_2") (pintype "passive"))
      (node (ref "SIP") (pin "L15") (pinfunction "L15_L15") (pintype "bidirectional"))
    )
    (net (code "142") (name "Net-(R91-Pad1)") (class "Default")
      (node (ref "R91") (pin "1") (pinfunction "1_1") (pintype "passive"))
      (node (ref "WIFI") (pin "C") (pinfunction "C_C") (pintype "passive"))
    )
    (net (code "143") (name "Net-(SIPA-PMIC_IN_PWR_EN)") (class "Default")
      (node (ref "SIP") (pin "C6") (pinfunction "PMIC_POWER_EN_C6") (pintype "output"))
      (node (ref "SIP") (pin "D19") (pinfunction "PMIC_IN_PWR_EN_D19") (pintype "input"))
      (node (ref "TP5") (pin "TP") (pinfunction "TP_TP") (pintype "input"))
    )
    (net (code "144") (name "Net-(SIPB-JTAG_EMU0)") (class "Default")
      (node (ref "EMU1") (pin "TP") (pinfunction "TP_TP") (pintype "input"))
      (node (ref "SIP") (pin "C14") (pinfunction "JTAG_EMU0_C14") (pintype "bidirectional"))
    )
    (net (code "145") (name "Net-(SIPB-JTAG_EMU1)") (class "Default")
      (node (ref "EMU0") (pin "TP") (pinfunction "TP_TP") (pintype "input"))
      (node (ref "SIP") (pin "B14") (pinfunction "JTAG_EMU1_B14") (pintype "bidirectional"))
    )
    (net (code "146") (name "Net-(SIPB-JTAG_TCK)") (class "Default")
      (node (ref "SIP") (pin "A12") (pinfunction "JTAG_TCK_A12") (pintype "bidirectional"))
      (node (ref "TCK") (pin "TP") (pinfunction "TP_TP") (pintype "input"))
    )
    (net (code "147") (name "Net-(SIPB-JTAG_TDI)") (class "Default")
      (node (ref "SIP") (pin "B11") (pinfunction "JTAG_TDI_B11") (pintype "bidirectional"))
      (node (ref "TDI") (pin "TP") (pinfunction "TP_TP") (pintype "input"))
    )
    (net (code "148") (name "Net-(SIPB-JTAG_TDO)") (class "Default")
      (node (ref "SIP") (pin "A11") (pinfunction "JTAG_TDO_A11") (pintype "bidirectional"))
      (node (ref "TDO") (pin "TP") (pinfunction "TP_TP") (pintype "input"))
    )
    (net (code "149") (name "Net-(SIPB-JTAG_TMS)") (class "Default")
      (node (ref "SIP") (pin "C11") (pinfunction "JTAG_TMS_C11") (pintype "bidirectional"))
      (node (ref "TMS") (pin "TP") (pinfunction "TP_TP") (pintype "input"))
    )
    (net (code "150") (name "Net-(SIPB-JTAG_TRSTN)") (class "Default")
      (node (ref "R59") (pin "2") (pinfunction "2_2") (pintype "passive"))
      (node (ref "SIP") (pin "B10") (pinfunction "JTAG_TRSTN_B10") (pintype "bidirectional"))
      (node (ref "TRSTN") (pin "TP") (pinfunction "TP_TP") (pintype "input"))
    )
    (net (code "151") (name "Net-(SIPB-MMC0_CD_C15)") (class "Default")
      (node (ref "R65") (pin "1") (pinfunction "1_1") (pintype "passive"))
      (node (ref "SIP") (pin "C15") (pinfunction "MMC0_CD_C15_C15") (pintype "bidirectional"))
      (node (ref "X2") (pin "CD") (pinfunction "CD#_CD") (pintype "bidirectional"))
    )
    (net (code "152") (name "Net-(SIPB-MMC0_CLK_G17)") (class "Default")
      (node (ref "R57") (pin "1") (pinfunction "1_1") (pintype "passive"))
      (node (ref "SIP") (pin "G17") (pinfunction "MMC0_CLK_G17_G17") (pintype "bidirectional"))
      (node (ref "X2") (pin "5") (pinfunction "CLK_5") (pintype "bidirectional"))
    )
    (net (code "153") (name "Net-(SIPB-MMC0_CMD_G18)") (class "Default")
      (node (ref "R56") (pin "1") (pinfunction "1_1") (pintype "passive"))
      (node (ref "SIP") (pin "G18") (pinfunction "MMC0_CMD_G18_G18") (pintype "bidirectional"))
      (node (ref "X2") (pin "3") (pinfunction "CMD/DI_3") (pintype "bidirectional"))
    )
    (net (code "154") (name "Net-(SIPB-MMC0_DAT0_G16)") (class "Default")
      (node (ref "R55") (pin "1") (pinfunction "1_1") (pintype "passive"))
      (node (ref "SIP") (pin "G16") (pinfunction "MMC0_DAT0_G16_G16") (pintype "bidirectional"))
      (node (ref "X2") (pin "7") (pinfunction "DAT0/DO_7") (pintype "bidirectional"))
    )
    (net (code "155") (name "Net-(SIPB-MMC0_DAT1_G15)") (class "Default")
      (node (ref "R54") (pin "1") (pinfunction "1_1") (pintype "passive"))
      (node (ref "SIP") (pin "G15") (pinfunction "MMC0_DAT1_G15_G15") (pintype "bidirectional"))
      (node (ref "X2") (pin "8") (pinfunction "DAT1_8") (pintype "bidirectional"))
    )
    (net (code "156") (name "Net-(SIPB-MMC0_DAT2_F18)") (class "Default")
      (node (ref "R35") (pin "1") (pinfunction "1_1") (pintype "passive"))
      (node (ref "SIP") (pin "F18") (pinfunction "MMC0_DAT2_F18_F18") (pintype "bidirectional"))
      (node (ref "X2") (pin "1") (pinfunction "DAT2_1") (pintype "bidirectional"))
    )
    (net (code "157") (name "Net-(SIPB-MMC0_DAT3_F17)") (class "Default")
      (node (ref "R26") (pin "1") (pinfunction "1_1") (pintype "passive"))
      (node (ref "SIP") (pin "F17") (pinfunction "MMC0_DAT3_F17_F17") (pintype "bidirectional"))
      (node (ref "X2") (pin "2") (pinfunction "DAT3/CS_2") (pintype "bidirectional"))
    )
    (net (code "158") (name "Net-(SIPB-MMC1_CLK_U9)") (class "Default")
      (node (ref "R15") (pin "1") (pinfunction "1_1") (pintype "passive"))
      (node (ref "SIP") (pin "U9") (pinfunction "MMC1_CLK_U9_U9") (pintype "bidirectional"))
    )
    (net (code "159") (name "Net-(SIPB-OSC0_GND)") (class "Default")
      (node (ref "C29") (pin "2") (pinfunction "2_2") (pintype "passive"))
      (node (ref "C30") (pin "2") (pinfunction "2_2") (pintype "passive"))
      (node (ref "SIP") (pin "L20") (pinfunction "OSC0_GND_L20") (pintype "bidirectional"))
    )
    (net (code "160") (name "Net-(SIPB-OSC0_IN)") (class "Default")
      (node (ref "C30") (pin "1") (pinfunction "1_1") (pintype "passive"))
      (node (ref "R20") (pin "2") (pinfunction "2_2") (pintype "passive"))
      (node (ref "SIP") (pin "M20") (pinfunction "OSC0_IN_M20") (pintype "bidirectional"))
      (node (ref "Y1") (pin "2") (pinfunction "P$2_2") (pintype "passive"))
    )
    (net (code "161") (name "Net-(SIPB-OSC0_OUT)") (class "Default")
      (node (ref "C29") (pin "1") (pinfunction "1_1") (pintype "passive"))
      (node (ref "R20") (pin "1") (pinfunction "1_1") (pintype "passive"))
      (node (ref "SIP") (pin "K20") (pinfunction "OSC0_OUT_K20") (pintype "bidirectional"))
      (node (ref "Y1") (pin "1") (pinfunction "P$1_1") (pintype "passive"))
    )
    (net (code "162") (name "Net-(SIPB-OSC1_GND)") (class "Default")
      (node (ref "C31") (pin "2") (pinfunction "2_2") (pintype "passive"))
      (node (ref "C32") (pin "1") (pinfunction "1_1") (pintype "passive"))
      (node (ref "SIP") (pin "G20") (pinfunction "OSC1_GND_G20") (pintype "bidirectional"))
    )
    (net (code "163") (name "Net-(SIPB-OSC1_IN)") (class "Default")
      (node (ref "C31") (pin "1") (pinfunction "1_1") (pintype "passive"))
      (node (ref "R18") (pin "2") (pinfunction "2_2") (pintype "passive"))
      (node (ref "SIP") (pin "H20") (pinfunction "OSC1_IN_H20") (pintype "bidirectional"))
      (node (ref "Y2") (pin "P$2") (pinfunction "P$2_P$2") (pintype "passive"))
    )
    (net (code "164") (name "Net-(SIPB-OSC1_OUT)") (class "Default")
      (node (ref "C32") (pin "2") (pinfunction "2_2") (pintype "passive"))
      (node (ref "R18") (pin "1") (pinfunction "1_1") (pintype "passive"))
      (node (ref "SIP") (pin "F20") (pinfunction "OSC1_OUT_F20") (pintype "bidirectional"))
      (node (ref "Y2") (pin "P$1") (pinfunction "P$1_P$1") (pintype "passive"))
    )
    (net (code "165") (name "Net-(SIPC-ADC_VREFP)") (class "Default")
      (node (ref "C42") (pin "1") (pinfunction "1_1") (pintype "passive"))
      (node (ref "C43") (pin "1") (pinfunction "1_1") (pintype "passive"))
      (node (ref "R111") (pin "2") (pinfunction "2_2") (pintype "passive"))
      (node (ref "SIP") (pin "B9") (pinfunction "ADC_VREFP_B9") (pintype "bidirectional"))
    )
    (net (code "166") (name "Net-(SIPC-AIN7)") (class "Default")
      (node (ref "R109") (pin "2") (pinfunction "2_2") (pintype "passive"))
      (node (ref "R110") (pin "1") (pinfunction "1_1") (pintype "passive"))
      (node (ref "SIP") (pin "C9") (pinfunction "AIN7_C9") (pintype "bidirectional"))
    )
    (net (code "167") (name "Net-(SIPC-LCD_DATA11_U4)") (class "Default")
      (node (ref "R135") (pin "2") (pinfunction "2_2") (pintype "passive"))
      (node (ref "SIP") (pin "U4") (pinfunction "LCD_DATA11_U4_U4") (pintype "bidirectional"))
    )
    (net (code "168") (name "Net-(SIPC-USB0_VBUS)") (class "Default")
      (node (ref "R149") (pin "1") (pinfunction "1_1") (pintype "passive"))
      (node (ref "SIP") (pin "P15") (pinfunction "USB0_VBUS_P15") (pintype "bidirectional"))
    )
    (net (code "169") (name "Net-(SIPC-USB1_ID)") (class "Default")
      (node (ref "R150") (pin "1") (pinfunction "1_1") (pintype "passive"))
      (node (ref "SIP") (pin "P17") (pinfunction "USB1_ID_P17") (pintype "bidirectional"))
    )
    (net (code "170") (name "Net-(SIPC-USB1_VBUS)") (class "Default")
      (node (ref "R156") (pin "1") (pinfunction "1_1") (pintype "passive"))
      (node (ref "SIP") (pin "T18") (pinfunction "USB1_VBUS_T18") (pintype "bidirectional"))
    )
    (net (code "171") (name "Net-(SIPE-RTC_KALDO_ENN)") (class "Default")
      (node (ref "R158") (pin "1") (pinfunction "1_1") (pintype "passive"))
      (node (ref "SIP") (pin "B4") (pinfunction "RTC_KALDO_ENN_B4") (pintype "bidirectional"))
    )
    (net (code "172") (name "Net-(U5-WP)") (class "Default")
      (node (ref "R58") (pin "1") (pinfunction "1_1") (pintype "passive"))
      (node (ref "U5") (pin "5") (pinfunction "WP_5") (pintype "input"))
      (node (ref "WP") (pin "P$1") (pinfunction "TP_P$1") (pintype "bidirectional"))
    )
    (net (code "173") (name "Net-(U7-BT_AUD_CLK)") (class "Default")
      (node (ref "R124") (pin "2") (pinfunction "2_2") (pintype "passive"))
      (node (ref "U7") (pin "60") (pinfunction "BT_AUD_CLK_60") (pintype "bidirectional"))
    )
    (net (code "174") (name "Net-(U7-BT_AUD_FSYNC)") (class "Default")
      (node (ref "R123") (pin "2") (pinfunction "2_2") (pintype "passive"))
      (node (ref "U7") (pin "58") (pinfunction "BT_AUD_FSYNC_58") (pintype "bidirectional"))
    )
    (net (code "175") (name "Net-(U7-BT_AUD_IN)") (class "Default")
      (node (ref "R97") (pin "2") (pinfunction "2_2") (pintype "passive"))
      (node (ref "U7") (pin "56") (pinfunction "BT_AUD_IN_56") (pintype "bidirectional"))
    )
    (net (code "176") (name "Net-(U7-BT_AUD_OUT)") (class "Default")
      (node (ref "R100") (pin "2") (pinfunction "2_2") (pintype "passive"))
      (node (ref "U7") (pin "57") (pinfunction "BT_AUD_OUT_57") (pintype "bidirectional"))
    )
    (net (code "177") (name "Net-(U7-BT_HCI_CTS)") (class "Default")
      (node (ref "R86") (pin "2") (pinfunction "2_2") (pintype "passive"))
      (node (ref "U7") (pin "51") (pinfunction "BT_HCI_CTS_51") (pintype "bidirectional"))
    )
    (net (code "178") (name "Net-(U7-BT_HCI_RTS)") (class "Default")
      (node (ref "R85") (pin "2") (pinfunction "2_2") (pintype "passive"))
      (node (ref "U7") (pin "50") (pinfunction "BT_HCI_RTS_50") (pintype "bidirectional"))
    )
    (net (code "179") (name "Net-(U7-BT_HCI_RX)") (class "Default")
      (node (ref "R96") (pin "2") (pinfunction "2_2") (pintype "passive"))
      (node (ref "U7") (pin "53") (pinfunction "BT_HCI_RX_53") (pintype "bidirectional"))
    )
    (net (code "180") (name "Net-(U7-BT_HCI_TX)") (class "Default")
      (node (ref "R92") (pin "2") (pinfunction "2_2") (pintype "passive"))
      (node (ref "U7") (pin "52") (pinfunction "BT_HCI_TX_52") (pintype "bidirectional"))
    )
    (net (code "181") (name "Net-(U7-RF_ANT1)") (class "Default")
      (node (ref "C48") (pin "2") (pinfunction "2_2") (pintype "passive"))
      (node (ref "U7") (pin "32") (pinfunction "RF_ANT1_32") (pintype "bidirectional"))
    )
    (net (code "182") (name "Net-(U7-RF_ANT2)") (class "Default")
      (node (ref "C58") (pin "2") (pinfunction "2_2") (pintype "passive"))
      (node (ref "U7") (pin "18") (pinfunction "RF_ANT2_18") (pintype "bidirectional"))
    )
    (net (code "183") (name "Net-(U7-WLAN_IRQ)") (class "Default")
      (node (ref "R84") (pin "2") (pinfunction "2_2") (pintype "passive"))
      (node (ref "R9") (pin "2") (pinfunction "2_2") (pintype "passive"))
      (node (ref "U7") (pin "14") (pinfunction "WLAN_IRQ_14") (pintype "bidirectional"))
    )
    (net (code "184") (name "Net-(U7-WL_SDIO_CLK)") (class "Default")
      (node (ref "R78") (pin "2") (pinfunction "2_2") (pintype "passive"))
      (node (ref "U7") (pin "8") (pinfunction "WL_SDIO_CLK_8") (pintype "bidirectional"))
    )
    (net (code "185") (name "Net-(U7-WL_SDIO_CMD)") (class "Default")
      (node (ref "R79") (pin "2") (pinfunction "2_2") (pintype "passive"))
      (node (ref "U7") (pin "6") (pinfunction "WL_SDIO_CMD_6") (pintype "bidirectional"))
    )
    (net (code "186") (name "Net-(U7-WL_SDIO_D0)") (class "Default")
      (node (ref "R80") (pin "2") (pinfunction "2_2") (pintype "passive"))
      (node (ref "U7") (pin "10") (pinfunction "WL_SDIO_D0_10") (pintype "bidirectional"))
    )
    (net (code "187") (name "Net-(U7-WL_SDIO_D1)") (class "Default")
      (node (ref "R81") (pin "2") (pinfunction "2_2") (pintype "passive"))
      (node (ref "U7") (pin "11") (pinfunction "WL_SDIO_D1_11") (pintype "bidirectional"))
    )
    (net (code "188") (name "Net-(U7-WL_SDIO_D2)") (class "Default")
      (node (ref "R82") (pin "2") (pinfunction "2_2") (pintype "passive"))
      (node (ref "U7") (pin "12") (pinfunction "WL_SDIO_D2_12") (pintype "bidirectional"))
    )
    (net (code "189") (name "Net-(U7-WL_SDIO_D3)") (class "Default")
      (node (ref "R83") (pin "2") (pinfunction "2_2") (pintype "passive"))
      (node (ref "U7") (pin "13") (pinfunction "WL_SDIO_D3_13") (pintype "bidirectional"))
    )
    (net (code "190") (name "Net-(U10-OE)") (class "Default")
      (node (ref "R106") (pin "2") (pinfunction "2_2") (pintype "passive"))
      (node (ref "R93") (pin "2") (pinfunction "2_2") (pintype "passive"))
      (node (ref "U10") (pin "10") (pinfunction "OE_10") (pintype "bidirectional"))
      (node (ref "U2") (pin "1") (pinfunction "OE_1") (pintype "input"))
      (node (ref "U9") (pin "10") (pinfunction "OE_10") (pintype "bidirectional"))
    )
    (net (code "191") (name "Net-(U13-VDDI)") (class "Default")
      (node (ref "C36") (pin "1") (pinfunction "1_1") (pintype "passive"))
      (node (ref "U13") (pin "C2") (pinfunction "VDDI_C2") (pintype "bidirectional"))
    )
    (net (code "192") (name "Net-(X3-GND)") (class "Default")
      (node (ref "L4") (pin "2") (pinfunction "2_2") (pintype "passive"))
      (node (ref "X3") (pin "4") (pinfunction "GND_4") (pintype "bidirectional"))
    )
    (net (code "193") (name "Net-(X3-VBUS)") (class "Default")
      (node (ref "L5") (pin "2") (pinfunction "2_2") (pintype "passive"))
      (node (ref "X3") (pin "1") (pinfunction "VBUS_1") (pintype "bidirectional"))
    )
    (net (code "194") (name "PAUSE_BTN") (class "Default")
      (node (ref "PAU") (pin "2") (pinfunction "2_2") (pintype "passive"))
      (node (ref "SIP") (pin "T6") (pinfunction "TIMER5_T6_T6") (pintype "bidirectional"))
    )
    (net (code "195") (name "PMIC_INT") (class "Default")
      (node (ref "SIP") (pin "B18") (pinfunction "EXTINTN_B18") (pintype "bidirectional"))
      (node (ref "SIP") (pin "B19") (pinfunction "PMIC_OUT_NINT_B19") (pintype "output"))
    )
    (net (code "196") (name "PMIC_NWAKEUP") (class "Default")
      (node (ref "SIP") (pin "A19") (pinfunction "PMIC_OUT_NWAKEUP_A19") (pintype "output"))
      (node (ref "SIP") (pin "C5") (pinfunction "EXT_WAKEUP_C5") (pintype "bidirectional"))
    )
    (net (code "197") (name "PMIC_PGOOD") (class "Default")
      (node (ref "SIP") (pin "A20") (pinfunction "PMIC_OUT_PGOOD_A20") (pintype "output"))
      (node (ref "SIP") (pin "B15") (pinfunction "PWRONRSTN_B15") (pintype "bidirectional"))
      (node (ref "U6") (pin "2") (pinfunction "A_2") (pintype "input"))
    )
    (net (code "198") (name "POWER_BTN") (class "Default")
      (node (ref "POW") (pin "2") (pinfunction "2_2") (pintype "passive"))
      (node (ref "SIP") (pin "D20") (pinfunction "PMIC_IN_PB_IN_D20") (pintype "bidirectional"))
    )
    (net (code "199") (name "PRU_E_A") (class "Default")
      (node (ref "E4") (pin "3") (pinfunction "3_3") (pintype "bidirectional"))
      (node (ref "SIP") (pin "V13") (pinfunction "GPIO1_14_V13_V13") (pintype "bidirectional"))
    )
    (net (code "200") (name "PRU_E_B") (class "Default")
      (node (ref "E4") (pin "4") (pinfunction "4_4") (pintype "bidirectional"))
      (node (ref "SIP") (pin "U13") (pinfunction "GPIO1_15_U13_U13") (pintype "bidirectional"))
    )
    (net (code "201") (name "PWM_1A") (class "Default")
      (node (ref "H1") (pin "23") (pinfunction "PWMA_23") (pintype "bidirectional"))
      (node (ref "SIP") (pin "U14") (pinfunction "EHRPWM1A_U14_U14") (pintype "bidirectional"))
    )
    (net (code "202") (name "PWM_1B") (class "Default")
      (node (ref "H1") (pin "15") (pinfunction "PWMB_15") (pintype "bidirectional"))
      (node (ref "SIP") (pin "T14") (pinfunction "EHRPWM1B_T14_T14") (pintype "bidirectional"))
    )
    (net (code "203") (name "PWM_2A") (class "Default")
      (node (ref "H2") (pin "23") (pinfunction "PWMA_23") (pintype "bidirectional"))
      (node (ref "SIP") (pin "U10") (pinfunction "EHRPWM2A_U10_U10") (pintype "bidirectional"))
    )
    (net (code "204") (name "PWM_2B") (class "Default")
      (node (ref "H2") (pin "15") (pinfunction "PWMB_15") (pintype "bidirectional"))
      (node (ref "SIP") (pin "T10") (pinfunction "EHRPWM2B_T10_T10") (pintype "bidirectional"))
    )
    (net (code "205") (name "PWR_LED") (class "Default")
      (node (ref "ON") (pin "C") (pinfunction "C_C") (pintype "passive"))
      (node (ref "R24") (pin "1") (pinfunction "1_1") (pintype "passive"))
    )
    (net (code "206") (name "RESET") (class "Default")
      (node (ref "C33") (pin "1") (pinfunction "1_1") (pintype "passive"))
      (node (ref "R60") (pin "1") (pinfunction "1_1") (pintype "passive"))
      (node (ref "RST") (pin "2") (pinfunction "2_2") (pintype "passive"))
      (node (ref "SIP") (pin "A10") (pinfunction "WARMRSTN_A10") (pintype "bidirectional"))
      (node (ref "U6") (pin "4") (pinfunction "Y_4") (pintype "output"))
    )
    (net (code "207") (name "SD_BOOT") (class "Default")
      (node (ref "R77") (pin "2") (pinfunction "2_2") (pintype "passive"))
      (node (ref "SD") (pin "2") (pinfunction "2_2") (pintype "passive"))
    )
    (net (code "208") (name "SERVO_EN") (class "Default")
      (node (ref "6VREG") (pin "8") (pinfunction "EN_8") (pintype "bidirectional"))
      (node (ref "R46") (pin "2") (pinfunction "2_2") (pintype "passive"))
      (node (ref "SIP") (pin "U3") (pinfunction "LCD_DATA10_U3_U3") (pintype "bidirectional"))
    )
    (net (code "209") (name "SPI1_MISO") (class "Default")
      (node (ref "S1.1") (pin "4") (pinfunction "4_4") (pintype "bidirectional"))
      (node (ref "S1.2") (pin "4") (pinfunction "4_4") (pintype "bidirectional"))
      (node (ref "SIP") (pin "B13") (pinfunction "SPI1_D0_B13_B13") (pintype "bidirectional"))
    )
    (net (code "210") (name "SPI1_MOSI") (class "Default")
      (node (ref "S1.1") (pin "3") (pinfunction "3_3") (pintype "bidirectional"))
      (node (ref "S1.2") (pin "3") (pinfunction "3_3") (pintype "bidirectional"))
      (node (ref "SIP") (pin "D12") (pinfunction "SPI1_D1_D12_D12") (pintype "bidirectional"))
    )
    (net (code "211") (name "SPI1_SCK") (class "Default")
      (node (ref "S1.1") (pin "5") (pinfunction "5_5") (pintype "bidirectional"))
      (node (ref "S1.2") (pin "5") (pinfunction "5_5") (pintype "bidirectional"))
      (node (ref "SIP") (pin "A13") (pinfunction "SPI1_CLK_A13_A13") (pintype "bidirectional"))
    )
    (net (code "212") (name "SPI1_SS1") (class "Default")
      (node (ref "S1.1") (pin "6") (pinfunction "6_6") (pintype "bidirectional"))
      (node (ref "SIP") (pin "H18") (pinfunction "H18_H18") (pintype "bidirectional"))
    )
    (net (code "213") (name "SPI1_SS2") (class "Default")
      (node (ref "S1.2") (pin "6") (pinfunction "6_6") (pintype "bidirectional"))
      (node (ref "SIP") (pin "C18") (pinfunction "GPIO0_7_C18_C18") (pintype "bidirectional"))
    )
    (net (code "214") (name "SVO1") (class "Default")
      (node (ref "R36") (pin "1") (pinfunction "1_1") (pintype "passive"))
      (node (ref "R50") (pin "1") (pinfunction "1_1") (pintype "passive"))
      (node (ref "SIP") (pin "U5") (pinfunction "LCD_VSYNC_U5_U5") (pintype "bidirectional"))
    )
    (net (code "215") (name "SVO2") (class "Default")
      (node (ref "R37") (pin "1") (pinfunction "1_1") (pintype "passive"))
      (node (ref "R51") (pin "1") (pinfunction "1_1") (pintype "passive"))
      (node (ref "SIP") (pin "V5") (pinfunction "LCD_PCLK_V5_V5") (pintype "bidirectional"))
    )
    (net (code "216") (name "SVO3") (class "Default")
      (node (ref "R38") (pin "1") (pinfunction "1_1") (pintype "passive"))
      (node (ref "R52") (pin "1") (pinfunction "1_1") (pintype "passive"))
      (node (ref "SIP") (pin "R5") (pinfunction "LCD_HSYNC_R5_R5") (pintype "bidirectional"))
    )
    (net (code "217") (name "SVO4") (class "Default")
      (node (ref "R39") (pin "1") (pinfunction "1_1") (pintype "passive"))
      (node (ref "R53") (pin "1") (pinfunction "1_1") (pintype "passive"))
      (node (ref "SIP") (pin "R6") (pinfunction "LCD_DE_R6_R6") (pintype "bidirectional"))
    )
    (net (code "218") (name "SVO5") (class "Default")
      (node (ref "R125") (pin "2") (pinfunction "2_2") (pintype "passive"))
      (node (ref "R40") (pin "1") (pinfunction "1_1") (pintype "passive"))
      (node (ref "SIP") (pin "T3") (pinfunction "LCD_DATA6_T3_T3") (pintype "bidirectional"))
    )
    (net (code "219") (name "SVO6") (class "Default")
      (node (ref "R127") (pin "2") (pinfunction "2_2") (pintype "passive"))
      (node (ref "R41") (pin "1") (pinfunction "1_1") (pintype "passive"))
      (node (ref "SIP") (pin "T4") (pinfunction "LCD_DATA7_T4_T4") (pintype "bidirectional"))
    )
    (net (code "220") (name "SVO7") (class "Default")
      (node (ref "R120") (pin "1") (pinfunction "1_1") (pintype "passive"))
      (node (ref "R42") (pin "1") (pinfunction "1_1") (pintype "passive"))
      (node (ref "SIP") (pin "T1") (pinfunction "LCD_DATA4_T1_T1") (pintype "bidirectional"))
    )
    (net (code "221") (name "SVO8") (class "Default")
      (node (ref "R122") (pin "1") (pinfunction "1_1") (pintype "passive"))
      (node (ref "R43") (pin "1") (pinfunction "1_1") (pintype "passive"))
      (node (ref "SIP") (pin "T2") (pinfunction "LCD_DATA5_T2_T2") (pintype "bidirectional"))
    )
    (net (code "222") (name "SYS_5V") (class "Default")
      (node (ref "C62") (pin "1") (pinfunction "1_1") (pintype "passive"))
      (node (ref "R121") (pin "2") (pinfunction "2_2") (pintype "passive"))
      (node (ref "SIP") (pin "W4") (pinfunction "VOUT_SYS_5V_0_W4") (pintype "power_in"))
      (node (ref "SIP") (pin "Y4") (pinfunction "VOUT_SYS_5V_1_Y4") (pintype "power_in"))
      (node (ref "TP1") (pin "TP") (pinfunction "TP_TP") (pintype "input"))
      (node (ref "U1") (pin "3") (pinfunction "VCC_3") (pintype "power_in"))
      (node (ref "U8") (pin "3") (pinfunction "IN2_3") (pintype "input"))
    )
    (net (code "223") (name "UART0_RX") (class "Default")
      (node (ref "SIP") (pin "E15") (pinfunction "UART0_RXD_E15_E15") (pintype "bidirectional"))
      (node (ref "UT0") (pin "3") (pinfunction "3_3") (pintype "bidirectional"))
    )
    (net (code "224") (name "UART0_TX") (class "Default")
      (node (ref "SIP") (pin "E16") (pinfunction "UART0_TXD_E16_E16") (pintype "bidirectional"))
      (node (ref "UT0") (pin "4") (pinfunction "4_4") (pintype "bidirectional"))
    )
    (net (code "225") (name "UART1_RX") (class "Default")
      (node (ref "SIP") (pin "D16") (pinfunction "UART1_RXD_D16_D16") (pintype "bidirectional"))
      (node (ref "UT1") (pin "3") (pinfunction "3_3") (pintype "bidirectional"))
    )
    (net (code "226") (name "UART1_TX") (class "Default")
      (node (ref "SIP") (pin "D15") (pinfunction "UART1_TXD_D15_D15") (pintype "bidirectional"))
      (node (ref "UT1") (pin "4") (pinfunction "4_4") (pintype "bidirectional"))
    )
    (net (code "227") (name "UART2_RX") (class "Default")
      (node (ref "GPS") (pin "3") (pinfunction "3_3") (pintype "bidirectional"))
      (node (ref "SIP") (pin "A17") (pinfunction "UART2_RXD_A17_A17") (pintype "bidirectional"))
    )
    (net (code "228") (name "UART2_TX") (class "Default")
      (node (ref "GPS") (pin "4") (pinfunction "4_4") (pintype "bidirectional"))
      (node (ref "SIP") (pin "B17") (pinfunction "UART2_TXD_B17_B17") (pintype "bidirectional"))
    )
    (net (code "229") (name "UART3_CTSN") (class "Default")
      (node (ref "R89") (pin "1") (pinfunction "1_1") (pintype "passive"))
      (node (ref "SIP") (pin "M17") (pinfunction "M17_M17") (pintype "bidirectional"))
      (node (ref "U10") (pin "12") (pinfunction "B8_12") (pintype "bidirectional"))
    )
    (net (code "230") (name "UART3_RTSN") (class "Default")
      (node (ref "R108") (pin "1") (pinfunction "1_1") (pintype "passive"))
      (node (ref "SIP") (pin "M18") (pinfunction "M18_M18") (pintype "bidirectional"))
      (node (ref "U10") (pin "13") (pinfunction "B7_13") (pintype "bidirectional"))
    )
    (net (code "231") (name "UART3_RX") (class "Default")
      (node (ref "SIP") (pin "L17") (pinfunction "L17_L17") (pintype "bidirectional"))
      (node (ref "U10") (pin "14") (pinfunction "B6_14") (pintype "bidirectional"))
    )
    (net (code "232") (name "UART3_TX") (class "Default")
      (node (ref "SIP") (pin "L16") (pinfunction "L16_L16") (pintype "bidirectional"))
      (node (ref "U10") (pin "15") (pinfunction "B5_15") (pintype "bidirectional"))
    )
    (net (code "233") (name "UART4_RX") (class "Default")
      (node (ref "DSM2") (pin "P$3") (pinfunction "3_P$3") (pintype "bidirectional"))
      (node (ref "SIP") (pin "T17") (pinfunction "UART4_RXD_T17_T17") (pintype "bidirectional"))
    )
    (net (code "234") (name "UART5_RX") (class "Default")
      (node (ref "R131") (pin "2") (pinfunction "2_2") (pintype "passive"))
      (node (ref "SIP") (pin "U2") (pinfunction "LCD_DATA9_U2_U2") (pintype "bidirectional"))
      (node (ref "UT5") (pin "3") (pinfunction "3_3") (pintype "bidirectional"))
    )
    (net (code "235") (name "UART5_TX") (class "Default")
      (node (ref "R129") (pin "2") (pinfunction "2_2") (pintype "passive"))
      (node (ref "SIP") (pin "U1") (pinfunction "LCD_DATA8_U1_U1") (pintype "bidirectional"))
      (node (ref "UT5") (pin "4") (pinfunction "4_4") (pintype "bidirectional"))
    )
    (net (code "236") (name "USB0_D_N") (class "Default")
      (node (ref "SIP") (pin "N18") (pinfunction "USB0_DM_N18") (pintype "bidirectional"))
      (node (ref "U3") (pin "2") (pinfunction "D-_2") (pintype "bidirectional"))
      (node (ref "X4") (pin "D-") (pinfunction "D-_D-") (pintype "input"))
    )
    (net (code "237") (name "USB0_D_P") (class "Default")
      (node (ref "SIP") (pin "N17") (pinfunction "USB0_DP_N17") (pintype "bidirectional"))
      (node (ref "U3") (pin "1") (pinfunction "D+_1") (pintype "bidirectional"))
      (node (ref "X4") (pin "D+") (pinfunction "D+_D+") (pintype "input"))
    )
    (net (code "238") (name "USB0_ID") (class "Default")
      (node (ref "SIP") (pin "P16") (pinfunction "USB0_ID_P16") (pintype "bidirectional"))
      (node (ref "U3") (pin "3") (pinfunction "ID_3") (pintype "bidirectional"))
      (node (ref "X4") (pin "ID") (pinfunction "ID_ID") (pintype "input"))
    )
    (net (code "239") (name "USB0_VBUS") (class "Default")
      (node (ref "C54") (pin "1") (pinfunction "1_1") (pintype "passive"))
      (node (ref "R112") (pin "2") (pinfunction "2_2") (pintype "passive"))
      (node (ref "R149") (pin "2") (pinfunction "2_2") (pintype "passive"))
      (node (ref "U3") (pin "6") (pinfunction "VBUS_6") (pintype "bidirectional"))
      (node (ref "X4") (pin "VBUS") (pinfunction "VBUS_VBUS") (pintype "input"))
    )
    (net (code "240") (name "USB1_D_N") (class "Default")
      (node (ref "SIP") (pin "R18") (pinfunction "USB1_DM_R18") (pintype "bidirectional"))
      (node (ref "U4") (pin "2") (pinfunction "D-_2") (pintype "bidirectional"))
      (node (ref "X3") (pin "2") (pinfunction "D-_2") (pintype "bidirectional"))
    )
    (net (code "241") (name "USB1_D_P") (class "Default")
      (node (ref "SIP") (pin "R17") (pinfunction "USB1_DP_R17") (pintype "bidirectional"))
      (node (ref "U4") (pin "1") (pinfunction "D+_1") (pintype "bidirectional"))
      (node (ref "X3") (pin "3") (pinfunction "D+_3") (pintype "bidirectional"))
    )
    (net (code "242") (name "USB1_VBUS") (class "Default")
      (node (ref "C45") (pin "1") (pinfunction "1_1") (pintype "passive"))
      (node (ref "C46") (pin "1") (pinfunction "1_1") (pintype "passive"))
      (node (ref "C55") (pin "1") (pinfunction "1_1") (pintype "passive"))
      (node (ref "C61") (pin "2") (pinfunction "2_2") (pintype "passive"))
      (node (ref "L5") (pin "1") (pinfunction "1_1") (pintype "passive"))
      (node (ref "R119") (pin "1") (pinfunction "1_1") (pintype "passive"))
      (node (ref "R121") (pin "1") (pinfunction "1_1") (pintype "passive"))
      (node (ref "R156") (pin "2") (pinfunction "2_2") (pintype "passive"))
      (node (ref "U4") (pin "6") (pinfunction "VBUS_6") (pintype "bidirectional"))
      (node (ref "U8") (pin "4") (pinfunction "OUT_4") (pintype "output"))
    )
    (net (code "243") (name "USB_DC") (class "Default")
      (node (ref "R112") (pin "1") (pinfunction "1_1") (pintype "passive"))
      (node (ref "SIP") (pin "Y8") (pinfunction "VIN_USB_0_Y8") (pintype "power_in"))
      (node (ref "SIP") (pin "Y9") (pinfunction "VIN_USB_1_Y9") (pintype "power_in"))
    )
    (net (code "244") (name "USR_LED0") (class "Default")
      (node (ref "0") (pin "A") (pinfunction "A_A") (pintype "passive"))
      (node (ref "SIP") (pin "V15") (pinfunction "USR0_V15_V15") (pintype "bidirectional"))
    )
    (net (code "245") (name "USR_LED1") (class "Default")
      (node (ref "1") (pin "A") (pinfunction "A_A") (pintype "passive"))
      (node (ref "SIP") (pin "U15") (pinfunction "USR1_U15_U15") (pintype "bidirectional"))
    )
    (net (code "246") (name "USR_LED2") (class "Default")
      (node (ref "2") (pin "A") (pinfunction "A_A") (pintype "passive"))
      (node (ref "SIP") (pin "T15") (pinfunction "USR2_T15_T15") (pintype "bidirectional"))
    )
    (net (code "247") (name "USR_LED3") (class "Default")
      (node (ref "3") (pin "A") (pinfunction "A_A") (pintype "passive"))
      (node (ref "SIP") (pin "V16") (pinfunction "USR3_V16_V16") (pintype "bidirectional"))
    )
    (net (code "248") (name "VCC") (class "Default")
      (node (ref "12V") (pin "IN") (pinfunction "IN_IN") (pintype "bidirectional"))
      (node (ref "C12") (pin "1") (pinfunction "1_1") (pintype "passive"))
      (node (ref "C7") (pin "1") (pinfunction "1_1") (pintype "passive"))
      (node (ref "CHG") (pin "A") (pinfunction "A_A") (pintype "passive"))
      (node (ref "CHGIC") (pin "2") (pinfunction "VIN_2") (pintype "bidirectional"))
      (node (ref "D3") (pin "A") (pinfunction "A_A") (pintype "passive"))
      (node (ref "R1") (pin "1") (pinfunction "1_1") (pintype "passive"))
    )
    (net (code "249") (name "VCC_CHG") (class "Default")
      (node (ref "C4") (pin "2") (pinfunction "2_2") (pintype "passive"))
      (node (ref "CHGIC") (pin "3") (pinfunction "VCC_3") (pintype "bidirectional"))
      (node (ref "R5") (pin "2") (pinfunction "2_2") (pintype "passive"))
    )
    (net (code "250") (name "VDD_1V8") (class "Default")
      (node (ref "C47") (pin "1") (pinfunction "1_1") (pintype "passive"))
      (node (ref "C50") (pin "1") (pinfunction "1_1") (pintype "passive"))
      (node (ref "C52") (pin "1") (pinfunction "1_1") (pintype "passive"))
      (node (ref "C57") (pin "2") (pinfunction "2_2") (pintype "passive"))
      (node (ref "C60") (pin "2") (pinfunction "2_2") (pintype "passive"))
      (node (ref "OSC1") (pin "4") (pinfunction "VCC_4") (pintype "bidirectional"))
      (node (ref "R101") (pin "1") (pinfunction "1_1") (pintype "passive"))
      (node (ref "R102") (pin "1") (pinfunction "1_1") (pintype "passive"))
      (node (ref "R103") (pin "1") (pinfunction "1_1") (pintype "passive"))
      (node (ref "R105") (pin "1") (pinfunction "1_1") (pintype "passive"))
      (node (ref "R9") (pin "1") (pinfunction "1_1") (pintype "passive"))
      (node (ref "R90") (pin "2") (pinfunction "2_2") (pintype "passive"))
      (node (ref "R98") (pin "1") (pinfunction "1_1") (pintype "passive"))
      (node (ref "R99") (pin "1") (pinfunction "1_1") (pintype "passive"))
      (node (ref "SIP") (pin "D10") (pinfunction "VDD_1V84_D10") (pintype "bidirectional"))
      (node (ref "SIP") (pin "E9") (pinfunction "VDD_1V83_E9") (pintype "bidirectional"))
      (node (ref "SIP") (pin "N16") (pinfunction "VOUT_LDO3_1P8V_0_N16") (pintype "power_in"))
      (node (ref "SIP") (pin "R16") (pinfunction "VOUT_LDO3_1P8V_1_R16") (pintype "power_in"))
      (node (ref "U10") (pin "2") (pinfunction "VCCA_2") (pintype "bidirectional"))
      (node (ref "U2") (pin "5") (pinfunction "VCC_5") (pintype "power_in"))
      (node (ref "U7") (pin "38") (pinfunction "VIO_38") (pintype "bidirectional"))
      (node (ref "U9") (pin "2") (pinfunction "VCCA_2") (pintype "bidirectional"))
    )
    (net (code "251") (name "VDD_3V3AUX") (class "Default")
      (node (ref "ON") (pin "A") (pinfunction "A_A") (pintype "passive"))
      (node (ref "SIP") (pin "Y11") (pinfunction "VOUT_LDO2_3P3V_Y11") (pintype "power_in"))
    )
    (net (code "252") (name "VDD_ADC") (class "Default")
      (node (ref "ADC") (pin "2") (pinfunction "2_2") (pintype "bidirectional"))
      (node (ref "C44") (pin "1") (pinfunction "1_1") (pintype "passive"))
      (node (ref "R111") (pin "1") (pinfunction "1_1") (pintype "passive"))
      (node (ref "SIP") (pin "A4") (pinfunction "VOUT_ADC_1P8V_0_A4") (pintype "bidirectional"))
      (node (ref "SIP") (pin "A5") (pinfunction "VOUT_ADC_1P8V_1_A5") (pintype "bidirectional"))
      (node (ref "SIP") (pin "D8") (pinfunction "VDDA_ADC_D8") (pintype "bidirectional"))
    )
    (net (code "253") (name "VDD_RTC") (class "Default")
      (node (ref "SIP") (pin "E14") (pinfunction "VDD_RTC3_E14") (pintype "bidirectional"))
      (node (ref "U6") (pin "5") (pinfunction "VCC_5") (pintype "power_in"))
    )
    (net (code "254") (name "VIN_BAT_0") (class "Default")
      (node (ref "SIP") (pin "Y2") (pinfunction "VIN_BAT_0_Y2") (pintype "power_in"))
    )
    (net (code "255") (name "VIN_BAT_1") (class "Default")
      (node (ref "SIP") (pin "Y3") (pinfunction "VIN_BAT_1_Y3") (pintype "power_in"))
    )
    (net (code "256") (name "V_BATT") (class "Default")
      (node (ref "6VREG") (pin "9") (pinfunction "VIN_9") (pintype "bidirectional"))
      (node (ref "C11") (pin "+") (pinfunction "+_+") (pintype "passive"))
      (node (ref "C20") (pin "2") (pinfunction "2_2") (pintype "passive"))
      (node (ref "C25") (pin "1") (pinfunction "1_1") (pintype "passive"))
      (node (ref "C26") (pin "1") (pinfunction "1_1") (pintype "passive"))
      (node (ref "CHGIC") (pin "9") (pinfunction "BATT_9") (pintype "bidirectional"))
      (node (ref "D2") (pin "A") (pinfunction "A_A") (pintype "passive"))
      (node (ref "H1") (pin "13") (pinfunction "VM2_13") (pintype "bidirectional"))
      (node (ref "H1") (pin "14") (pinfunction "VM3_14") (pintype "bidirectional"))
      (node (ref "H1") (pin "24") (pinfunction "VM1_24") (pintype "bidirectional"))
      (node (ref "H2") (pin "13") (pinfunction "VM2_13") (pintype "bidirectional"))
      (node (ref "H2") (pin "14") (pinfunction "VM3_14") (pintype "bidirectional"))
      (node (ref "H2") (pin "24") (pinfunction "VM1_24") (pintype "bidirectional"))
      (node (ref "LIPO") (pin "P$1") (pinfunction "1_P$1") (pintype "passive"))
      (node (ref "R19") (pin "1") (pinfunction "1_1") (pintype "passive"))
      (node (ref "R28") (pin "1") (pinfunction "1_1") (pintype "passive"))
      (node (ref "R34") (pin "1") (pinfunction "1_1") (pintype "passive"))
      (node (ref "R4") (pin "1") (pinfunction "1_1") (pintype "passive"))
    )
    (net (code "257") (name "V_DIV_BAT") (class "Default")
      (node (ref "R19") (pin "2") (pinfunction "2_2") (pintype "passive"))
      (node (ref "R25") (pin "1") (pinfunction "1_1") (pintype "passive"))
      (node (ref "SIP") (pin "A8") (pinfunction "AIN6_A8") (pintype "bidirectional"))
    )
    (net (code "258") (name "V_DIV_DC") (class "Default")
      (node (ref "R1") (pin "2") (pinfunction "2_2") (pintype "passive"))
      (node (ref "R14") (pin "1") (pinfunction "1_1") (pintype "passive"))
      (node (ref "SIP") (pin "B8") (pinfunction "AIN5_B8") (pintype "bidirectional"))
    )
    (net (code "259") (name "WIFI_LED") (class "Default")
      (node (ref "SIP") (pin "A15") (pinfunction "GPIO0_19_A15_A15") (pintype "bidirectional"))
      (node (ref "WIFI") (pin "A") (pinfunction "A_A") (pintype "passive"))
    )
    (net (code "260") (name "WLAN_IRQ") (class "Default")
      (node (ref "SIP") (pin "K16") (pinfunction "K16_K16") (pintype "bidirectional"))
      (node (ref "U2") (pin "4") (pinfunction "Y_4") (pintype "output"))
    )
    (net (code "261") (name "WL_BT_OE") (class "Default")
      (node (ref "R93") (pin "1") (pinfunction "1_1") (pintype "passive"))
      (node (ref "SIP") (pin "L18") (pinfunction "L18_L18") (pintype "bidirectional"))
    )
    (net (code "262") (name "WL_EN") (class "Default")
      (node (ref "SIP") (pin "K18") (pinfunction "K18_K18") (pintype "bidirectional"))
      (node (ref "U9") (pin "20") (pinfunction "B1_20") (pintype "bidirectional"))
    )
    (net (code "263") (name "WL_EN_1V8") (class "Default")
      (node (ref "R87") (pin "1") (pinfunction "1_1") (pintype "passive"))
      (node (ref "U7") (pin "40") (pinfunction "WLAN_EN_40") (pintype "bidirectional"))
      (node (ref "U9") (pin "1") (pinfunction "A1_1") (pintype "bidirectional"))
    )
    (net (code "264") (name "WL_IRQ") (class "Default")
      (node (ref "R84") (pin "1") (pinfunction "1_1") (pintype "passive"))
      (node (ref "U2") (pin "2") (pinfunction "A_2") (pintype "input"))
    )
    (net (code "265") (name "WL_SDIO_CLK") (class "Default")
      (node (ref "R103") (pin "2") (pinfunction "2_2") (pintype "passive"))
      (node (ref "R78") (pin "1") (pinfunction "1_1") (pintype "passive"))
      (node (ref "U9") (pin "8") (pinfunction "A7_8") (pintype "bidirectional"))
    )
    (net (code "266") (name "WL_SDIO_CMD") (class "Default")
      (node (ref "R105") (pin "2") (pinfunction "2_2") (pintype "passive"))
      (node (ref "R79") (pin "1") (pinfunction "1_1") (pintype "passive"))
      (node (ref "U9") (pin "9") (pinfunction "A8_9") (pintype "bidirectional"))
    )
    (net (code "267") (name "WL_SDIO_D0") (class "Default")
      (node (ref "R80") (pin "1") (pinfunction "1_1") (pintype "passive"))
      (node (ref "R98") (pin "2") (pinfunction "2_2") (pintype "passive"))
      (node (ref "U9") (pin "7") (pinfunction "A6_7") (pintype "bidirectional"))
    )
    (net (code "268") (name "WL_SDIO_D1") (class "Default")
      (node (ref "R81") (pin "1") (pinfunction "1_1") (pintype "passive"))
      (node (ref "R99") (pin "2") (pinfunction "2_2") (pintype "passive"))
      (node (ref "U9") (pin "6") (pinfunction "A5_6") (pintype "bidirectional"))
    )
    (net (code "269") (name "WL_SDIO_D2") (class "Default")
      (node (ref "R101") (pin "2") (pinfunction "2_2") (pintype "passive"))
      (node (ref "R82") (pin "1") (pinfunction "1_1") (pintype "passive"))
      (node (ref "U9") (pin "5") (pinfunction "A4_5") (pintype "bidirectional"))
    )
    (net (code "270") (name "WL_SDIO_D3") (class "Default")
      (node (ref "R102") (pin "2") (pinfunction "2_2") (pintype "passive"))
      (node (ref "R83") (pin "1") (pinfunction "1_1") (pintype "passive"))
      (node (ref "U9") (pin "4") (pinfunction "A3_4") (pintype "bidirectional"))
    )
    (net (code "271") (name "unconnected-(12V-PadOUT_CON)") (class "Default")
      (node (ref "12V") (pin "OUT_CON") (pinfunction "OUT_CON_OUT_CON") (pintype "bidirectional"))
    )
    (net (code "272") (name "unconnected-(CHGIC-ACOK-Pad12)") (class "Default")
      (node (ref "CHGIC") (pin "12") (pinfunction "ACOK_12") (pintype "bidirectional"))
    )
    (net (code "273") (name "unconnected-(CHGIC-CELL-Pad4)") (class "Default")
      (node (ref "CHGIC") (pin "4") (pinfunction "CELL_4") (pintype "bidirectional"))
    )
    (net (code "274") (name "unconnected-(CHGIC-SEL-Pad5)") (class "Default")
      (node (ref "CHGIC") (pin "5") (pinfunction "SEL_5") (pintype "bidirectional"))
    )
    (net (code "275") (name "unconnected-(FUD1-PadP$1)") (class "Default")
      (node (ref "FUD1") (pin "P$1") (pinfunction "P$1_P$1") (pintype "no_connect"))
    )
    (net (code "276") (name "unconnected-(FUD2-PadP$1)") (class "Default")
      (node (ref "FUD2") (pin "P$1") (pinfunction "P$1_P$1") (pintype "no_connect"))
    )
    (net (code "277") (name "unconnected-(FUD3-PadP$1)") (class "Default")
      (node (ref "FUD3") (pin "P$1") (pinfunction "P$1_P$1") (pintype "no_connect"))
    )
    (net (code "278") (name "unconnected-(FUD4-PadP$1)") (class "Default")
      (node (ref "FUD4") (pin "P$1") (pinfunction "P$1_P$1") (pintype "no_connect"))
    )
    (net (code "279") (name "unconnected-(FUD5-PadP$1)") (class "Default")
      (node (ref "FUD5") (pin "P$1") (pinfunction "P$1_P$1") (pintype "no_connect"))
    )
    (net (code "280") (name "unconnected-(FUD6-PadP$1)") (class "Default")
      (node (ref "FUD6") (pin "P$1") (pinfunction "P$1_P$1") (pintype "no_connect"))
    )
    (net (code "281") (name "unconnected-(GPS-Pad1)") (class "Default")
      (node (ref "GPS") (pin "1") (pinfunction "1_1") (pintype "bidirectional"))
    )
    (net (code "282") (name "unconnected-(IMU-AUX_CL-Pad7)") (class "Default")
      (node (ref "IMU") (pin "7") (pinfunction "AUX_CL_7") (pintype "bidirectional"))
    )
    (net (code "283") (name "unconnected-(IMU-AUX_DA-Pad21)") (class "Default")
      (node (ref "IMU") (pin "21") (pinfunction "AUX_DA_21") (pintype "bidirectional"))
    )
    (net (code "284") (name "unconnected-(IMU-FSYNC-Pad11)") (class "Default")
      (node (ref "IMU") (pin "11") (pinfunction "FSYNC_11") (pintype "bidirectional"))
    )
    (net (code "285") (name "unconnected-(IMU-NC-Pad2)") (class "Default")
      (node (ref "IMU") (pin "2") (pinfunction "NC_2") (pintype "bidirectional"))
    )
    (net (code "286") (name "unconnected-(IMU-NC-Pad3)") (class "Default")
      (node (ref "IMU") (pin "3") (pinfunction "NC_3") (pintype "bidirectional"))
    )
    (net (code "287") (name "unconnected-(IMU-NC-Pad4)") (class "Default")
      (node (ref "IMU") (pin "4") (pinfunction "NC_4") (pintype "bidirectional"))
    )
    (net (code "288") (name "unconnected-(IMU-NC-Pad5)") (class "Default")
      (node (ref "IMU") (pin "5") (pinfunction "NC_5") (pintype "bidirectional"))
    )
    (net (code "289") (name "unconnected-(IMU-NC-Pad6)") (class "Default")
      (node (ref "IMU") (pin "6") (pinfunction "NC_6") (pintype "bidirectional"))
    )
    (net (code "290") (name "unconnected-(IMU-NC-Pad14)") (class "Default")
      (node (ref "IMU") (pin "14") (pinfunction "NC_14") (pintype "bidirectional"))
    )
    (net (code "291") (name "unconnected-(IMU-NC-Pad15)") (class "Default")
      (node (ref "IMU") (pin "15") (pinfunction "NC_15") (pintype "bidirectional"))
    )
    (net (code "292") (name "unconnected-(IMU-NC-Pad16)") (class "Default")
      (node (ref "IMU") (pin "16") (pinfunction "NC_16") (pintype "bidirectional"))
    )
    (net (code "293") (name "unconnected-(IMU-NC-Pad17)") (class "Default")
      (node (ref "IMU") (pin "17") (pinfunction "NC_17") (pintype "bidirectional"))
    )
    (net (code "294") (name "unconnected-(IMU-RESV-Pad19)") (class "Default")
      (node (ref "IMU") (pin "19") (pinfunction "RESV_19") (pintype "bidirectional"))
    )
    (net (code "295") (name "unconnected-(PROT-CO-Pad3)") (class "Default")
      (node (ref "PROT") (pin "3") (pinfunction "CO_3") (pintype "bidirectional"))
    )
    (net (code "296") (name "unconnected-(PROT-DP-Pad4)") (class "Default")
      (node (ref "PROT") (pin "4") (pinfunction "DP_4") (pintype "bidirectional"))
    )
    (net (code "297") (name "unconnected-(SIPA-BAT_TEMP-PadW1)") (class "Default")
      (node (ref "SIP") (pin "W1") (pinfunction "BAT_TEMP_W1") (pintype "bidirectional"))
    )
    (net (code "298") (name "unconnected-(SIPA-BAT_VOLT-PadY1)") (class "Default")
      (node (ref "SIP") (pin "Y1") (pinfunction "BAT_VOLT_Y1") (pintype "bidirectional"))
    )
    (net (code "299") (name "unconnected-(SIPA-L1_IN-PadY14)") (class "Default")
      (node (ref "SIP") (pin "Y14") (pinfunction "L1_IN_Y14") (pintype "bidirectional"))
    )
    (net (code "300") (name "unconnected-(SIPA-L1_OUT-PadY13)") (class "Default")
      (node (ref "SIP") (pin "Y13") (pinfunction "L1_OUT_Y13") (pintype "bidirectional"))
    )
    (net (code "301") (name "unconnected-(SIPA-L2_IN-PadY17)") (class "Default")
      (node (ref "SIP") (pin "Y17") (pinfunction "L2_IN_Y17") (pintype "bidirectional"))
    )
    (net (code "302") (name "unconnected-(SIPA-L2_OUT-PadY16)") (class "Default")
      (node (ref "SIP") (pin "Y16") (pinfunction "L2_OUT_Y16") (pintype "bidirectional"))
    )
    (net (code "303") (name "unconnected-(SIPA-L3_IN-PadY20)") (class "Default")
      (node (ref "SIP") (pin "Y20") (pinfunction "L3_IN_Y20") (pintype "bidirectional"))
    )
    (net (code "304") (name "unconnected-(SIPA-L3_OUT-PadY19)") (class "Default")
      (node (ref "SIP") (pin "Y19") (pinfunction "L3_OUT_Y19") (pintype "bidirectional"))
    )
    (net (code "305") (name "unconnected-(SIPC-AIN4-PadC8)") (class "Default")
      (node (ref "SIP") (pin "C8") (pinfunction "AIN4_C8") (pintype "bidirectional"))
    )
    (net (code "306") (name "unconnected-(SIPC-USB0_CE-PadM15)") (class "Default")
      (node (ref "SIP") (pin "M15") (pinfunction "USB0_CE_M15") (pintype "bidirectional"))
    )
    (net (code "307") (name "unconnected-(SIPC-USB0_DRVVBUS-PadF16)") (class "Default")
      (node (ref "SIP") (pin "F16") (pinfunction "USB0_DRVVBUS_F16") (pintype "bidirectional"))
    )
    (net (code "308") (name "unconnected-(SIPC-USB1_CE-PadP18)") (class "Default")
      (node (ref "SIP") (pin "P18") (pinfunction "USB1_CE_P18") (pintype "bidirectional"))
    )
    (net (code "309") (name "unconnected-(SIPC-USB1_DRVVBUS-PadF15)") (class "Default")
      (node (ref "SIP") (pin "F15") (pinfunction "USB1_DRVVBUS_F15") (pintype "bidirectional"))
    )
    (net (code "310") (name "unconnected-(SIPD-NC1-PadV11)") (class "Default")
      (node (ref "SIP") (pin "V11") (pinfunction "NC1_V11") (pintype "bidirectional"))
    )
    (net (code "311") (name "unconnected-(SIPD-NC2-PadU11)") (class "Default")
      (node (ref "SIP") (pin "U11") (pinfunction "NC2_U11") (pintype "bidirectional"))
    )
    (net (code "312") (name "unconnected-(SIPD-NC3-PadV10)") (class "Default")
      (node (ref "SIP") (pin "V10") (pinfunction "NC3_V10") (pintype "bidirectional"))
    )
    (net (code "313") (name "unconnected-(SIPD-NC4-PadB1)") (class "Default")
      (node (ref "SIP") (pin "B1") (pinfunction "NC4_B1") (pintype "bidirectional"))
    )
    (net (code "314") (name "unconnected-(SIPD-NC5-PadB2)") (class "Default")
      (node (ref "SIP") (pin "B2") (pinfunction "NC5_B2") (pintype "bidirectional"))
    )
    (net (code "315") (name "unconnected-(SIPD-NC6-PadB3)") (class "Default")
      (node (ref "SIP") (pin "B3") (pinfunction "NC6_B3") (pintype "bidirectional"))
    )
    (net (code "316") (name "unconnected-(SIPD-NC12-PadC1)") (class "Default")
      (node (ref "SIP") (pin "C1") (pinfunction "NC12_C1") (pintype "bidirectional"))
    )
    (net (code "317") (name "unconnected-(SIPD-NC20-PadC2)") (class "Default")
      (node (ref "SIP") (pin "C2") (pinfunction "NC20_C2") (pintype "bidirectional"))
    )
    (net (code "318") (name "unconnected-(SIPD-NC21-PadC3)") (class "Default")
      (node (ref "SIP") (pin "C3") (pinfunction "NC21_C3") (pintype "bidirectional"))
    )
    (net (code "319") (name "unconnected-(SIPD-NC22-PadC4)") (class "Default")
      (node (ref "SIP") (pin "C4") (pinfunction "NC22_C4") (pintype "bidirectional"))
    )
    (net (code "320") (name "unconnected-(SIPD-NC23-PadP2)") (class "Default")
      (node (ref "SIP") (pin "P2") (pinfunction "NC23_P2") (pintype "bidirectional"))
    )
    (net (code "321") (name "unconnected-(SIPD-NC24-PadD1)") (class "Default")
      (node (ref "SIP") (pin "D1") (pinfunction "NC24_D1") (pintype "bidirectional"))
    )
    (net (code "322") (name "unconnected-(SIPD-NC31-PadD2)") (class "Default")
      (node (ref "SIP") (pin "D2") (pinfunction "NC31_D2") (pintype "bidirectional"))
    )
    (net (code "323") (name "unconnected-(SIPD-NC32-PadD3)") (class "Default")
      (node (ref "SIP") (pin "D3") (pinfunction "NC32_D3") (pintype "bidirectional"))
    )
    (net (code "324") (name "unconnected-(SIPD-NC33-PadD4)") (class "Default")
      (node (ref "SIP") (pin "D4") (pinfunction "NC33_D4") (pintype "bidirectional"))
    )
    (net (code "325") (name "unconnected-(SIPD-NC34-PadD5)") (class "Default")
      (node (ref "SIP") (pin "D5") (pinfunction "NC34_D5") (pintype "bidirectional"))
    )
    (net (code "326") (name "unconnected-(SIPD-NC45-PadP3)") (class "Default")
      (node (ref "SIP") (pin "P3") (pinfunction "NC45_P3") (pintype "bidirectional"))
    )
    (net (code "327") (name "unconnected-(SIPD-NC46-PadE1)") (class "Default")
      (node (ref "SIP") (pin "E1") (pinfunction "NC46_E1") (pintype "bidirectional"))
    )
    (net (code "328") (name "unconnected-(SIPD-NC47-PadE2)") (class "Default")
      (node (ref "SIP") (pin "E2") (pinfunction "NC47_E2") (pintype "bidirectional"))
    )
    (net (code "329") (name "unconnected-(SIPD-NC48-PadE3)") (class "Default")
      (node (ref "SIP") (pin "E3") (pinfunction "NC48_E3") (pintype "bidirectional"))
    )
    (net (code "330") (name "unconnected-(SIPD-NC58-PadE4)") (class "Default")
      (node (ref "SIP") (pin "E4") (pinfunction "NC58_E4") (pintype "bidirectional"))
    )
    (net (code "331") (name "unconnected-(SIPD-NC59-PadF1)") (class "Default")
      (node (ref "SIP") (pin "F1") (pinfunction "NC59_F1") (pintype "bidirectional"))
    )
    (net (code "332") (name "unconnected-(SIPD-NC60-PadF2)") (class "Default")
      (node (ref "SIP") (pin "F2") (pinfunction "NC60_F2") (pintype "bidirectional"))
    )
    (net (code "333") (name "unconnected-(SIPD-NC61-PadF3)") (class "Default")
      (node (ref "SIP") (pin "F3") (pinfunction "NC61_F3") (pintype "bidirectional"))
    )
    (net (code "334") (name "unconnected-(SIPD-NC68-PadF4)") (class "Default")
      (node (ref "SIP") (pin "F4") (pinfunction "NC68_F4") (pintype "bidirectional"))
    )
    (net (code "335") (name "unconnected-(SIPD-NC69-PadG1)") (class "Default")
      (node (ref "SIP") (pin "G1") (pinfunction "NC69_G1") (pintype "bidirectional"))
    )
    (net (code "336") (name "unconnected-(SIPD-NC70-PadG2)") (class "Default")
      (node (ref "SIP") (pin "G2") (pinfunction "NC70_G2") (pintype "bidirectional"))
    )
    (net (code "337") (name "unconnected-(SIPD-NC71-PadG3)") (class "Default")
      (node (ref "SIP") (pin "G3") (pinfunction "NC71_G3") (pintype "bidirectional"))
    )
    (net (code "338") (name "unconnected-(SIPD-NC76-PadG4)") (class "Default")
      (node (ref "SIP") (pin "G4") (pinfunction "NC76_G4") (pintype "bidirectional"))
    )
    (net (code "339") (name "unconnected-(SIPD-NC77-PadH1)") (class "Default")
      (node (ref "SIP") (pin "H1") (pinfunction "NC77_H1") (pintype "bidirectional"))
    )
    (net (code "340") (name "unconnected-(SIPD-NC78-PadH2)") (class "Default")
      (node (ref "SIP") (pin "H2") (pinfunction "NC78_H2") (pintype "bidirectional"))
    )
    (net (code "341") (name "unconnected-(SIPD-NC79-PadH3)") (class "Default")
      (node (ref "SIP") (pin "H3") (pinfunction "NC79_H3") (pintype "bidirectional"))
    )
    (net (code "342") (name "unconnected-(SIPD-NC84-PadH4)") (class "Default")
      (node (ref "SIP") (pin "H4") (pinfunction "NC84_H4") (pintype "bidirectional"))
    )
    (net (code "343") (name "unconnected-(SIPD-NC85-PadJ1)") (class "Default")
      (node (ref "SIP") (pin "J1") (pinfunction "NC85_J1") (pintype "bidirectional"))
    )
    (net (code "344") (name "unconnected-(SIPD-NC86-PadJ2)") (class "Default")
      (node (ref "SIP") (pin "J2") (pinfunction "NC86_J2") (pintype "bidirectional"))
    )
    (net (code "345") (name "unconnected-(SIPD-NC87-PadJ3)") (class "Default")
      (node (ref "SIP") (pin "J3") (pinfunction "NC87_J3") (pintype "bidirectional"))
    )
    (net (code "346") (name "unconnected-(SIPD-NC94-PadJ4)") (class "Default")
      (node (ref "SIP") (pin "J4") (pinfunction "NC94_J4") (pintype "bidirectional"))
    )
    (net (code "347") (name "unconnected-(SIPD-NC95-PadK1)") (class "Default")
      (node (ref "SIP") (pin "K1") (pinfunction "NC95_K1") (pintype "bidirectional"))
    )
    (net (code "348") (name "unconnected-(SIPD-NC96-PadK2)") (class "Default")
      (node (ref "SIP") (pin "K2") (pinfunction "NC96_K2") (pintype "bidirectional"))
    )
    (net (code "349") (name "unconnected-(SIPD-NC97-PadK3)") (class "Default")
      (node (ref "SIP") (pin "K3") (pinfunction "NC97_K3") (pintype "bidirectional"))
    )
    (net (code "350") (name "unconnected-(SIPD-NC104-PadK4)") (class "Default")
      (node (ref "SIP") (pin "K4") (pinfunction "NC104_K4") (pintype "bidirectional"))
    )
    (net (code "351") (name "unconnected-(SIPD-NC105-PadL1)") (class "Default")
      (node (ref "SIP") (pin "L1") (pinfunction "NC105_L1") (pintype "bidirectional"))
    )
    (net (code "352") (name "unconnected-(SIPD-NC106-PadL2)") (class "Default")
      (node (ref "SIP") (pin "L2") (pinfunction "NC106_L2") (pintype "bidirectional"))
    )
    (net (code "353") (name "unconnected-(SIPD-NC107-PadL3)") (class "Default")
      (node (ref "SIP") (pin "L3") (pinfunction "NC107_L3") (pintype "bidirectional"))
    )
    (net (code "354") (name "unconnected-(SIPD-NC111-PadL4)") (class "Default")
      (node (ref "SIP") (pin "L4") (pinfunction "NC111_L4") (pintype "bidirectional"))
    )
    (net (code "355") (name "unconnected-(SIPD-NC112-PadM1)") (class "Default")
      (node (ref "SIP") (pin "M1") (pinfunction "NC112_M1") (pintype "bidirectional"))
    )
    (net (code "356") (name "unconnected-(SIPD-NC113-PadM2)") (class "Default")
      (node (ref "SIP") (pin "M2") (pinfunction "NC113_M2") (pintype "bidirectional"))
    )
    (net (code "357") (name "unconnected-(SIPD-NC114-PadM3)") (class "Default")
      (node (ref "SIP") (pin "M3") (pinfunction "NC114_M3") (pintype "bidirectional"))
    )
    (net (code "358") (name "unconnected-(SIPD-NC121-PadM4)") (class "Default")
      (node (ref "SIP") (pin "M4") (pinfunction "NC121_M4") (pintype "bidirectional"))
    )
    (net (code "359") (name "unconnected-(SIPD-NC122-PadP4)") (class "Default")
      (node (ref "SIP") (pin "P4") (pinfunction "NC122_P4") (pintype "bidirectional"))
    )
    (net (code "360") (name "unconnected-(SIPD-NC123-PadN1)") (class "Default")
      (node (ref "SIP") (pin "N1") (pinfunction "NC123_N1") (pintype "bidirectional"))
    )
    (net (code "361") (name "unconnected-(SIPD-NC124-PadN2)") (class "Default")
      (node (ref "SIP") (pin "N2") (pinfunction "NC124_N2") (pintype "bidirectional"))
    )
    (net (code "362") (name "unconnected-(SIPD-NC136-PadN3)") (class "Default")
      (node (ref "SIP") (pin "N3") (pinfunction "NC136_N3") (pintype "bidirectional"))
    )
    (net (code "363") (name "unconnected-(SIPD-NC137-PadN4)") (class "Default")
      (node (ref "SIP") (pin "N4") (pinfunction "NC137_N4") (pintype "bidirectional"))
    )
    (net (code "364") (name "unconnected-(SIPD-NC138-PadP1)") (class "Default")
      (node (ref "SIP") (pin "P1") (pinfunction "NC138_P1") (pintype "bidirectional"))
    )
    (net (code "365") (name "unconnected-(SIPE-CAP_VBB_MPU-PadC10)") (class "Default")
      (node (ref "SIP") (pin "C10") (pinfunction "CAP_VBB_MPU_C10") (pintype "bidirectional"))
    )
    (net (code "366") (name "unconnected-(SIPE-CAP_VDD_RTC-PadD6)") (class "Default")
      (node (ref "SIP") (pin "D6") (pinfunction "CAP_VDD_RTC_D6") (pintype "bidirectional"))
    )
    (net (code "367") (name "unconnected-(SIPE-CAP_VDD_SRAM_COR-PadD9)") (class "Default")
      (node (ref "SIP") (pin "D9") (pinfunction "CAP_VDD_SRAM_COR_D9") (pintype "bidirectional"))
    )
    (net (code "368") (name "unconnected-(SIPE-CAP_VDD_SRAM_MPU-PadD11)") (class "Default")
      (node (ref "SIP") (pin "D11") (pinfunction "CAP_VDD_SRAM_MPU_D11") (pintype "bidirectional"))
    )
    (net (code "369") (name "unconnected-(SIPE-TESTOUT-PadA3)") (class "Default")
      (node (ref "SIP") (pin "A3") (pinfunction "TESTOUT_A3") (pintype "bidirectional"))
    )
    (net (code "370") (name "unconnected-(SIPE-VDDS_DDR1-PadE5)") (class "Default")
      (node (ref "SIP") (pin "E5") (pinfunction "VDDS_DDR1_E5") (pintype "bidirectional"))
    )
    (net (code "371") (name "unconnected-(SIPE-VDDS_DDR2-PadF5)") (class "Default")
      (node (ref "SIP") (pin "F5") (pinfunction "VDDS_DDR2_F5") (pintype "bidirectional"))
    )
    (net (code "372") (name "unconnected-(SIPE-VDDS_DDR3-PadG5)") (class "Default")
      (node (ref "SIP") (pin "G5") (pinfunction "VDDS_DDR3_G5") (pintype "bidirectional"))
    )
    (net (code "373") (name "unconnected-(SIPE-VDDS_DDR4-PadH5)") (class "Default")
      (node (ref "SIP") (pin "H5") (pinfunction "VDDS_DDR4_H5") (pintype "bidirectional"))
    )
    (net (code "374") (name "unconnected-(SIPE-VDDS_DDR5-PadJ5)") (class "Default")
      (node (ref "SIP") (pin "J5") (pinfunction "VDDS_DDR5_J5") (pintype "bidirectional"))
    )
    (net (code "375") (name "unconnected-(SIPE-VDDS_DDR6-PadK5)") (class "Default")
      (node (ref "SIP") (pin "K5") (pinfunction "VDDS_DDR6_K5") (pintype "bidirectional"))
    )
    (net (code "376") (name "unconnected-(SIPE-VDDS_DDR7-PadL5)") (class "Default")
      (node (ref "SIP") (pin "L5") (pinfunction "VDDS_DDR7_L5") (pintype "bidirectional"))
    )
    (net (code "377") (name "unconnected-(SIPE-VDD_3V3A1-PadE10)") (class "Default")
      (node (ref "SIP") (pin "E10") (pinfunction "VDD_3V3A1_E10") (pintype "bidirectional"))
    )
    (net (code "378") (name "unconnected-(SIPE-VDD_3V3A2-PadE11)") (class "Default")
      (node (ref "SIP") (pin "E11") (pinfunction "VDD_3V3A2_E11") (pintype "bidirectional"))
    )
    (net (code "379") (name "unconnected-(SIPE-VDD_3V3A3-PadE12)") (class "Default")
      (node (ref "SIP") (pin "E12") (pinfunction "VDD_3V3A3_E12") (pintype "bidirectional"))
    )
    (net (code "380") (name "unconnected-(SIPE-VDD_3V3A4-PadE13)") (class "Default")
      (node (ref "SIP") (pin "E13") (pinfunction "VDD_3V3A4_E13") (pintype "bidirectional"))
    )
    (net (code "381") (name "unconnected-(SIPE-VDD_3V3A5-PadF14)") (class "Default")
      (node (ref "SIP") (pin "F14") (pinfunction "VDD_3V3A5_F14") (pintype "bidirectional"))
    )
    (net (code "382") (name "unconnected-(SIPE-VDD_3V3A6-PadG14)") (class "Default")
      (node (ref "SIP") (pin "G14") (pinfunction "VDD_3V3A6_G14") (pintype "bidirectional"))
    )
    (net (code "383") (name "unconnected-(SIPE-VDD_3V3A7-PadH14)") (class "Default")
      (node (ref "SIP") (pin "H14") (pinfunction "VDD_3V3A7_H14") (pintype "bidirectional"))
    )
    (net (code "384") (name "unconnected-(SIPE-VDD_3V3A8-PadJ14)") (class "Default")
      (node (ref "SIP") (pin "J14") (pinfunction "VDD_3V3A8_J14") (pintype "bidirectional"))
    )
    (net (code "385") (name "unconnected-(SIPE-VDD_3V3A9-PadK14)") (class "Default")
      (node (ref "SIP") (pin "K14") (pinfunction "VDD_3V3A9_K14") (pintype "bidirectional"))
    )
    (net (code "386") (name "unconnected-(SIPE-VDD_3V3A10-PadL14)") (class "Default")
      (node (ref "SIP") (pin "L14") (pinfunction "VDD_3V3A10_L14") (pintype "bidirectional"))
    )
    (net (code "387") (name "unconnected-(SIPE-VDD_3V3A11-PadN5)") (class "Default")
      (node (ref "SIP") (pin "N5") (pinfunction "VDD_3V3A11_N5") (pintype "bidirectional"))
    )
    (net (code "388") (name "unconnected-(SIPE-VDD_3V3A12-PadN15)") (class "Default")
      (node (ref "SIP") (pin "N15") (pinfunction "VDD_3V3A12_N15") (pintype "bidirectional"))
    )
    (net (code "389") (name "unconnected-(SIPE-VDD_3V3A13-PadP5)") (class "Default")
      (node (ref "SIP") (pin "P5") (pinfunction "VDD_3V3A13_P5") (pintype "bidirectional"))
    )
    (net (code "390") (name "unconnected-(SIPE-VDD_3V3A14-PadP6)") (class "Default")
      (node (ref "SIP") (pin "P6") (pinfunction "VDD_3V3A14_P6") (pintype "bidirectional"))
    )
    (net (code "391") (name "unconnected-(SIPE-VDD_3V3A15-PadP7)") (class "Default")
      (node (ref "SIP") (pin "P7") (pinfunction "VDD_3V3A15_P7") (pintype "bidirectional"))
    )
    (net (code "392") (name "unconnected-(SIPE-VDD_3V3A16-PadP8)") (class "Default")
      (node (ref "SIP") (pin "P8") (pinfunction "VDD_3V3A16_P8") (pintype "bidirectional"))
    )
    (net (code "393") (name "unconnected-(SIPE-VDD_3V3A17-PadP10)") (class "Default")
      (node (ref "SIP") (pin "P10") (pinfunction "VDD_3V3A17_P10") (pintype "bidirectional"))
    )
    (net (code "394") (name "unconnected-(SIPE-VDD_3V3A18-PadP11)") (class "Default")
      (node (ref "SIP") (pin "P11") (pinfunction "VDD_3V3A18_P11") (pintype "bidirectional"))
    )
    (net (code "395") (name "unconnected-(SIPE-VDD_3V3A19-PadP12)") (class "Default")
      (node (ref "SIP") (pin "P12") (pinfunction "VDD_3V3A19_P12") (pintype "bidirectional"))
    )
    (net (code "396") (name "unconnected-(SIPE-VDD_3V3A20-PadP13)") (class "Default")
      (node (ref "SIP") (pin "P13") (pinfunction "VDD_3V3A20_P13") (pintype "bidirectional"))
    )
    (net (code "397") (name "unconnected-(SIPE-VDD_3V3A21-PadR15)") (class "Default")
      (node (ref "SIP") (pin "R15") (pinfunction "VDD_3V3A21_R15") (pintype "bidirectional"))
    )
    (net (code "398") (name "unconnected-(SIPE-VDD_CORE1-PadF6)") (class "Default")
      (node (ref "SIP") (pin "F6") (pinfunction "VDD_CORE1_F6") (pintype "bidirectional"))
    )
    (net (code "399") (name "unconnected-(SIPE-VDD_CORE2-PadF7)") (class "Default")
      (node (ref "SIP") (pin "F7") (pinfunction "VDD_CORE2_F7") (pintype "bidirectional"))
    )
    (net (code "400") (name "unconnected-(SIPE-VDD_CORE3-PadG6)") (class "Default")
      (node (ref "SIP") (pin "G6") (pinfunction "VDD_CORE3_G6") (pintype "bidirectional"))
    )
    (net (code "401") (name "unconnected-(SIPE-VDD_CORE4-PadG7)") (class "Default")
      (node (ref "SIP") (pin "G7") (pinfunction "VDD_CORE4_G7") (pintype "bidirectional"))
    )
    (net (code "402") (name "unconnected-(SIPE-VDD_CORE5-PadG10)") (class "Default")
      (node (ref "SIP") (pin "G10") (pinfunction "VDD_CORE5_G10") (pintype "bidirectional"))
    )
    (net (code "403") (name "unconnected-(SIPE-VDD_CORE6-PadH11)") (class "Default")
      (node (ref "SIP") (pin "H11") (pinfunction "VDD_CORE6_H11") (pintype "bidirectional"))
    )
    (net (code "404") (name "unconnected-(SIPE-VDD_CORE7-PadJ12)") (class "Default")
      (node (ref "SIP") (pin "J12") (pinfunction "VDD_CORE7_J12") (pintype "bidirectional"))
    )
    (net (code "405") (name "unconnected-(SIPE-VDD_CORE8-PadK6)") (class "Default")
      (node (ref "SIP") (pin "K6") (pinfunction "VDD_CORE8_K6") (pintype "bidirectional"))
    )
    (net (code "406") (name "unconnected-(SIPE-VDD_CORE9-PadK8)") (class "Default")
      (node (ref "SIP") (pin "K8") (pinfunction "VDD_CORE9_K8") (pintype "bidirectional"))
    )
    (net (code "407") (name "unconnected-(SIPE-VDD_CORE10-PadK12)") (class "Default")
      (node (ref "SIP") (pin "K12") (pinfunction "VDD_CORE10_K12") (pintype "bidirectional"))
    )
    (net (code "408") (name "unconnected-(SIPE-VDD_CORE11-PadL6)") (class "Default")
      (node (ref "SIP") (pin "L6") (pinfunction "VDD_CORE11_L6") (pintype "bidirectional"))
    )
    (net (code "409") (name "unconnected-(SIPE-VDD_CORE12-PadL7)") (class "Default")
      (node (ref "SIP") (pin "L7") (pinfunction "VDD_CORE12_L7") (pintype "bidirectional"))
    )
    (net (code "410") (name "unconnected-(SIPE-VDD_CORE13-PadL8)") (class "Default")
      (node (ref "SIP") (pin "L8") (pinfunction "VDD_CORE13_L8") (pintype "bidirectional"))
    )
    (net (code "411") (name "unconnected-(SIPE-VDD_CORE14-PadL9)") (class "Default")
      (node (ref "SIP") (pin "L9") (pinfunction "VDD_CORE14_L9") (pintype "bidirectional"))
    )
    (net (code "412") (name "unconnected-(SIPE-VDD_CORE15-PadM11)") (class "Default")
      (node (ref "SIP") (pin "M11") (pinfunction "VDD_CORE15_M11") (pintype "bidirectional"))
    )
    (net (code "413") (name "unconnected-(SIPE-VDD_CORE16-PadM13)") (class "Default")
      (node (ref "SIP") (pin "M13") (pinfunction "VDD_CORE16_M13") (pintype "bidirectional"))
    )
    (net (code "414") (name "unconnected-(SIPE-VDD_CORE17-PadN8)") (class "Default")
      (node (ref "SIP") (pin "N8") (pinfunction "VDD_CORE17_N8") (pintype "bidirectional"))
    )
    (net (code "415") (name "unconnected-(SIPE-VDD_CORE18-PadN9)") (class "Default")
      (node (ref "SIP") (pin "N9") (pinfunction "VDD_CORE18_N9") (pintype "bidirectional"))
    )
    (net (code "416") (name "unconnected-(SIPE-VDD_CORE19-PadN12)") (class "Default")
      (node (ref "SIP") (pin "N12") (pinfunction "VDD_CORE19_N12") (pintype "bidirectional"))
    )
    (net (code "417") (name "unconnected-(SIPE-VDD_CORE20-PadN13)") (class "Default")
      (node (ref "SIP") (pin "N13") (pinfunction "VDD_CORE20_N13") (pintype "bidirectional"))
    )
    (net (code "418") (name "unconnected-(SIPE-VDD_MPU0-PadF10)") (class "Default")
      (node (ref "SIP") (pin "F10") (pinfunction "VDD_MPU0_F10") (pintype "bidirectional"))
    )
    (net (code "419") (name "unconnected-(SIPE-VDD_MPU1-PadF11)") (class "Default")
      (node (ref "SIP") (pin "F11") (pinfunction "VDD_MPU1_F11") (pintype "bidirectional"))
    )
    (net (code "420") (name "unconnected-(SIPE-VDD_MPU2-PadF12)") (class "Default")
      (node (ref "SIP") (pin "F12") (pinfunction "VDD_MPU2_F12") (pintype "bidirectional"))
    )
    (net (code "421") (name "unconnected-(SIPE-VDD_MPU3-PadF13)") (class "Default")
      (node (ref "SIP") (pin "F13") (pinfunction "VDD_MPU3_F13") (pintype "bidirectional"))
    )
    (net (code "422") (name "unconnected-(SIPE-VDD_MPU4-PadG13)") (class "Default")
      (node (ref "SIP") (pin "G13") (pinfunction "VDD_MPU4_G13") (pintype "bidirectional"))
    )
    (net (code "423") (name "unconnected-(SIPE-VDD_MPU5-PadH13)") (class "Default")
      (node (ref "SIP") (pin "H13") (pinfunction "VDD_MPU5_H13") (pintype "bidirectional"))
    )
    (net (code "424") (name "unconnected-(SIPE-VDD_MPU6-PadJ13)") (class "Default")
      (node (ref "SIP") (pin "J13") (pinfunction "VDD_MPU6_J13") (pintype "bidirectional"))
    )
    (net (code "425") (name "unconnected-(SIPE-VDD_MPU_MON-PadA2)") (class "Default")
      (node (ref "SIP") (pin "A2") (pinfunction "VDD_MPU_MON_A2") (pintype "bidirectional"))
    )
    (net (code "426") (name "unconnected-(SIPE-VDD_PLL1-PadE7)") (class "Default")
      (node (ref "SIP") (pin "E7") (pinfunction "VDD_PLL1_E7") (pintype "bidirectional"))
    )
    (net (code "427") (name "unconnected-(SIPE-VDD_PLL2-PadH15)") (class "Default")
      (node (ref "SIP") (pin "H15") (pinfunction "VDD_PLL2_H15") (pintype "bidirectional"))
    )
    (net (code "428") (name "unconnected-(SIPE-VDD_PLL3-PadR10)") (class "Default")
      (node (ref "SIP") (pin "R10") (pinfunction "VDD_PLL3_R10") (pintype "bidirectional"))
    )
    (net (code "429") (name "unconnected-(SIPE-VDD_PLL4-PadR11)") (class "Default")
      (node (ref "SIP") (pin "R11") (pinfunction "VDD_PLL4_R11") (pintype "bidirectional"))
    )
    (net (code "430") (name "unconnected-(SIPE-VDD_RTC1-PadD7)") (class "Default")
      (node (ref "SIP") (pin "D7") (pinfunction "VDD_RTC1_D7") (pintype "bidirectional"))
    )
    (net (code "431") (name "unconnected-(SIPE-VDD_RTC2-PadE6)") (class "Default")
      (node (ref "SIP") (pin "E6") (pinfunction "VDD_RTC2_E6") (pintype "bidirectional"))
    )
    (net (code "432") (name "unconnected-(SIPE-VDD_RTC4-PadF9)") (class "Default")
      (node (ref "SIP") (pin "F9") (pinfunction "VDD_RTC4_F9") (pintype "bidirectional"))
    )
    (net (code "433") (name "unconnected-(SIPE-VDD_RTC5-PadK13)") (class "Default")
      (node (ref "SIP") (pin "K13") (pinfunction "VDD_RTC5_K13") (pintype "bidirectional"))
    )
    (net (code "434") (name "unconnected-(SIPE-VDD_RTC6-PadN6)") (class "Default")
      (node (ref "SIP") (pin "N6") (pinfunction "VDD_RTC6_N6") (pintype "bidirectional"))
    )
    (net (code "435") (name "unconnected-(SIPE-VDD_RTC7-PadP9)") (class "Default")
      (node (ref "SIP") (pin "P9") (pinfunction "VDD_RTC7_P9") (pintype "bidirectional"))
    )
    (net (code "436") (name "unconnected-(SIPE-VDD_RTC8-PadP14)") (class "Default")
      (node (ref "SIP") (pin "P14") (pinfunction "VDD_RTC8_P14") (pintype "bidirectional"))
    )
    (net (code "437") (name "unconnected-(SIPE-VPP-PadM5)") (class "Default")
      (node (ref "SIP") (pin "M5") (pinfunction "VPP_M5") (pintype "bidirectional"))
    )
    (net (code "438") (name "unconnected-(U3-NC-Pad5)") (class "Default")
      (node (ref "U3") (pin "5") (pinfunction "NC_5") (pintype "bidirectional"))
    )
    (net (code "439") (name "unconnected-(U4-ID-Pad3)") (class "Default")
      (node (ref "U4") (pin "3") (pinfunction "ID_3") (pintype "bidirectional"))
    )
    (net (code "440") (name "unconnected-(U4-NC-Pad5)") (class "Default")
      (node (ref "U4") (pin "5") (pinfunction "NC_5") (pintype "bidirectional"))
    )
    (net (code "441") (name "unconnected-(U6-NC-Pad1)") (class "Default")
      (node (ref "U6") (pin "1") (pinfunction "NC_1") (pintype "passive"))
    )
    (net (code "442") (name "unconnected-(U7-BT_UART_DBG-Pad43)") (class "Default")
      (node (ref "U7") (pin "43") (pinfunction "BT_UART_DBG_43") (pintype "bidirectional"))
    )
    (net (code "443") (name "unconnected-(U7-GPIO1-Pad27)") (class "Default")
      (node (ref "U7") (pin "27") (pinfunction "GPIO1_27") (pintype "bidirectional"))
    )
    (net (code "444") (name "unconnected-(U7-GPIO2-Pad26)") (class "Default")
      (node (ref "U7") (pin "26") (pinfunction "GPIO2_26") (pintype "bidirectional"))
    )
    (net (code "445") (name "unconnected-(U7-GPIO4-Pad25)") (class "Default")
      (node (ref "U7") (pin "25") (pinfunction "GPIO4_25") (pintype "bidirectional"))
    )
    (net (code "446") (name "unconnected-(U7-GPIO9-Pad3)") (class "Default")
      (node (ref "U7") (pin "3") (pinfunction "GPIO9_3") (pintype "bidirectional"))
    )
    (net (code "447") (name "unconnected-(U7-GPIO10-Pad4)") (class "Default")
      (node (ref "U7") (pin "4") (pinfunction "GPIO10_4") (pintype "bidirectional"))
    )
    (net (code "448") (name "unconnected-(U7-GPIO11-Pad2)") (class "Default")
      (node (ref "U7") (pin "2") (pinfunction "GPIO11_2") (pintype "bidirectional"))
    )
    (net (code "449") (name "unconnected-(U7-GPIO12-Pad5)") (class "Default")
      (node (ref "U7") (pin "5") (pinfunction "GPIO12_5") (pintype "bidirectional"))
    )
    (net (code "450") (name "unconnected-(U7-RESERVED1-Pad21)") (class "Default")
      (node (ref "U7") (pin "21") (pinfunction "RESERVED1_21") (pintype "bidirectional"))
    )
    (net (code "451") (name "unconnected-(U7-RESERVED2-Pad22)") (class "Default")
      (node (ref "U7") (pin "22") (pinfunction "RESERVED2_22") (pintype "bidirectional"))
    )
    (net (code "452") (name "unconnected-(U7-RESERVED3-Pad62)") (class "Default")
      (node (ref "U7") (pin "62") (pinfunction "RESERVED3_62") (pintype "bidirectional"))
    )
    (net (code "453") (name "unconnected-(U7-WL_UART_DBG-Pad42)") (class "Default")
      (node (ref "U7") (pin "42") (pinfunction "WL_UART_DBG_42") (pintype "bidirectional"))
    )
  )
)
